# QuDAC_V2.net
KiCad netlist of a schematic drawn in EAGLE
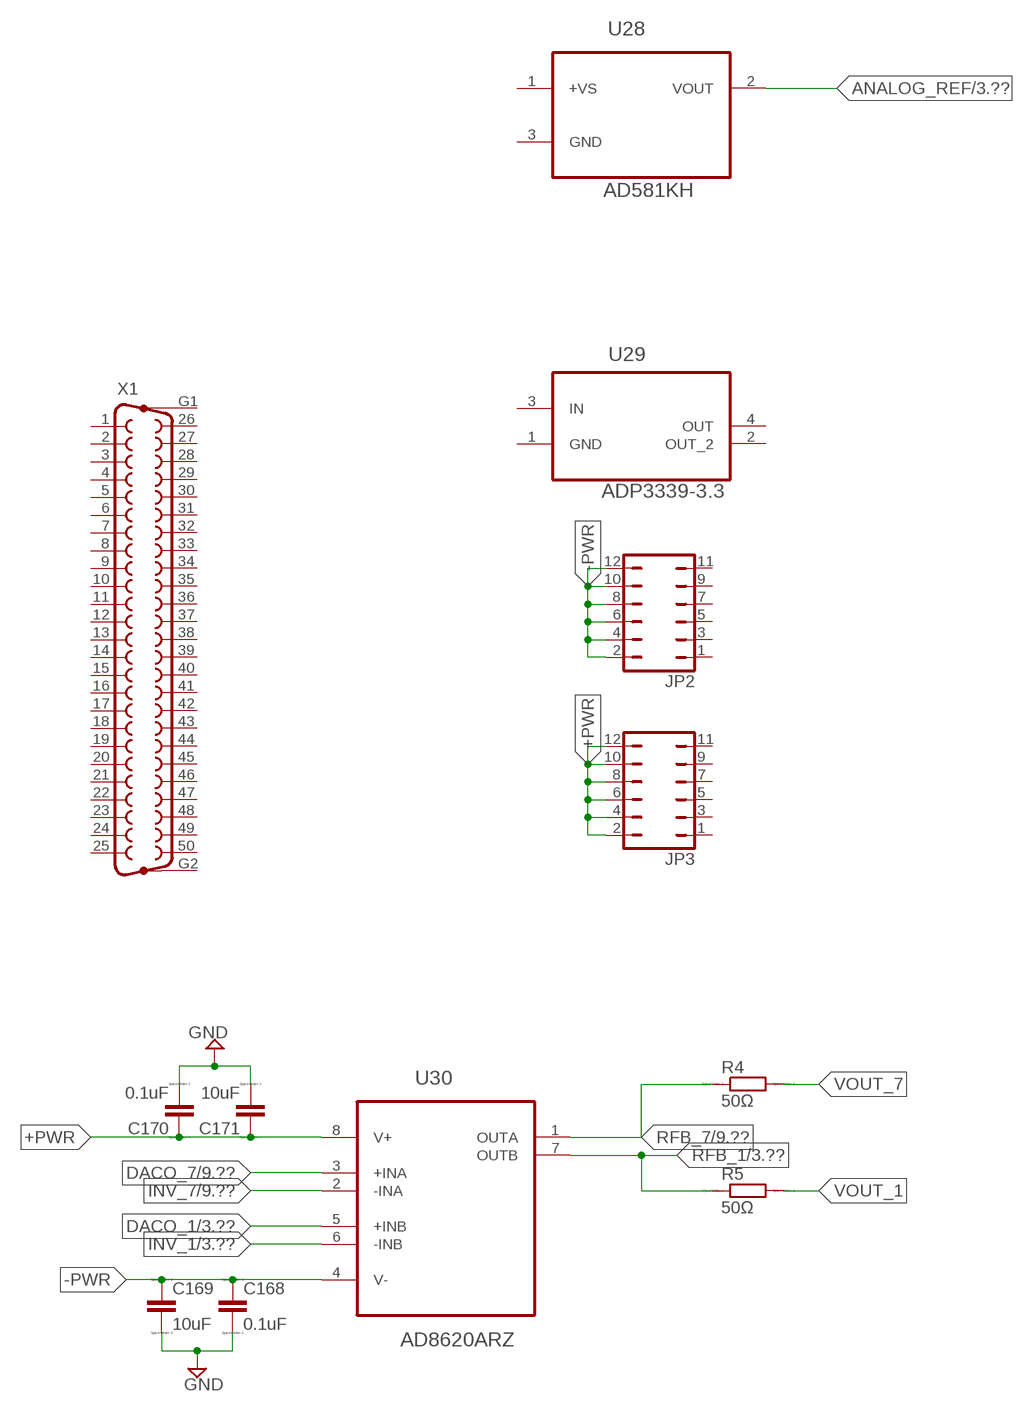
[diagram p0: schematic, sheet 1]
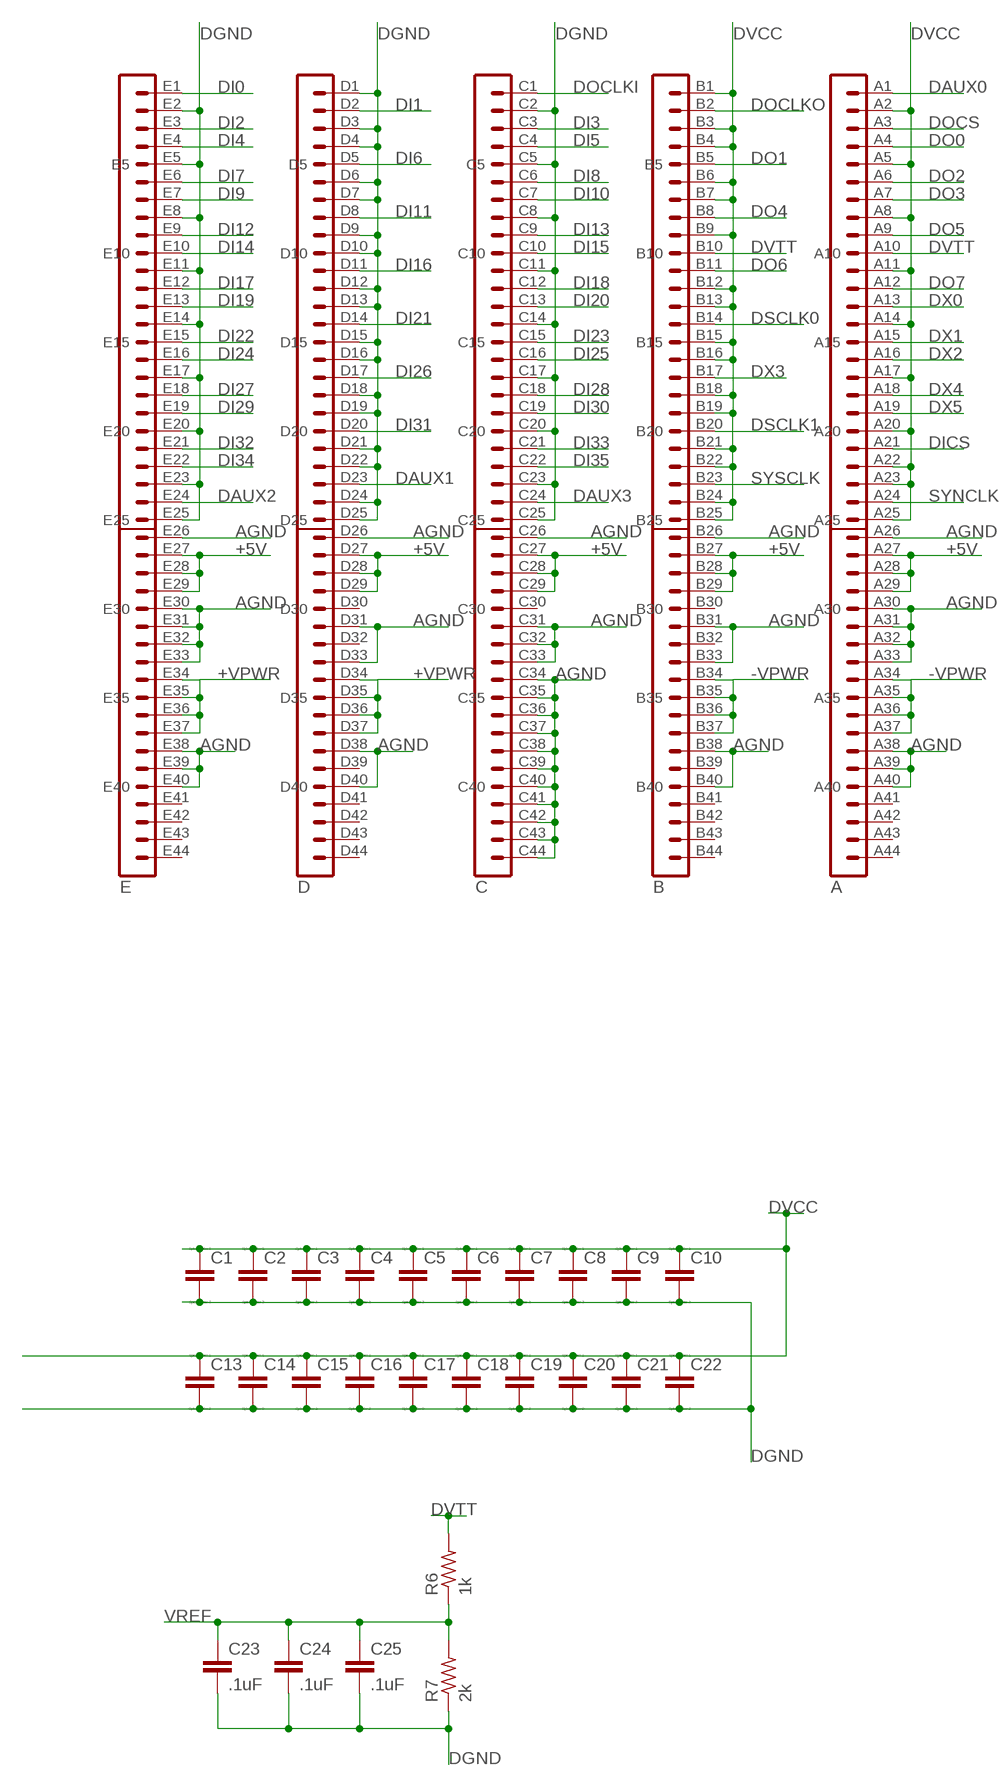
[diagram p1: schematic, sheet 2, part 1 of 2]
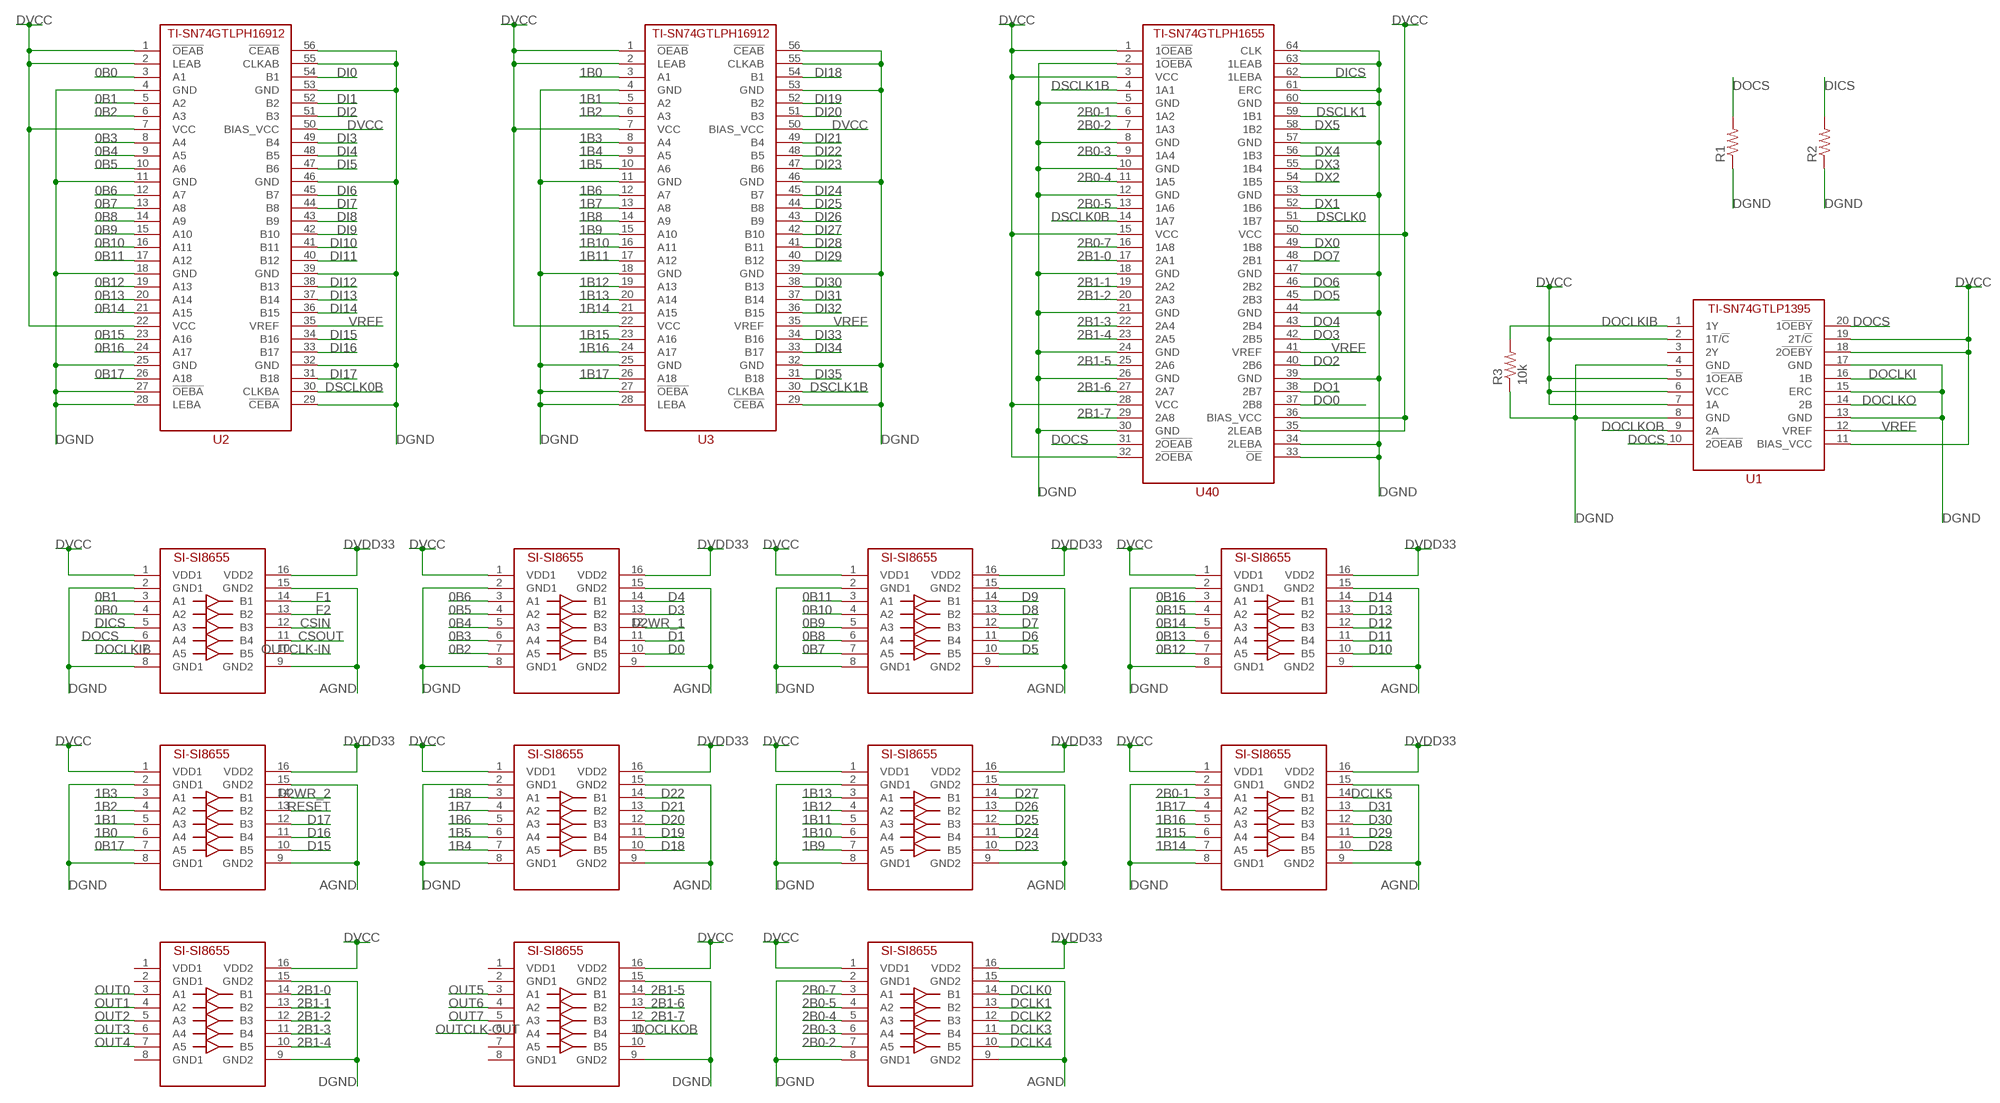
[diagram p2: schematic, sheet 2, part 2 of 2]
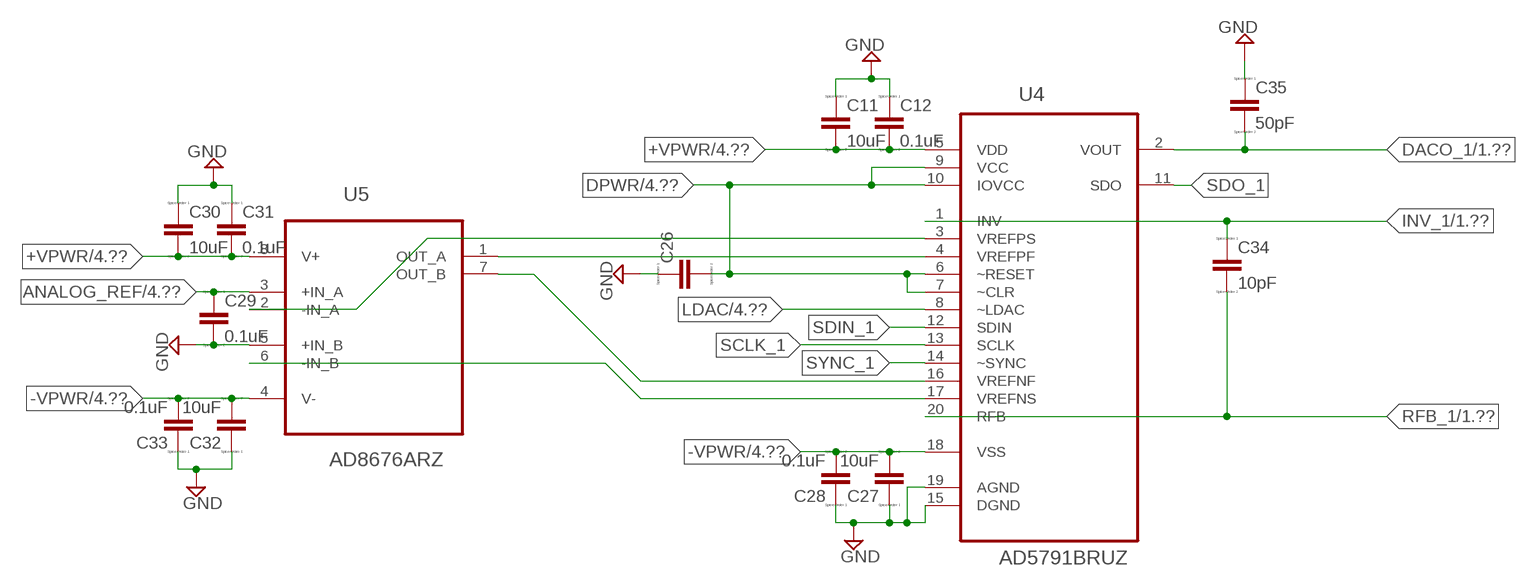
[diagram p3: schematic, sheet 3]
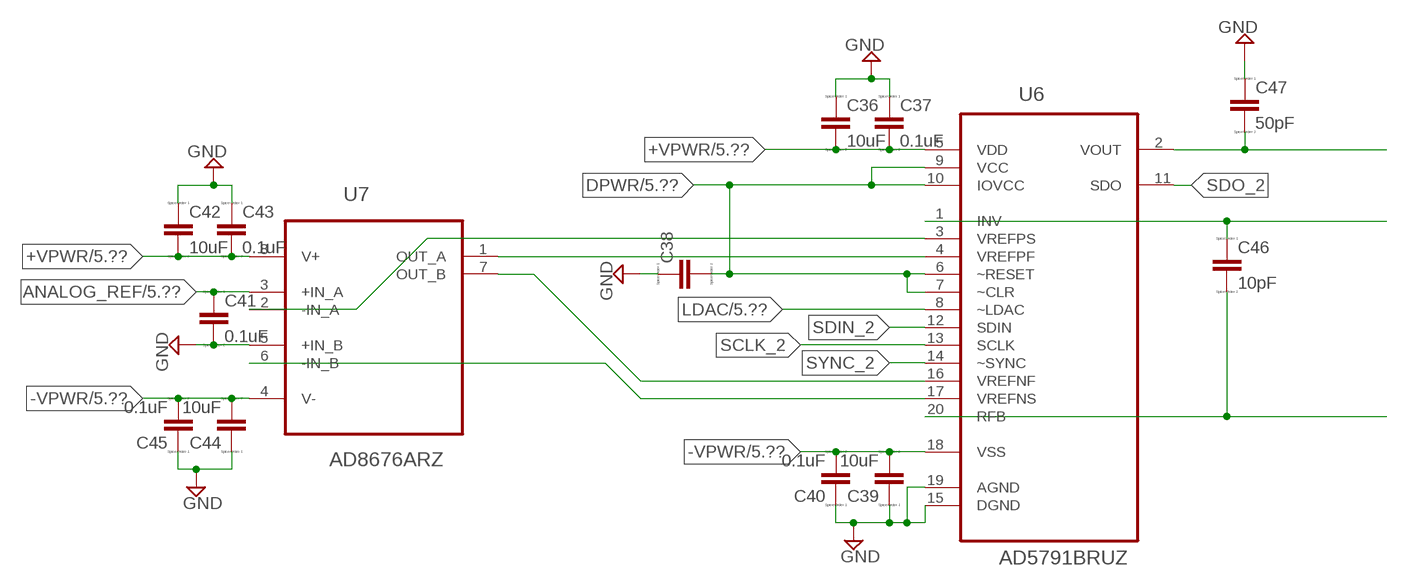
[diagram p4: schematic, sheet 4]
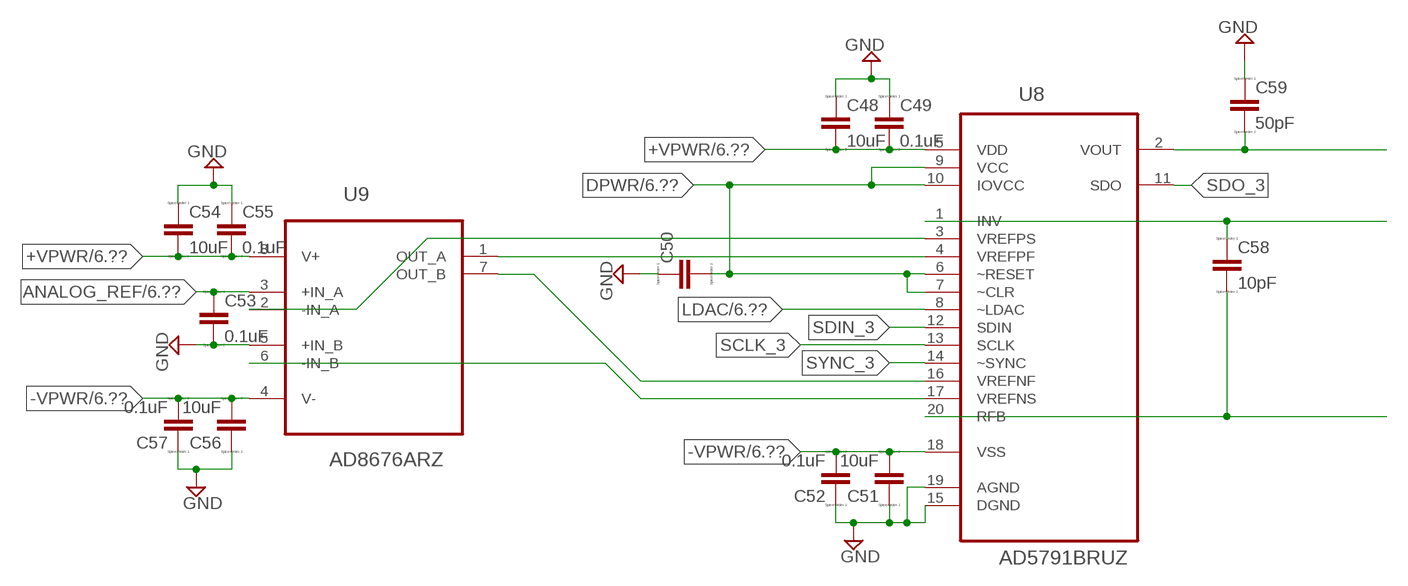
[diagram p5: schematic, sheet 5]
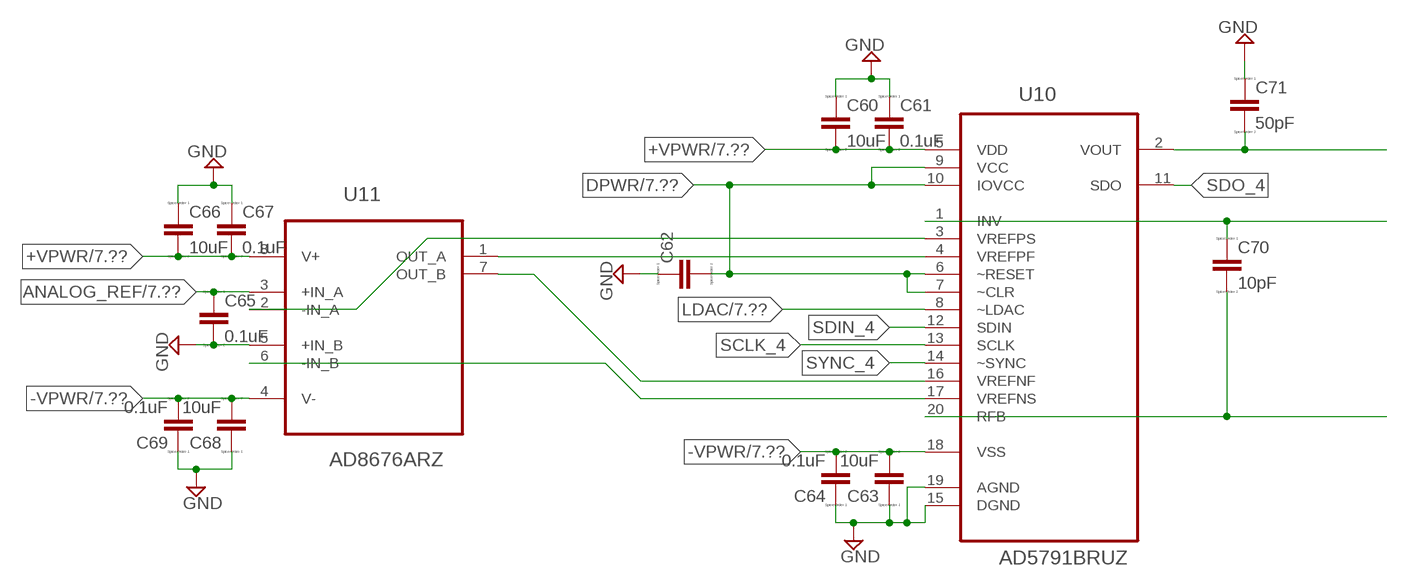
[diagram p6: schematic, sheet 6]
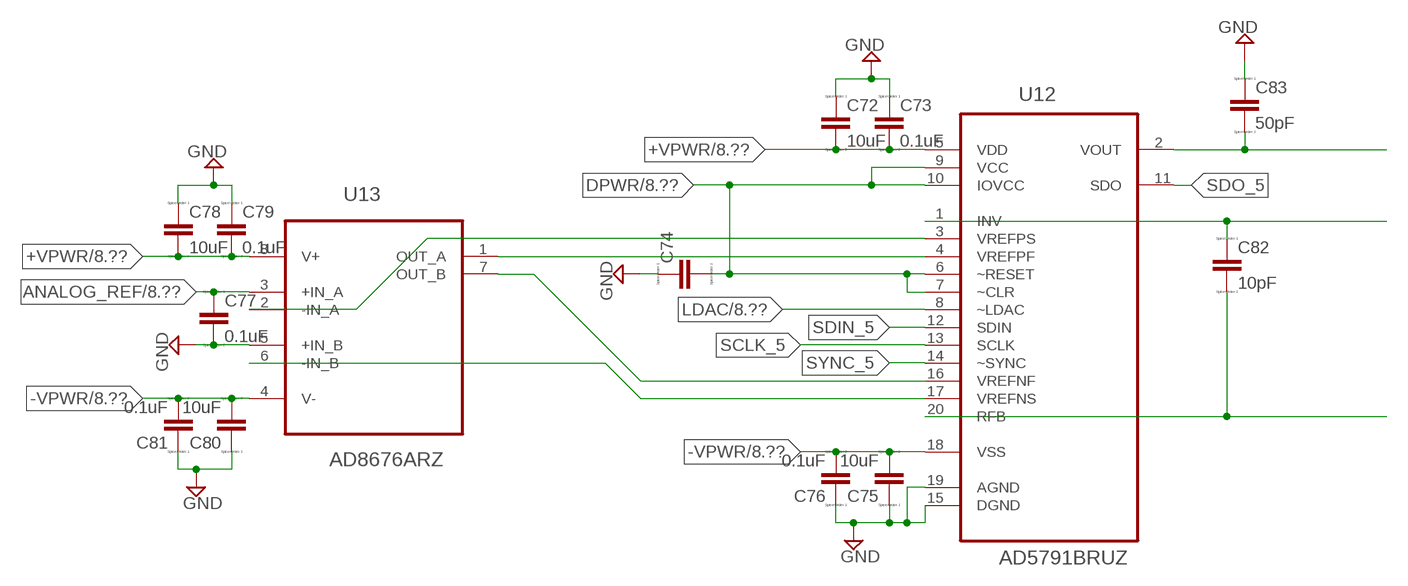
[diagram p7: schematic, sheet 7]
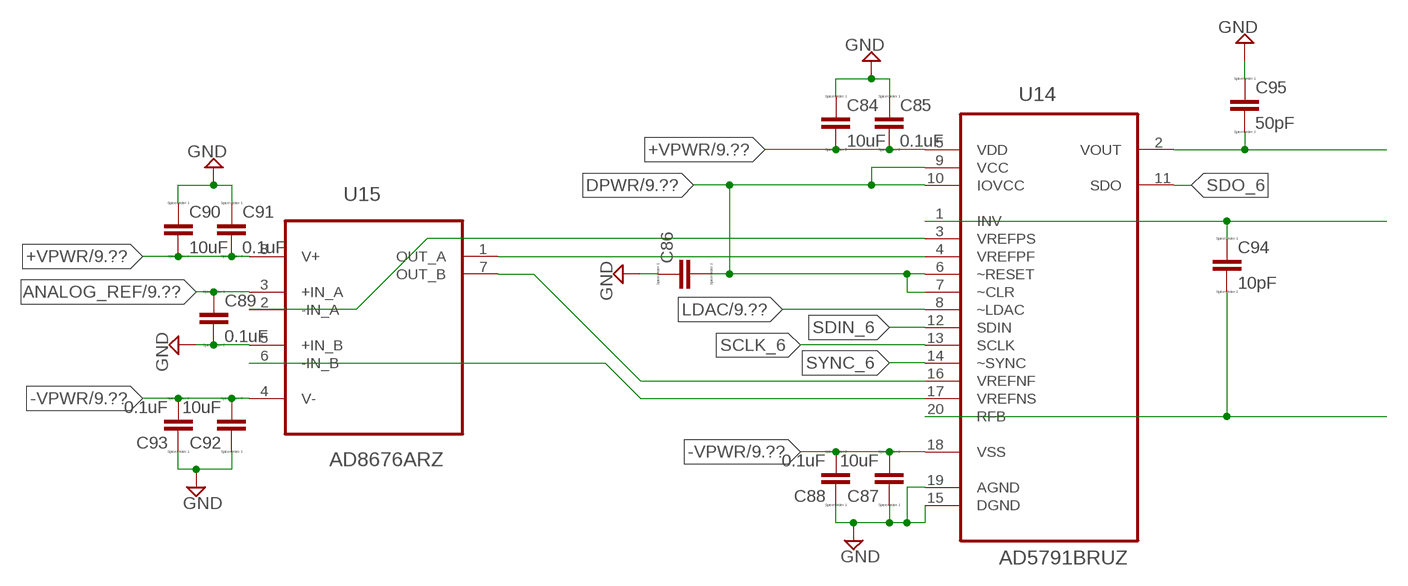
[diagram p8: schematic, sheet 8]
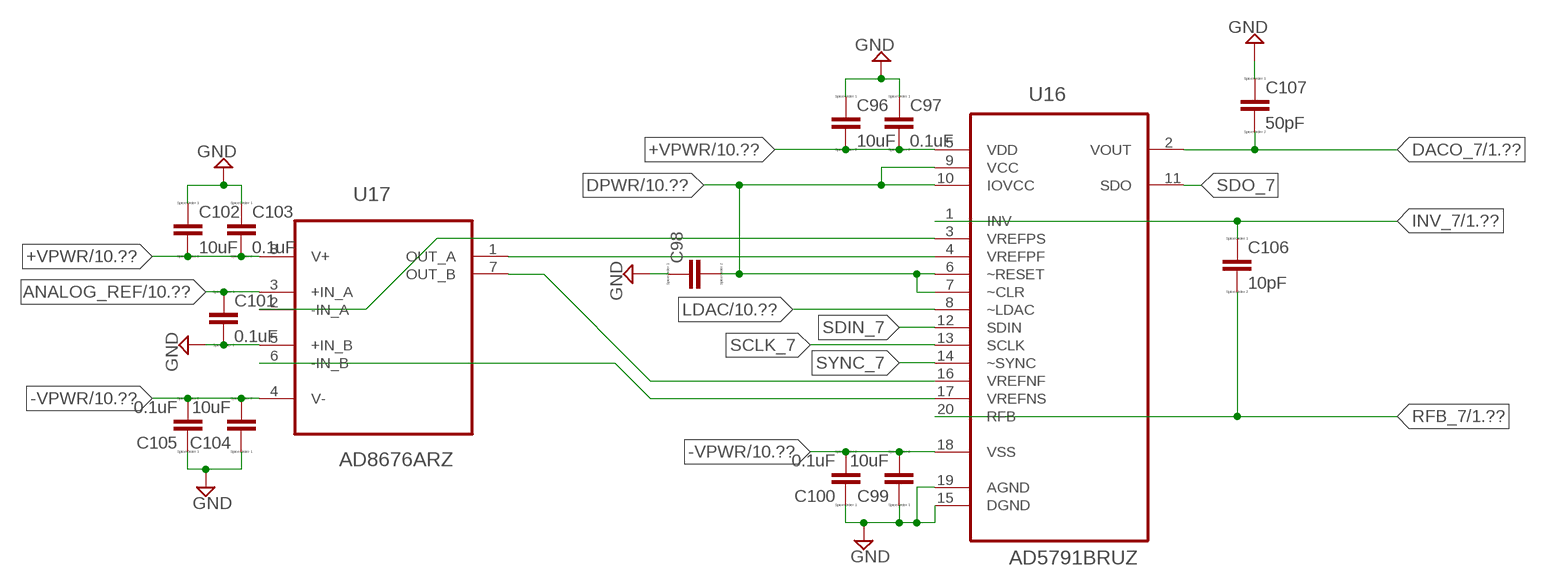
[diagram p9: schematic, sheet 9]
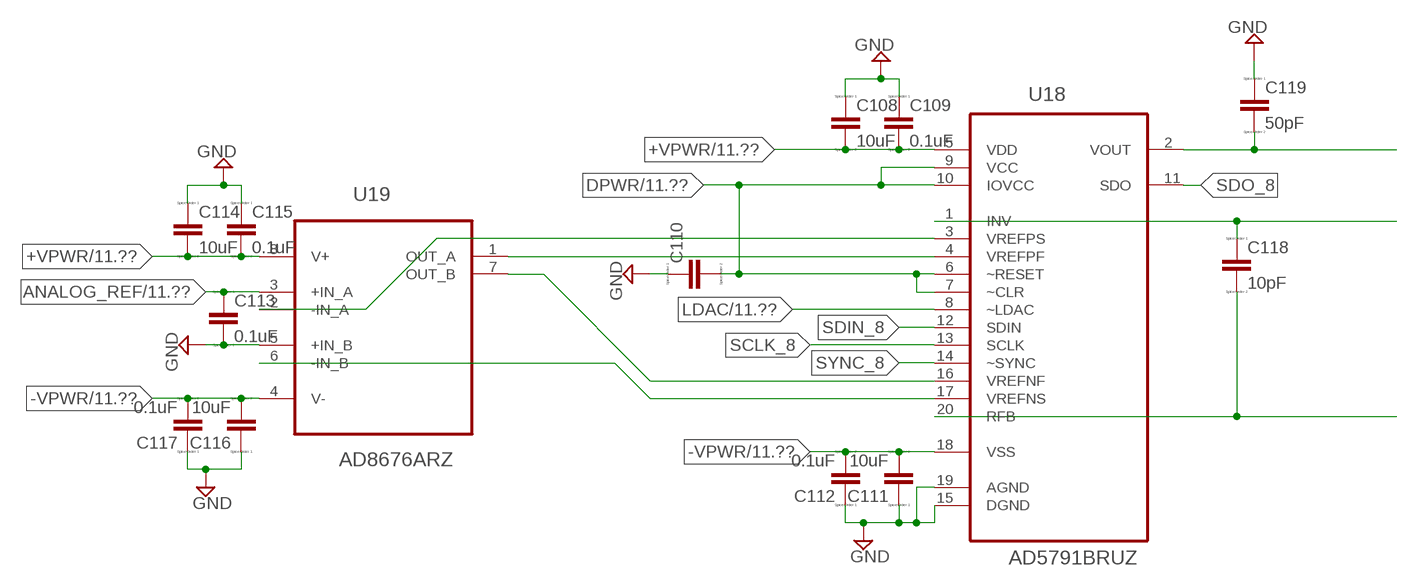
[diagram p10: schematic, sheet 10]
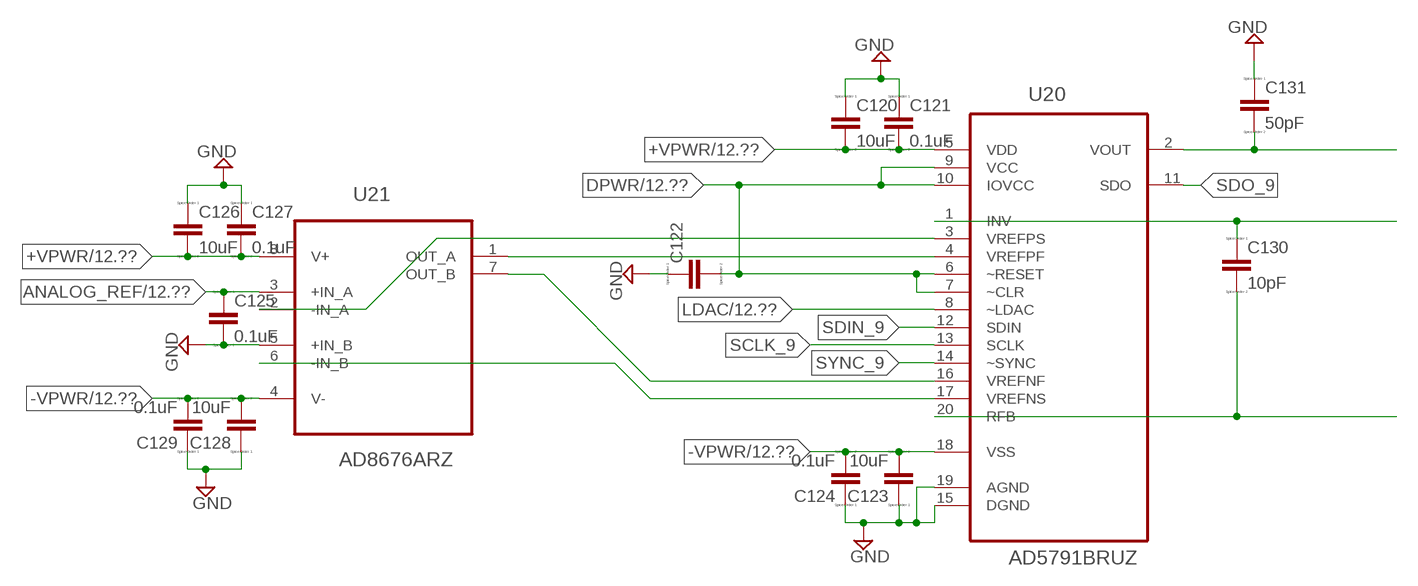
[diagram p11: schematic, sheet 11]
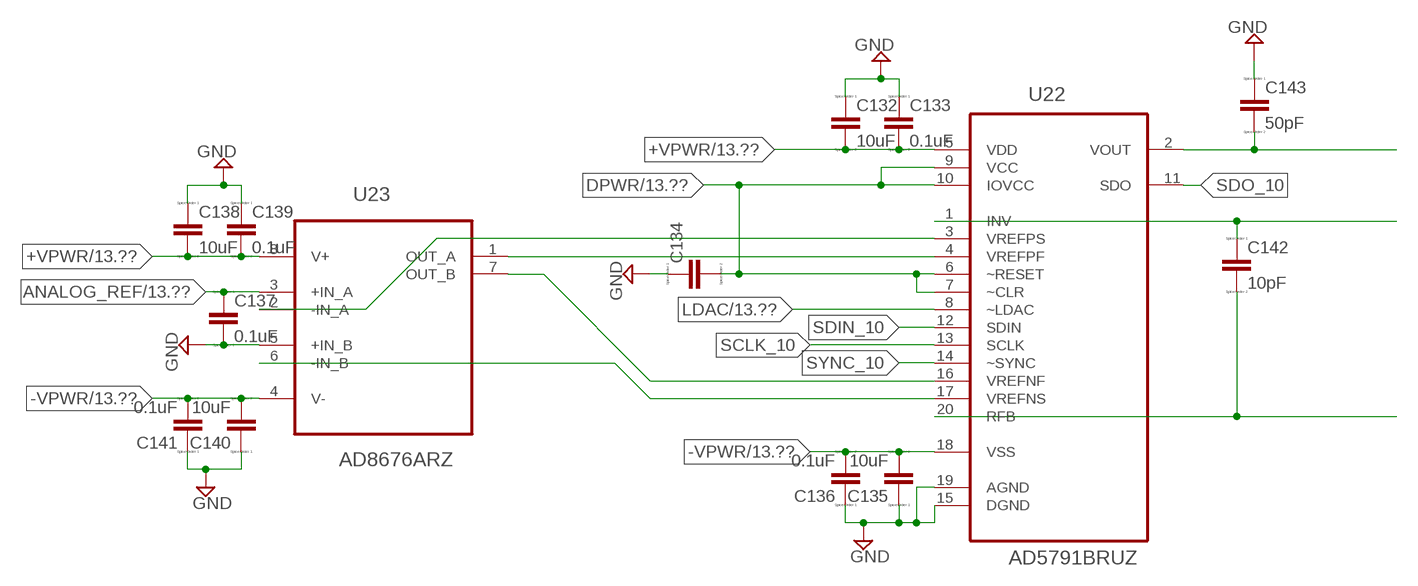
[diagram p12: schematic, sheet 12]
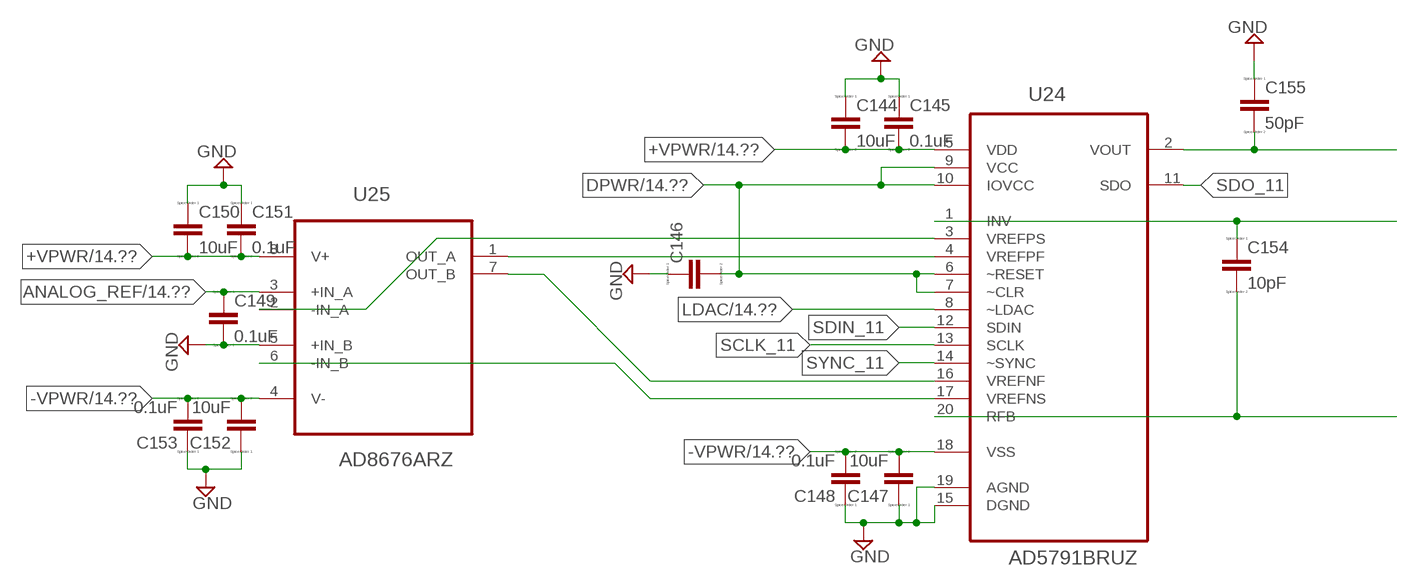
[diagram p13: schematic, sheet 13]
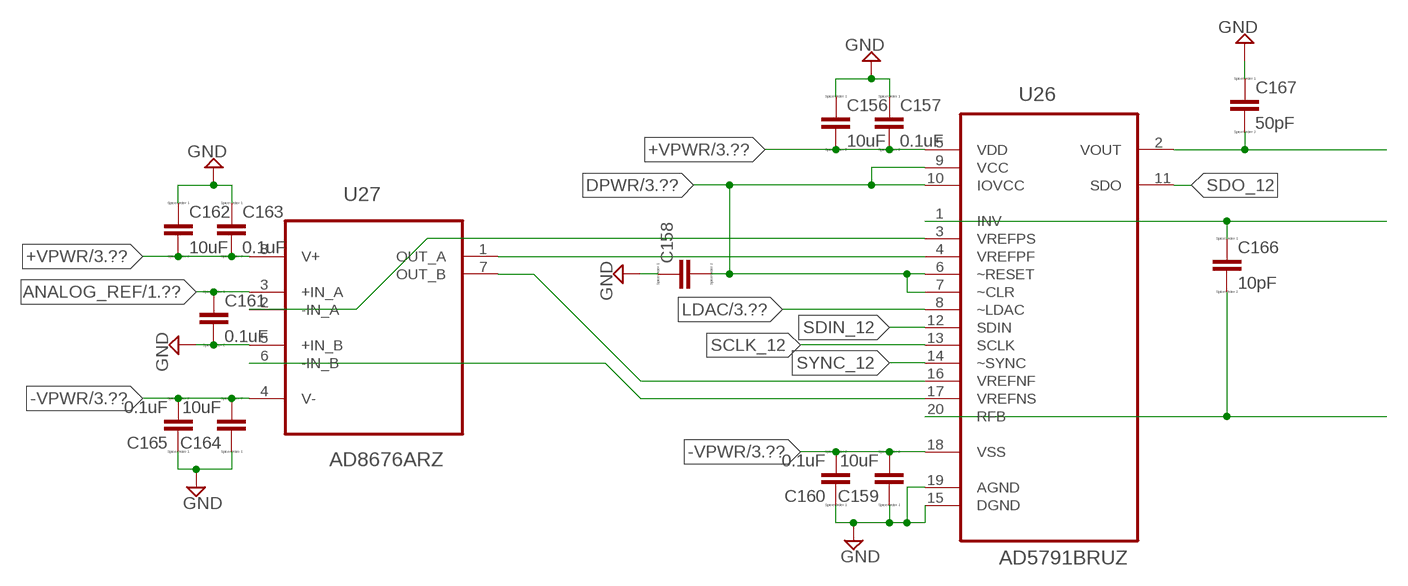
[diagram p14: schematic, sheet 14]

(export (version "E")
  (design (tool "Eeschema 10.0.6"))
  (components
    (comp (ref "C72")
      (value "10uF")
      (footprint "eagle-import:C0805")
      (libsource (lib "eagle-import") (part "C"))
    )
    (comp (ref "C73")
      (value "0.1uF")
      (footprint "eagle-import:C0603")
      (libsource (lib "eagle-import") (part "CC0603"))
    )
    (comp (ref "C74")
      (value "CC0603")
      (footprint "eagle-import:C0603")
      (libsource (lib "eagle-import") (part "CC0603"))
    )
    (comp (ref "C75")
      (value "10uF")
      (footprint "eagle-import:C0805")
      (libsource (lib "eagle-import") (part "C"))
    )
    (comp (ref "C76")
      (value "0.1uF")
      (footprint "eagle-import:C0603")
      (libsource (lib "eagle-import") (part "CC0603"))
    )
    (comp (ref "C77")
      (value "0.1uF")
      (footprint "eagle-import:C0603")
      (libsource (lib "eagle-import") (part "CC0603"))
    )
    (comp (ref "C78")
      (value "10uF")
      (footprint "eagle-import:C0805")
      (libsource (lib "eagle-import") (part "C"))
    )
    (comp (ref "C79")
      (value "0.1uF")
      (footprint "eagle-import:C0603")
      (libsource (lib "eagle-import") (part "CC0603"))
    )
    (comp (ref "C80")
      (value "10uF")
      (footprint "eagle-import:C0805")
      (libsource (lib "eagle-import") (part "C"))
    )
    (comp (ref "C81")
      (value "0.1uF")
      (footprint "eagle-import:C0603")
      (libsource (lib "eagle-import") (part "CC0603"))
    )
    (comp (ref "C82")
      (value "10pF")
      (footprint "eagle-import:C0603")
      (libsource (lib "eagle-import") (part "CC0603"))
    )
    (comp (ref "C83")
      (value "50pF")
      (footprint "eagle-import:C0603")
      (libsource (lib "eagle-import") (part "CC0603"))
    )
    (comp (ref "U12")
      (value "AD5791BRUZ")
      (footprint "eagle-import:SOP65P640X120-20N")
      (libsource (lib "eagle-import") (part "AD5791BRUZ"))
    )
    (comp (ref "U13")
      (value "AD8676ARZ")
      (footprint "eagle-import:SOIC127P600X175-8N")
      (libsource (lib "eagle-import") (part "AD8676ARZ"))
    )
    (comp (ref "C108")
      (value "10uF")
      (footprint "eagle-import:C0805")
      (libsource (lib "eagle-import") (part "C"))
    )
    (comp (ref "C109")
      (value "0.1uF")
      (footprint "eagle-import:C0603")
      (libsource (lib "eagle-import") (part "CC0603"))
    )
    (comp (ref "C110")
      (value "CC0603")
      (footprint "eagle-import:C0603")
      (libsource (lib "eagle-import") (part "CC0603"))
    )
    (comp (ref "C111")
      (value "10uF")
      (footprint "eagle-import:C0805")
      (libsource (lib "eagle-import") (part "C"))
    )
    (comp (ref "C112")
      (value "0.1uF")
      (footprint "eagle-import:C0603")
      (libsource (lib "eagle-import") (part "CC0603"))
    )
    (comp (ref "C113")
      (value "0.1uF")
      (footprint "eagle-import:C0603")
      (libsource (lib "eagle-import") (part "CC0603"))
    )
    (comp (ref "C114")
      (value "10uF")
      (footprint "eagle-import:C0805")
      (libsource (lib "eagle-import") (part "C"))
    )
    (comp (ref "C115")
      (value "0.1uF")
      (footprint "eagle-import:C0603")
      (libsource (lib "eagle-import") (part "CC0603"))
    )
    (comp (ref "C116")
      (value "10uF")
      (footprint "eagle-import:C0805")
      (libsource (lib "eagle-import") (part "C"))
    )
    (comp (ref "C117")
      (value "0.1uF")
      (footprint "eagle-import:C0603")
      (libsource (lib "eagle-import") (part "CC0603"))
    )
    (comp (ref "C118")
      (value "10pF")
      (footprint "eagle-import:C0603")
      (libsource (lib "eagle-import") (part "CC0603"))
    )
    (comp (ref "C119")
      (value "50pF")
      (footprint "eagle-import:C0603")
      (libsource (lib "eagle-import") (part "CC0603"))
    )
    (comp (ref "U18")
      (value "AD5791BRUZ")
      (footprint "eagle-import:SOP65P640X120-20N")
      (libsource (lib "eagle-import") (part "AD5791BRUZ"))
    )
    (comp (ref "U19")
      (value "AD8676ARZ")
      (footprint "eagle-import:SOIC127P600X175-8N")
      (libsource (lib "eagle-import") (part "AD8676ARZ"))
    )
    (comp (ref "C1")
      (value "CC0603")
      (footprint "eagle-import:C0603")
      (libsource (lib "eagle-import") (part "CC0603"))
    )
    (comp (ref "C2")
      (value "CC0603")
      (footprint "eagle-import:C0603")
      (libsource (lib "eagle-import") (part "CC0603"))
    )
    (comp (ref "C3")
      (value "CC0603")
      (footprint "eagle-import:C0603")
      (libsource (lib "eagle-import") (part "CC0603"))
    )
    (comp (ref "C4")
      (value "CC0603")
      (footprint "eagle-import:C0603")
      (libsource (lib "eagle-import") (part "CC0603"))
    )
    (comp (ref "C5")
      (value "CC0603")
      (footprint "eagle-import:C0603")
      (libsource (lib "eagle-import") (part "CC0603"))
    )
    (comp (ref "C6")
      (value "CC0603")
      (footprint "eagle-import:C0603")
      (libsource (lib "eagle-import") (part "CC0603"))
    )
    (comp (ref "C7")
      (value "CC0603")
      (footprint "eagle-import:C0603")
      (libsource (lib "eagle-import") (part "CC0603"))
    )
    (comp (ref "C8")
      (value "CC0603")
      (footprint "eagle-import:C0603")
      (libsource (lib "eagle-import") (part "CC0603"))
    )
    (comp (ref "C9")
      (value "CC0603")
      (footprint "eagle-import:C0603")
      (libsource (lib "eagle-import") (part "CC0603"))
    )
    (comp (ref "C10")
      (value "CC0603")
      (footprint "eagle-import:C0603")
      (libsource (lib "eagle-import") (part "CC0603"))
    )
    (comp (ref "C13")
      (value "CC0603")
      (footprint "eagle-import:C0603")
      (libsource (lib "eagle-import") (part "CC0603"))
    )
    (comp (ref "C14")
      (value "CC0603")
      (footprint "eagle-import:C0603")
      (libsource (lib "eagle-import") (part "CC0603"))
    )
    (comp (ref "C15")
      (value "CC0603")
      (footprint "eagle-import:C0603")
      (libsource (lib "eagle-import") (part "CC0603"))
    )
    (comp (ref "C16")
      (value "CC0603")
      (footprint "eagle-import:C0603")
      (libsource (lib "eagle-import") (part "CC0603"))
    )
    (comp (ref "C17")
      (value "CC0603")
      (footprint "eagle-import:C0603")
      (libsource (lib "eagle-import") (part "CC0603"))
    )
    (comp (ref "C18")
      (value "CC0603")
      (footprint "eagle-import:C0603")
      (libsource (lib "eagle-import") (part "CC0603"))
    )
    (comp (ref "C19")
      (value "CC0603")
      (footprint "eagle-import:C0603")
      (libsource (lib "eagle-import") (part "CC0603"))
    )
    (comp (ref "C20")
      (value "CC0603")
      (footprint "eagle-import:C0603")
      (libsource (lib "eagle-import") (part "CC0603"))
    )
    (comp (ref "C21")
      (value "CC0603")
      (footprint "eagle-import:C0603")
      (libsource (lib "eagle-import") (part "CC0603"))
    )
    (comp (ref "C22")
      (value "CC0603")
      (footprint "eagle-import:C0603")
      (libsource (lib "eagle-import") (part "CC0603"))
    )
    (comp (ref "C23")
      (value ".1uF")
      (footprint "eagle-import:C0603")
      (libsource (lib "eagle-import") (part "C-EUC0603"))
    )
    (comp (ref "C24")
      (value ".1uF")
      (footprint "eagle-import:C0603")
      (libsource (lib "eagle-import") (part "C-EUC0603"))
    )
    (comp (ref "C25")
      (value ".1uF")
      (footprint "eagle-import:C0603")
      (libsource (lib "eagle-import") (part "C-EUC0603"))
    )
    (comp (ref "ISO1")
      (value "SI-SI8655")
      (footprint "eagle-import:QSOP-16")
      (libsource (lib "eagle-import") (part "SI-SI8655"))
    )
    (comp (ref "ISO2")
      (value "SI-SI8655")
      (footprint "eagle-import:QSOP-16")
      (libsource (lib "eagle-import") (part "SI-SI8655"))
    )
    (comp (ref "ISO3")
      (value "SI-SI8655")
      (footprint "eagle-import:QSOP-16")
      (libsource (lib "eagle-import") (part "SI-SI8655"))
    )
    (comp (ref "ISO4")
      (value "SI-SI8655")
      (footprint "eagle-import:QSOP-16")
      (libsource (lib "eagle-import") (part "SI-SI8655"))
    )
    (comp (ref "ISO5")
      (value "SI-SI8655")
      (footprint "eagle-import:QSOP-16")
      (libsource (lib "eagle-import") (part "SI-SI8655"))
    )
    (comp (ref "ISO6")
      (value "SI-SI8655")
      (footprint "eagle-import:QSOP-16")
      (libsource (lib "eagle-import") (part "SI-SI8655"))
    )
    (comp (ref "ISO7")
      (value "SI-SI8655")
      (footprint "eagle-import:QSOP-16")
      (libsource (lib "eagle-import") (part "SI-SI8655"))
    )
    (comp (ref "ISO8")
      (value "SI-SI8655")
      (footprint "eagle-import:QSOP-16")
      (libsource (lib "eagle-import") (part "SI-SI8655"))
    )
    (comp (ref "ISO9")
      (value "SI-SI8655")
      (footprint "eagle-import:QSOP-16")
      (libsource (lib "eagle-import") (part "SI-SI8655"))
    )
    (comp (ref "ISO10")
      (value "SI-SI8655")
      (footprint "eagle-import:QSOP-16")
      (libsource (lib "eagle-import") (part "SI-SI8655"))
    )
    (comp (ref "ISO11")
      (value "SI-SI8655")
      (footprint "eagle-import:QSOP-16")
      (libsource (lib "eagle-import") (part "SI-SI8655"))
    )
    (comp (ref "J1")
      (value "EUROCARD-CPCI-220EUROCARD-B19+AB25-NOFRONTDIM")
      (footprint "eagle-import:EUROCARD-CPCI-B19+1B25-NOFRONTDIM")
      (libsource (lib "eagle-import") (part "EUROCARD-CPCI-220EUROCARD-B19+AB25-NOFRONTDIM"))
    )
    (comp (ref "R1")
      (value "R-US_R0603")
      (footprint "eagle-import:R0603")
      (libsource (lib "eagle-import") (part "R-US_R0603"))
    )
    (comp (ref "R2")
      (value "R-US_R0603")
      (footprint "eagle-import:R0603")
      (libsource (lib "eagle-import") (part "R-US_R0603"))
    )
    (comp (ref "R3")
      (value "10k")
      (footprint "eagle-import:R0603")
      (libsource (lib "eagle-import") (part "R-US_R0603"))
    )
    (comp (ref "R6")
      (value "1k")
      (footprint "eagle-import:R0805")
      (libsource (lib "eagle-import") (part "R-US_R0805"))
    )
    (comp (ref "R7")
      (value "2k")
      (footprint "eagle-import:R0805")
      (libsource (lib "eagle-import") (part "R-US_R0805"))
    )
    (comp (ref "U1")
      (value "TI-SN74GTLP1395")
      (footprint "eagle-import:TSSOP-20")
      (libsource (lib "eagle-import") (part "TI-SN74GTLP1395"))
    )
    (comp (ref "U2")
      (value "TI-SN74GTLPH16912")
      (footprint "eagle-import:TSSOP-56")
      (libsource (lib "eagle-import") (part "TI-SN74GTLPH16912"))
    )
    (comp (ref "U3")
      (value "TI-SN74GTLPH16912")
      (footprint "eagle-import:TSSOP-56")
      (libsource (lib "eagle-import") (part "TI-SN74GTLPH16912"))
    )
    (comp (ref "U40")
      (value "TI-SN74GTLPH1655")
      (footprint "eagle-import:TSSOP-64")
      (libsource (lib "eagle-import") (part "TI-SN74GTLPH1655"))
    )
    (comp (ref "C36")
      (value "10uF")
      (footprint "eagle-import:C0805")
      (libsource (lib "eagle-import") (part "C"))
    )
    (comp (ref "C37")
      (value "0.1uF")
      (footprint "eagle-import:C0603")
      (libsource (lib "eagle-import") (part "CC0603"))
    )
    (comp (ref "C38")
      (value "CC0603")
      (footprint "eagle-import:C0603")
      (libsource (lib "eagle-import") (part "CC0603"))
    )
    (comp (ref "C39")
      (value "10uF")
      (footprint "eagle-import:C0805")
      (libsource (lib "eagle-import") (part "C"))
    )
    (comp (ref "C40")
      (value "0.1uF")
      (footprint "eagle-import:C0603")
      (libsource (lib "eagle-import") (part "CC0603"))
    )
    (comp (ref "C41")
      (value "0.1uF")
      (footprint "eagle-import:C0603")
      (libsource (lib "eagle-import") (part "CC0603"))
    )
    (comp (ref "C42")
      (value "10uF")
      (footprint "eagle-import:C0805")
      (libsource (lib "eagle-import") (part "C"))
    )
    (comp (ref "C43")
      (value "0.1uF")
      (footprint "eagle-import:C0603")
      (libsource (lib "eagle-import") (part "CC0603"))
    )
    (comp (ref "C44")
      (value "10uF")
      (footprint "eagle-import:C0805")
      (libsource (lib "eagle-import") (part "C"))
    )
    (comp (ref "C45")
      (value "0.1uF")
      (footprint "eagle-import:C0603")
      (libsource (lib "eagle-import") (part "CC0603"))
    )
    (comp (ref "C46")
      (value "10pF")
      (footprint "eagle-import:C0603")
      (libsource (lib "eagle-import") (part "CC0603"))
    )
    (comp (ref "C47")
      (value "50pF")
      (footprint "eagle-import:C0603")
      (libsource (lib "eagle-import") (part "CC0603"))
    )
    (comp (ref "U6")
      (value "AD5791BRUZ")
      (footprint "eagle-import:SOP65P640X120-20N")
      (libsource (lib "eagle-import") (part "AD5791BRUZ"))
    )
    (comp (ref "U7")
      (value "AD8676ARZ")
      (footprint "eagle-import:SOIC127P600X175-8N")
      (libsource (lib "eagle-import") (part "AD8676ARZ"))
    )
    (comp (ref "C60")
      (value "10uF")
      (footprint "eagle-import:C0805")
      (libsource (lib "eagle-import") (part "C"))
    )
    (comp (ref "C61")
      (value "0.1uF")
      (footprint "eagle-import:C0603")
      (libsource (lib "eagle-import") (part "CC0603"))
    )
    (comp (ref "C62")
      (value "CC0603")
      (footprint "eagle-import:C0603")
      (libsource (lib "eagle-import") (part "CC0603"))
    )
    (comp (ref "C63")
      (value "10uF")
      (footprint "eagle-import:C0805")
      (libsource (lib "eagle-import") (part "C"))
    )
    (comp (ref "C64")
      (value "0.1uF")
      (footprint "eagle-import:C0603")
      (libsource (lib "eagle-import") (part "CC0603"))
    )
    (comp (ref "C65")
      (value "0.1uF")
      (footprint "eagle-import:C0603")
      (libsource (lib "eagle-import") (part "CC0603"))
    )
    (comp (ref "C66")
      (value "10uF")
      (footprint "eagle-import:C0805")
      (libsource (lib "eagle-import") (part "C"))
    )
    (comp (ref "C67")
      (value "0.1uF")
      (footprint "eagle-import:C0603")
      (libsource (lib "eagle-import") (part "CC0603"))
    )
    (comp (ref "C68")
      (value "10uF")
      (footprint "eagle-import:C0805")
      (libsource (lib "eagle-import") (part "C"))
    )
    (comp (ref "C69")
      (value "0.1uF")
      (footprint "eagle-import:C0603")
      (libsource (lib "eagle-import") (part "CC0603"))
    )
    (comp (ref "C70")
      (value "10pF")
      (footprint "eagle-import:C0603")
      (libsource (lib "eagle-import") (part "CC0603"))
    )
    (comp (ref "C71")
      (value "50pF")
      (footprint "eagle-import:C0603")
      (libsource (lib "eagle-import") (part "CC0603"))
    )
    (comp (ref "U10")
      (value "AD5791BRUZ")
      (footprint "eagle-import:SOP65P640X120-20N")
      (libsource (lib "eagle-import") (part "AD5791BRUZ"))
    )
    (comp (ref "U11")
      (value "AD8676ARZ")
      (footprint "eagle-import:SOIC127P600X175-8N")
      (libsource (lib "eagle-import") (part "AD8676ARZ"))
    )
    (comp (ref "C120")
      (value "10uF")
      (footprint "eagle-import:C0805")
      (libsource (lib "eagle-import") (part "C"))
    )
    (comp (ref "C121")
      (value "0.1uF")
      (footprint "eagle-import:C0603")
      (libsource (lib "eagle-import") (part "CC0603"))
    )
    (comp (ref "C122")
      (value "CC0603")
      (footprint "eagle-import:C0603")
      (libsource (lib "eagle-import") (part "CC0603"))
    )
    (comp (ref "C123")
      (value "10uF")
      (footprint "eagle-import:C0805")
      (libsource (lib "eagle-import") (part "C"))
    )
    (comp (ref "C124")
      (value "0.1uF")
      (footprint "eagle-import:C0603")
      (libsource (lib "eagle-import") (part "CC0603"))
    )
    (comp (ref "C125")
      (value "0.1uF")
      (footprint "eagle-import:C0603")
      (libsource (lib "eagle-import") (part "CC0603"))
    )
    (comp (ref "C126")
      (value "10uF")
      (footprint "eagle-import:C0805")
      (libsource (lib "eagle-import") (part "C"))
    )
    (comp (ref "C127")
      (value "0.1uF")
      (footprint "eagle-import:C0603")
      (libsource (lib "eagle-import") (part "CC0603"))
    )
    (comp (ref "C128")
      (value "10uF")
      (footprint "eagle-import:C0805")
      (libsource (lib "eagle-import") (part "C"))
    )
    (comp (ref "C129")
      (value "0.1uF")
      (footprint "eagle-import:C0603")
      (libsource (lib "eagle-import") (part "CC0603"))
    )
    (comp (ref "C130")
      (value "10pF")
      (footprint "eagle-import:C0603")
      (libsource (lib "eagle-import") (part "CC0603"))
    )
    (comp (ref "C131")
      (value "50pF")
      (footprint "eagle-import:C0603")
      (libsource (lib "eagle-import") (part "CC0603"))
    )
    (comp (ref "U20")
      (value "AD5791BRUZ")
      (footprint "eagle-import:SOP65P640X120-20N")
      (libsource (lib "eagle-import") (part "AD5791BRUZ"))
    )
    (comp (ref "U21")
      (value "AD8676ARZ")
      (footprint "eagle-import:SOIC127P600X175-8N")
      (libsource (lib "eagle-import") (part "AD8676ARZ"))
    )
    (comp (ref "C144")
      (value "10uF")
      (footprint "eagle-import:C0805")
      (libsource (lib "eagle-import") (part "C"))
    )
    (comp (ref "C145")
      (value "0.1uF")
      (footprint "eagle-import:C0603")
      (libsource (lib "eagle-import") (part "CC0603"))
    )
    (comp (ref "C146")
      (value "CC0603")
      (footprint "eagle-import:C0603")
      (libsource (lib "eagle-import") (part "CC0603"))
    )
    (comp (ref "C147")
      (value "10uF")
      (footprint "eagle-import:C0805")
      (libsource (lib "eagle-import") (part "C"))
    )
    (comp (ref "C148")
      (value "0.1uF")
      (footprint "eagle-import:C0603")
      (libsource (lib "eagle-import") (part "CC0603"))
    )
    (comp (ref "C149")
      (value "0.1uF")
      (footprint "eagle-import:C0603")
      (libsource (lib "eagle-import") (part "CC0603"))
    )
    (comp (ref "C150")
      (value "10uF")
      (footprint "eagle-import:C0805")
      (libsource (lib "eagle-import") (part "C"))
    )
    (comp (ref "C151")
      (value "0.1uF")
      (footprint "eagle-import:C0603")
      (libsource (lib "eagle-import") (part "CC0603"))
    )
    (comp (ref "C152")
      (value "10uF")
      (footprint "eagle-import:C0805")
      (libsource (lib "eagle-import") (part "C"))
    )
    (comp (ref "C153")
      (value "0.1uF")
      (footprint "eagle-import:C0603")
      (libsource (lib "eagle-import") (part "CC0603"))
    )
    (comp (ref "C154")
      (value "10pF")
      (footprint "eagle-import:C0603")
      (libsource (lib "eagle-import") (part "CC0603"))
    )
    (comp (ref "C155")
      (value "50pF")
      (footprint "eagle-import:C0603")
      (libsource (lib "eagle-import") (part "CC0603"))
    )
    (comp (ref "U24")
      (value "AD5791BRUZ")
      (footprint "eagle-import:SOP65P640X120-20N")
      (libsource (lib "eagle-import") (part "AD5791BRUZ"))
    )
    (comp (ref "U25")
      (value "AD8676ARZ")
      (footprint "eagle-import:SOIC127P600X175-8N")
      (libsource (lib "eagle-import") (part "AD8676ARZ"))
    )
    (comp (ref "C96")
      (value "10uF")
      (footprint "eagle-import:C0805")
      (libsource (lib "eagle-import") (part "C"))
    )
    (comp (ref "C97")
      (value "0.1uF")
      (footprint "eagle-import:C0603")
      (libsource (lib "eagle-import") (part "CC0603"))
    )
    (comp (ref "C98")
      (value "CC0603")
      (footprint "eagle-import:C0603")
      (libsource (lib "eagle-import") (part "CC0603"))
    )
    (comp (ref "C99")
      (value "10uF")
      (footprint "eagle-import:C0805")
      (libsource (lib "eagle-import") (part "C"))
    )
    (comp (ref "C100")
      (value "0.1uF")
      (footprint "eagle-import:C0603")
      (libsource (lib "eagle-import") (part "CC0603"))
    )
    (comp (ref "C101")
      (value "0.1uF")
      (footprint "eagle-import:C0603")
      (libsource (lib "eagle-import") (part "CC0603"))
    )
    (comp (ref "C102")
      (value "10uF")
      (footprint "eagle-import:C0805")
      (libsource (lib "eagle-import") (part "C"))
    )
    (comp (ref "C103")
      (value "0.1uF")
      (footprint "eagle-import:C0603")
      (libsource (lib "eagle-import") (part "CC0603"))
    )
    (comp (ref "C104")
      (value "10uF")
      (footprint "eagle-import:C0805")
      (libsource (lib "eagle-import") (part "C"))
    )
    (comp (ref "C105")
      (value "0.1uF")
      (footprint "eagle-import:C0603")
      (libsource (lib "eagle-import") (part "CC0603"))
    )
    (comp (ref "C106")
      (value "10pF")
      (footprint "eagle-import:C0603")
      (libsource (lib "eagle-import") (part "CC0603"))
    )
    (comp (ref "C107")
      (value "50pF")
      (footprint "eagle-import:C0603")
      (libsource (lib "eagle-import") (part "CC0603"))
    )
    (comp (ref "U16")
      (value "AD5791BRUZ")
      (footprint "eagle-import:SOP65P640X120-20N")
      (libsource (lib "eagle-import") (part "AD5791BRUZ"))
    )
    (comp (ref "U17")
      (value "AD8676ARZ")
      (footprint "eagle-import:SOIC127P600X175-8N")
      (libsource (lib "eagle-import") (part "AD8676ARZ"))
    )
    (comp (ref "C11")
      (value "10uF")
      (footprint "eagle-import:C0805")
      (libsource (lib "eagle-import") (part "C"))
    )
    (comp (ref "C12")
      (value "0.1uF")
      (footprint "eagle-import:C0603")
      (libsource (lib "eagle-import") (part "CC0603"))
    )
    (comp (ref "C26")
      (value "CC0603")
      (footprint "eagle-import:C0603")
      (libsource (lib "eagle-import") (part "CC0603"))
    )
    (comp (ref "C27")
      (value "10uF")
      (footprint "eagle-import:C0805")
      (libsource (lib "eagle-import") (part "C"))
    )
    (comp (ref "C28")
      (value "0.1uF")
      (footprint "eagle-import:C0603")
      (libsource (lib "eagle-import") (part "CC0603"))
    )
    (comp (ref "C29")
      (value "0.1uF")
      (footprint "eagle-import:C0603")
      (libsource (lib "eagle-import") (part "CC0603"))
    )
    (comp (ref "C30")
      (value "10uF")
      (footprint "eagle-import:C0805")
      (libsource (lib "eagle-import") (part "C"))
    )
    (comp (ref "C31")
      (value "0.1uF")
      (footprint "eagle-import:C0603")
      (libsource (lib "eagle-import") (part "CC0603"))
    )
    (comp (ref "C32")
      (value "10uF")
      (footprint "eagle-import:C0805")
      (libsource (lib "eagle-import") (part "C"))
    )
    (comp (ref "C33")
      (value "0.1uF")
      (footprint "eagle-import:C0603")
      (libsource (lib "eagle-import") (part "CC0603"))
    )
    (comp (ref "C34")
      (value "10pF")
      (footprint "eagle-import:C0603")
      (libsource (lib "eagle-import") (part "CC0603"))
    )
    (comp (ref "C35")
      (value "50pF")
      (footprint "eagle-import:C0603")
      (libsource (lib "eagle-import") (part "CC0603"))
    )
    (comp (ref "U4")
      (value "AD5791BRUZ")
      (footprint "eagle-import:SOP65P640X120-20N")
      (libsource (lib "eagle-import") (part "AD5791BRUZ"))
    )
    (comp (ref "U5")
      (value "AD8676ARZ")
      (footprint "eagle-import:SOIC127P600X175-8N")
      (libsource (lib "eagle-import") (part "AD8676ARZ"))
    )
    (comp (ref "C132")
      (value "10uF")
      (footprint "eagle-import:C0805")
      (libsource (lib "eagle-import") (part "C"))
    )
    (comp (ref "C133")
      (value "0.1uF")
      (footprint "eagle-import:C0603")
      (libsource (lib "eagle-import") (part "CC0603"))
    )
    (comp (ref "C134")
      (value "CC0603")
      (footprint "eagle-import:C0603")
      (libsource (lib "eagle-import") (part "CC0603"))
    )
    (comp (ref "C135")
      (value "10uF")
      (footprint "eagle-import:C0805")
      (libsource (lib "eagle-import") (part "C"))
    )
    (comp (ref "C136")
      (value "0.1uF")
      (footprint "eagle-import:C0603")
      (libsource (lib "eagle-import") (part "CC0603"))
    )
    (comp (ref "C137")
      (value "0.1uF")
      (footprint "eagle-import:C0603")
      (libsource (lib "eagle-import") (part "CC0603"))
    )
    (comp (ref "C138")
      (value "10uF")
      (footprint "eagle-import:C0805")
      (libsource (lib "eagle-import") (part "C"))
    )
    (comp (ref "C139")
      (value "0.1uF")
      (footprint "eagle-import:C0603")
      (libsource (lib "eagle-import") (part "CC0603"))
    )
    (comp (ref "C140")
      (value "10uF")
      (footprint "eagle-import:C0805")
      (libsource (lib "eagle-import") (part "C"))
    )
    (comp (ref "C141")
      (value "0.1uF")
      (footprint "eagle-import:C0603")
      (libsource (lib "eagle-import") (part "CC0603"))
    )
    (comp (ref "C142")
      (value "10pF")
      (footprint "eagle-import:C0603")
      (libsource (lib "eagle-import") (part "CC0603"))
    )
    (comp (ref "C143")
      (value "50pF")
      (footprint "eagle-import:C0603")
      (libsource (lib "eagle-import") (part "CC0603"))
    )
    (comp (ref "U22")
      (value "AD5791BRUZ")
      (footprint "eagle-import:SOP65P640X120-20N")
      (libsource (lib "eagle-import") (part "AD5791BRUZ"))
    )
    (comp (ref "U23")
      (value "AD8676ARZ")
      (footprint "eagle-import:SOIC127P600X175-8N")
      (libsource (lib "eagle-import") (part "AD8676ARZ"))
    )
    (comp (ref "C48")
      (value "10uF")
      (footprint "eagle-import:C0805")
      (libsource (lib "eagle-import") (part "C"))
    )
    (comp (ref "C49")
      (value "0.1uF")
      (footprint "eagle-import:C0603")
      (libsource (lib "eagle-import") (part "CC0603"))
    )
    (comp (ref "C50")
      (value "CC0603")
      (footprint "eagle-import:C0603")
      (libsource (lib "eagle-import") (part "CC0603"))
    )
    (comp (ref "C51")
      (value "10uF")
      (footprint "eagle-import:C0805")
      (libsource (lib "eagle-import") (part "C"))
    )
    (comp (ref "C52")
      (value "0.1uF")
      (footprint "eagle-import:C0603")
      (libsource (lib "eagle-import") (part "CC0603"))
    )
    (comp (ref "C53")
      (value "0.1uF")
      (footprint "eagle-import:C0603")
      (libsource (lib "eagle-import") (part "CC0603"))
    )
    (comp (ref "C54")
      (value "10uF")
      (footprint "eagle-import:C0805")
      (libsource (lib "eagle-import") (part "C"))
    )
    (comp (ref "C55")
      (value "0.1uF")
      (footprint "eagle-import:C0603")
      (libsource (lib "eagle-import") (part "CC0603"))
    )
    (comp (ref "C56")
      (value "10uF")
      (footprint "eagle-import:C0805")
      (libsource (lib "eagle-import") (part "C"))
    )
    (comp (ref "C57")
      (value "0.1uF")
      (footprint "eagle-import:C0603")
      (libsource (lib "eagle-import") (part "CC0603"))
    )
    (comp (ref "C58")
      (value "10pF")
      (footprint "eagle-import:C0603")
      (libsource (lib "eagle-import") (part "CC0603"))
    )
    (comp (ref "C59")
      (value "50pF")
      (footprint "eagle-import:C0603")
      (libsource (lib "eagle-import") (part "CC0603"))
    )
    (comp (ref "U8")
      (value "AD5791BRUZ")
      (footprint "eagle-import:SOP65P640X120-20N")
      (libsource (lib "eagle-import") (part "AD5791BRUZ"))
    )
    (comp (ref "U9")
      (value "AD8676ARZ")
      (footprint "eagle-import:SOIC127P600X175-8N")
      (libsource (lib "eagle-import") (part "AD8676ARZ"))
    )
    (comp (ref "C84")
      (value "10uF")
      (footprint "eagle-import:C0805")
      (libsource (lib "eagle-import") (part "C"))
    )
    (comp (ref "C85")
      (value "0.1uF")
      (footprint "eagle-import:C0603")
      (libsource (lib "eagle-import") (part "CC0603"))
    )
    (comp (ref "C86")
      (value "CC0603")
      (footprint "eagle-import:C0603")
      (libsource (lib "eagle-import") (part "CC0603"))
    )
    (comp (ref "C87")
      (value "10uF")
      (footprint "eagle-import:C0805")
      (libsource (lib "eagle-import") (part "C"))
    )
    (comp (ref "C88")
      (value "0.1uF")
      (footprint "eagle-import:C0603")
      (libsource (lib "eagle-import") (part "CC0603"))
    )
    (comp (ref "C89")
      (value "0.1uF")
      (footprint "eagle-import:C0603")
      (libsource (lib "eagle-import") (part "CC0603"))
    )
    (comp (ref "C90")
      (value "10uF")
      (footprint "eagle-import:C0805")
      (libsource (lib "eagle-import") (part "C"))
    )
    (comp (ref "C91")
      (value "0.1uF")
      (footprint "eagle-import:C0603")
      (libsource (lib "eagle-import") (part "CC0603"))
    )
    (comp (ref "C92")
      (value "10uF")
      (footprint "eagle-import:C0805")
      (libsource (lib "eagle-import") (part "C"))
    )
    (comp (ref "C93")
      (value "0.1uF")
      (footprint "eagle-import:C0603")
      (libsource (lib "eagle-import") (part "CC0603"))
    )
    (comp (ref "C94")
      (value "10pF")
      (footprint "eagle-import:C0603")
      (libsource (lib "eagle-import") (part "CC0603"))
    )
    (comp (ref "C95")
      (value "50pF")
      (footprint "eagle-import:C0603")
      (libsource (lib "eagle-import") (part "CC0603"))
    )
    (comp (ref "U14")
      (value "AD5791BRUZ")
      (footprint "eagle-import:SOP65P640X120-20N")
      (libsource (lib "eagle-import") (part "AD5791BRUZ"))
    )
    (comp (ref "U15")
      (value "AD8676ARZ")
      (footprint "eagle-import:SOIC127P600X175-8N")
      (libsource (lib "eagle-import") (part "AD8676ARZ"))
    )
    (comp (ref "C156")
      (value "10uF")
      (footprint "eagle-import:C0805")
      (libsource (lib "eagle-import") (part "C"))
    )
    (comp (ref "C157")
      (value "0.1uF")
      (footprint "eagle-import:C0603")
      (libsource (lib "eagle-import") (part "CC0603"))
    )
    (comp (ref "C158")
      (value "CC0603")
      (footprint "eagle-import:C0603")
      (libsource (lib "eagle-import") (part "CC0603"))
    )
    (comp (ref "C159")
      (value "10uF")
      (footprint "eagle-import:C0805")
      (libsource (lib "eagle-import") (part "C"))
    )
    (comp (ref "C160")
      (value "0.1uF")
      (footprint "eagle-import:C0603")
      (libsource (lib "eagle-import") (part "CC0603"))
    )
    (comp (ref "C161")
      (value "0.1uF")
      (footprint "eagle-import:C0603")
      (libsource (lib "eagle-import") (part "CC0603"))
    )
    (comp (ref "C162")
      (value "10uF")
      (footprint "eagle-import:C0805")
      (libsource (lib "eagle-import") (part "C"))
    )
    (comp (ref "C163")
      (value "0.1uF")
      (footprint "eagle-import:C0603")
      (libsource (lib "eagle-import") (part "CC0603"))
    )
    (comp (ref "C164")
      (value "10uF")
      (footprint "eagle-import:C0805")
      (libsource (lib "eagle-import") (part "C"))
    )
    (comp (ref "C165")
      (value "0.1uF")
      (footprint "eagle-import:C0603")
      (libsource (lib "eagle-import") (part "CC0603"))
    )
    (comp (ref "C166")
      (value "10pF")
      (footprint "eagle-import:C0603")
      (libsource (lib "eagle-import") (part "CC0603"))
    )
    (comp (ref "C167")
      (value "50pF")
      (footprint "eagle-import:C0603")
      (libsource (lib "eagle-import") (part "CC0603"))
    )
    (comp (ref "U26")
      (value "AD5791BRUZ")
      (footprint "eagle-import:SOP65P640X120-20N")
      (libsource (lib "eagle-import") (part "AD5791BRUZ"))
    )
    (comp (ref "U27")
      (value "AD8676ARZ")
      (footprint "eagle-import:SOIC127P600X175-8N")
      (libsource (lib "eagle-import") (part "AD8676ARZ"))
    )
    (comp (ref "C168")
      (value "0.1uF")
      (footprint "eagle-import:C0603")
      (libsource (lib "eagle-import") (part "CC0603"))
    )
    (comp (ref "C169")
      (value "10uF")
      (footprint "eagle-import:C0805")
      (libsource (lib "eagle-import") (part "C"))
    )
    (comp (ref "C170")
      (value "0.1uF")
      (footprint "eagle-import:C0603")
      (libsource (lib "eagle-import") (part "CC0603"))
    )
    (comp (ref "C171")
      (value "10uF")
      (footprint "eagle-import:C0805")
      (libsource (lib "eagle-import") (part "C"))
    )
    (comp (ref "JP2")
      (value "JP6Q")
      (footprint "eagle-import:JP6Q")
      (libsource (lib "eagle-import") (part "JP6Q"))
    )
    (comp (ref "JP3")
      (value "JP6Q")
      (footprint "eagle-import:JP6Q")
      (libsource (lib "eagle-import") (part "JP6Q"))
    )
    (comp (ref "R4")
      (value "50Ω")
      (footprint "eagle-import:R0603")
      (libsource (lib "eagle-import") (part "RR0603"))
    )
    (comp (ref "R5")
      (value "50Ω")
      (footprint "eagle-import:R0603")
      (libsource (lib "eagle-import") (part "RR0603"))
    )
    (comp (ref "U28")
      (value "AD581KH")
      (footprint "eagle-import:TO254P939X470-3P")
      (libsource (lib "eagle-import") (part "AD581KH"))
    )
    (comp (ref "U29")
      (value "ADP3339-3.3")
      (footprint "eagle-import:SOT230P700X180-4N")
      (fields (field (name "MPN") "ADP3339AKCZ-3.3-R7"))
      (libsource (lib "eagle-import") (part "ADP3339AKCZ-3.3-R7"))
    )
    (comp (ref "U30")
      (value "AD8620ARZ")
      (footprint "eagle-import:SOIC127P600X175-8N")
      (libsource (lib "eagle-import") (part "AD8620ARZ"))
    )
    (comp (ref "X1")
      (value "F50HP")
      (footprint "eagle-import:F50HP")
      (libsource (lib "eagle-import") (part "F50HP"))
    )
  )
  (nets
    (net (code "1") (name "+5V") (class "Default")
      (node (ref "J1") (pin "A27") (pinfunction "A27_A27") (pintype "passive"))
      (node (ref "J1") (pin "A28") (pinfunction "A28_A28") (pintype "passive"))
      (node (ref "J1") (pin "A29") (pinfunction "A29_A29") (pintype "passive"))
      (node (ref "J1") (pin "B27") (pinfunction "B27_B27") (pintype "passive"))
      (node (ref "J1") (pin "B28") (pinfunction "B28_B28") (pintype "passive"))
      (node (ref "J1") (pin "B29") (pinfunction "B29_B29") (pintype "passive"))
      (node (ref "J1") (pin "C27") (pinfunction "C27_C27") (pintype "passive"))
      (node (ref "J1") (pin "C28") (pinfunction "C28_C28") (pintype "passive"))
      (node (ref "J1") (pin "C29") (pinfunction "C29_C29") (pintype "passive"))
      (node (ref "J1") (pin "D27") (pinfunction "D27_D27") (pintype "passive"))
      (node (ref "J1") (pin "D28") (pinfunction "D28_D28") (pintype "passive"))
      (node (ref "J1") (pin "D29") (pinfunction "D29_D29") (pintype "passive"))
      (node (ref "J1") (pin "E27") (pinfunction "E27_E27") (pintype "passive"))
      (node (ref "J1") (pin "E28") (pinfunction "E28_E28") (pintype "passive"))
      (node (ref "J1") (pin "E29") (pinfunction "E29_E29") (pintype "passive"))
    )
    (net (code "2") (name "+PWR") (class "Default")
      (node (ref "C170") (pin "1") (pinfunction "1_1") (pintype "passive"))
      (node (ref "C171") (pin "1") (pinfunction "1_1") (pintype "passive"))
      (node (ref "JP3") (pin "10") (pinfunction "10_10") (pintype "passive"))
      (node (ref "JP3") (pin "12") (pinfunction "12_12") (pintype "passive"))
      (node (ref "JP3") (pin "2") (pinfunction "2_2") (pintype "passive"))
      (node (ref "JP3") (pin "4") (pinfunction "4_4") (pintype "passive"))
      (node (ref "JP3") (pin "6") (pinfunction "6_6") (pintype "passive"))
      (node (ref "JP3") (pin "8") (pinfunction "8_8") (pintype "passive"))
      (node (ref "U30") (pin "8") (pinfunction "V+_8") (pintype "power_in"))
    )
    (net (code "3") (name "+VPWR") (class "Default")
      (node (ref "C102") (pin "2") (pinfunction "2_2") (pintype "passive"))
      (node (ref "C103") (pin "2") (pinfunction "2_2") (pintype "passive"))
      (node (ref "C108") (pin "2") (pinfunction "2_2") (pintype "passive"))
      (node (ref "C109") (pin "2") (pinfunction "2_2") (pintype "passive"))
      (node (ref "C11") (pin "2") (pinfunction "2_2") (pintype "passive"))
      (node (ref "C114") (pin "2") (pinfunction "2_2") (pintype "passive"))
      (node (ref "C115") (pin "2") (pinfunction "2_2") (pintype "passive"))
      (node (ref "C12") (pin "2") (pinfunction "2_2") (pintype "passive"))
      (node (ref "C120") (pin "2") (pinfunction "2_2") (pintype "passive"))
      (node (ref "C121") (pin "2") (pinfunction "2_2") (pintype "passive"))
      (node (ref "C126") (pin "2") (pinfunction "2_2") (pintype "passive"))
      (node (ref "C127") (pin "2") (pinfunction "2_2") (pintype "passive"))
      (node (ref "C132") (pin "2") (pinfunction "2_2") (pintype "passive"))
      (node (ref "C133") (pin "2") (pinfunction "2_2") (pintype "passive"))
      (node (ref "C138") (pin "2") (pinfunction "2_2") (pintype "passive"))
      (node (ref "C139") (pin "2") (pinfunction "2_2") (pintype "passive"))
      (node (ref "C144") (pin "2") (pinfunction "2_2") (pintype "passive"))
      (node (ref "C145") (pin "2") (pinfunction "2_2") (pintype "passive"))
      (node (ref "C150") (pin "2") (pinfunction "2_2") (pintype "passive"))
      (node (ref "C151") (pin "2") (pinfunction "2_2") (pintype "passive"))
      (node (ref "C156") (pin "2") (pinfunction "2_2") (pintype "passive"))
      (node (ref "C157") (pin "2") (pinfunction "2_2") (pintype "passive"))
      (node (ref "C162") (pin "2") (pinfunction "2_2") (pintype "passive"))
      (node (ref "C163") (pin "2") (pinfunction "2_2") (pintype "passive"))
      (node (ref "C30") (pin "2") (pinfunction "2_2") (pintype "passive"))
      (node (ref "C31") (pin "2") (pinfunction "2_2") (pintype "passive"))
      (node (ref "C36") (pin "2") (pinfunction "2_2") (pintype "passive"))
      (node (ref "C37") (pin "2") (pinfunction "2_2") (pintype "passive"))
      (node (ref "C42") (pin "2") (pinfunction "2_2") (pintype "passive"))
      (node (ref "C43") (pin "2") (pinfunction "2_2") (pintype "passive"))
      (node (ref "C48") (pin "2") (pinfunction "2_2") (pintype "passive"))
      (node (ref "C49") (pin "2") (pinfunction "2_2") (pintype "passive"))
      (node (ref "C54") (pin "2") (pinfunction "2_2") (pintype "passive"))
      (node (ref "C55") (pin "2") (pinfunction "2_2") (pintype "passive"))
      (node (ref "C60") (pin "2") (pinfunction "2_2") (pintype "passive"))
      (node (ref "C61") (pin "2") (pinfunction "2_2") (pintype "passive"))
      (node (ref "C66") (pin "2") (pinfunction "2_2") (pintype "passive"))
      (node (ref "C67") (pin "2") (pinfunction "2_2") (pintype "passive"))
      (node (ref "C72") (pin "2") (pinfunction "2_2") (pintype "passive"))
      (node (ref "C73") (pin "2") (pinfunction "2_2") (pintype "passive"))
      (node (ref "C78") (pin "2") (pinfunction "2_2") (pintype "passive"))
      (node (ref "C79") (pin "2") (pinfunction "2_2") (pintype "passive"))
      (node (ref "C84") (pin "2") (pinfunction "2_2") (pintype "passive"))
      (node (ref "C85") (pin "2") (pinfunction "2_2") (pintype "passive"))
      (node (ref "C90") (pin "2") (pinfunction "2_2") (pintype "passive"))
      (node (ref "C91") (pin "2") (pinfunction "2_2") (pintype "passive"))
      (node (ref "C96") (pin "2") (pinfunction "2_2") (pintype "passive"))
      (node (ref "C97") (pin "2") (pinfunction "2_2") (pintype "passive"))
      (node (ref "J1") (pin "D34") (pinfunction "D34_D34") (pintype "passive"))
      (node (ref "J1") (pin "D35") (pinfunction "D35_D35") (pintype "passive"))
      (node (ref "J1") (pin "D36") (pinfunction "D36_D36") (pintype "passive"))
      (node (ref "J1") (pin "D37") (pinfunction "D37_D37") (pintype "passive"))
      (node (ref "J1") (pin "E34") (pinfunction "E34_E34") (pintype "passive"))
      (node (ref "J1") (pin "E35") (pinfunction "E35_E35") (pintype "passive"))
      (node (ref "J1") (pin "E36") (pinfunction "E36_E36") (pintype "passive"))
      (node (ref "J1") (pin "E37") (pinfunction "E37_E37") (pintype "passive"))
      (node (ref "U10") (pin "5") (pinfunction "VDD_5") (pintype "power_in"))
      (node (ref "U11") (pin "8") (pinfunction "V+_8") (pintype "power_in"))
      (node (ref "U12") (pin "5") (pinfunction "VDD_5") (pintype "power_in"))
      (node (ref "U13") (pin "8") (pinfunction "V+_8") (pintype "power_in"))
      (node (ref "U14") (pin "5") (pinfunction "VDD_5") (pintype "power_in"))
      (node (ref "U15") (pin "8") (pinfunction "V+_8") (pintype "power_in"))
      (node (ref "U16") (pin "5") (pinfunction "VDD_5") (pintype "power_in"))
      (node (ref "U17") (pin "8") (pinfunction "V+_8") (pintype "power_in"))
      (node (ref "U18") (pin "5") (pinfunction "VDD_5") (pintype "power_in"))
      (node (ref "U19") (pin "8") (pinfunction "V+_8") (pintype "power_in"))
      (node (ref "U20") (pin "5") (pinfunction "VDD_5") (pintype "power_in"))
      (node (ref "U21") (pin "8") (pinfunction "V+_8") (pintype "power_in"))
      (node (ref "U22") (pin "5") (pinfunction "VDD_5") (pintype "power_in"))
      (node (ref "U23") (pin "8") (pinfunction "V+_8") (pintype "power_in"))
      (node (ref "U24") (pin "5") (pinfunction "VDD_5") (pintype "power_in"))
      (node (ref "U25") (pin "8") (pinfunction "V+_8") (pintype "power_in"))
      (node (ref "U26") (pin "5") (pinfunction "VDD_5") (pintype "power_in"))
      (node (ref "U27") (pin "8") (pinfunction "V+_8") (pintype "power_in"))
      (node (ref "U4") (pin "5") (pinfunction "VDD_5") (pintype "power_in"))
      (node (ref "U5") (pin "8") (pinfunction "V+_8") (pintype "power_in"))
      (node (ref "U6") (pin "5") (pinfunction "VDD_5") (pintype "power_in"))
      (node (ref "U7") (pin "8") (pinfunction "V+_8") (pintype "power_in"))
      (node (ref "U8") (pin "5") (pinfunction "VDD_5") (pintype "power_in"))
      (node (ref "U9") (pin "8") (pinfunction "V+_8") (pintype "power_in"))
    )
    (net (code "4") (name "+VS") (class "Default")
      (node (ref "U28") (pin "1") (pinfunction "+VS_1") (pintype "power_in"))
    )
    (net (code "5") (name "-PWR") (class "Default")
      (node (ref "C168") (pin "1") (pinfunction "1_1") (pintype "passive"))
      (node (ref "C169") (pin "1") (pinfunction "1_1") (pintype "passive"))
      (node (ref "JP2") (pin "10") (pinfunction "10_10") (pintype "passive"))
      (node (ref "JP2") (pin "12") (pinfunction "12_12") (pintype "passive"))
      (node (ref "JP2") (pin "2") (pinfunction "2_2") (pintype "passive"))
      (node (ref "JP2") (pin "4") (pinfunction "4_4") (pintype "passive"))
      (node (ref "JP2") (pin "6") (pinfunction "6_6") (pintype "passive"))
      (node (ref "JP2") (pin "8") (pinfunction "8_8") (pintype "passive"))
      (node (ref "U30") (pin "4") (pinfunction "V-_4") (pintype "power_in"))
    )
    (net (code "6") (name "-VPWR") (class "Default")
      (node (ref "C100") (pin "2") (pinfunction "2_2") (pintype "passive"))
      (node (ref "C104") (pin "2") (pinfunction "2_2") (pintype "passive"))
      (node (ref "C105") (pin "2") (pinfunction "2_2") (pintype "passive"))
      (node (ref "C111") (pin "2") (pinfunction "2_2") (pintype "passive"))
      (node (ref "C112") (pin "2") (pinfunction "2_2") (pintype "passive"))
      (node (ref "C116") (pin "2") (pinfunction "2_2") (pintype "passive"))
      (node (ref "C117") (pin "2") (pinfunction "2_2") (pintype "passive"))
      (node (ref "C123") (pin "2") (pinfunction "2_2") (pintype "passive"))
      (node (ref "C124") (pin "2") (pinfunction "2_2") (pintype "passive"))
      (node (ref "C128") (pin "2") (pinfunction "2_2") (pintype "passive"))
      (node (ref "C129") (pin "2") (pinfunction "2_2") (pintype "passive"))
      (node (ref "C135") (pin "2") (pinfunction "2_2") (pintype "passive"))
      (node (ref "C136") (pin "2") (pinfunction "2_2") (pintype "passive"))
      (node (ref "C140") (pin "2") (pinfunction "2_2") (pintype "passive"))
      (node (ref "C141") (pin "2") (pinfunction "2_2") (pintype "passive"))
      (node (ref "C147") (pin "2") (pinfunction "2_2") (pintype "passive"))
      (node (ref "C148") (pin "2") (pinfunction "2_2") (pintype "passive"))
      (node (ref "C152") (pin "2") (pinfunction "2_2") (pintype "passive"))
      (node (ref "C153") (pin "2") (pinfunction "2_2") (pintype "passive"))
      (node (ref "C159") (pin "2") (pinfunction "2_2") (pintype "passive"))
      (node (ref "C160") (pin "2") (pinfunction "2_2") (pintype "passive"))
      (node (ref "C164") (pin "2") (pinfunction "2_2") (pintype "passive"))
      (node (ref "C165") (pin "2") (pinfunction "2_2") (pintype "passive"))
      (node (ref "C27") (pin "2") (pinfunction "2_2") (pintype "passive"))
      (node (ref "C28") (pin "2") (pinfunction "2_2") (pintype "passive"))
      (node (ref "C32") (pin "2") (pinfunction "2_2") (pintype "passive"))
      (node (ref "C33") (pin "2") (pinfunction "2_2") (pintype "passive"))
      (node (ref "C39") (pin "2") (pinfunction "2_2") (pintype "passive"))
      (node (ref "C40") (pin "2") (pinfunction "2_2") (pintype "passive"))
      (node (ref "C44") (pin "2") (pinfunction "2_2") (pintype "passive"))
      (node (ref "C45") (pin "2") (pinfunction "2_2") (pintype "passive"))
      (node (ref "C51") (pin "2") (pinfunction "2_2") (pintype "passive"))
      (node (ref "C52") (pin "2") (pinfunction "2_2") (pintype "passive"))
      (node (ref "C56") (pin "2") (pinfunction "2_2") (pintype "passive"))
      (node (ref "C57") (pin "2") (pinfunction "2_2") (pintype "passive"))
      (node (ref "C63") (pin "2") (pinfunction "2_2") (pintype "passive"))
      (node (ref "C64") (pin "2") (pinfunction "2_2") (pintype "passive"))
      (node (ref "C68") (pin "2") (pinfunction "2_2") (pintype "passive"))
      (node (ref "C69") (pin "2") (pinfunction "2_2") (pintype "passive"))
      (node (ref "C75") (pin "2") (pinfunction "2_2") (pintype "passive"))
      (node (ref "C76") (pin "2") (pinfunction "2_2") (pintype "passive"))
      (node (ref "C80") (pin "2") (pinfunction "2_2") (pintype "passive"))
      (node (ref "C81") (pin "2") (pinfunction "2_2") (pintype "passive"))
      (node (ref "C87") (pin "2") (pinfunction "2_2") (pintype "passive"))
      (node (ref "C88") (pin "2") (pinfunction "2_2") (pintype "passive"))
      (node (ref "C92") (pin "2") (pinfunction "2_2") (pintype "passive"))
      (node (ref "C93") (pin "2") (pinfunction "2_2") (pintype "passive"))
      (node (ref "C99") (pin "2") (pinfunction "2_2") (pintype "passive"))
      (node (ref "J1") (pin "A34") (pinfunction "A34_A34") (pintype "passive"))
      (node (ref "J1") (pin "A35") (pinfunction "A35_A35") (pintype "passive"))
      (node (ref "J1") (pin "A36") (pinfunction "A36_A36") (pintype "passive"))
      (node (ref "J1") (pin "A37") (pinfunction "A37_A37") (pintype "passive"))
      (node (ref "J1") (pin "B34") (pinfunction "B34_B34") (pintype "passive"))
      (node (ref "J1") (pin "B35") (pinfunction "B35_B35") (pintype "passive"))
      (node (ref "J1") (pin "B36") (pinfunction "B36_B36") (pintype "passive"))
      (node (ref "J1") (pin "B37") (pinfunction "B37_B37") (pintype "passive"))
      (node (ref "U10") (pin "18") (pinfunction "VSS_18") (pintype "power_in"))
      (node (ref "U11") (pin "4") (pinfunction "V-_4") (pintype "power_in"))
      (node (ref "U12") (pin "18") (pinfunction "VSS_18") (pintype "power_in"))
      (node (ref "U13") (pin "4") (pinfunction "V-_4") (pintype "power_in"))
      (node (ref "U14") (pin "18") (pinfunction "VSS_18") (pintype "power_in"))
      (node (ref "U15") (pin "4") (pinfunction "V-_4") (pintype "power_in"))
      (node (ref "U16") (pin "18") (pinfunction "VSS_18") (pintype "power_in"))
      (node (ref "U17") (pin "4") (pinfunction "V-_4") (pintype "power_in"))
      (node (ref "U18") (pin "18") (pinfunction "VSS_18") (pintype "power_in"))
      (node (ref "U19") (pin "4") (pinfunction "V-_4") (pintype "power_in"))
      (node (ref "U20") (pin "18") (pinfunction "VSS_18") (pintype "power_in"))
      (node (ref "U21") (pin "4") (pinfunction "V-_4") (pintype "power_in"))
      (node (ref "U22") (pin "18") (pinfunction "VSS_18") (pintype "power_in"))
      (node (ref "U23") (pin "4") (pinfunction "V-_4") (pintype "power_in"))
      (node (ref "U24") (pin "18") (pinfunction "VSS_18") (pintype "power_in"))
      (node (ref "U25") (pin "4") (pinfunction "V-_4") (pintype "power_in"))
      (node (ref "U26") (pin "18") (pinfunction "VSS_18") (pintype "power_in"))
      (node (ref "U27") (pin "4") (pinfunction "V-_4") (pintype "power_in"))
      (node (ref "U4") (pin "18") (pinfunction "VSS_18") (pintype "power_in"))
      (node (ref "U5") (pin "4") (pinfunction "V-_4") (pintype "power_in"))
      (node (ref "U6") (pin "18") (pinfunction "VSS_18") (pintype "power_in"))
      (node (ref "U7") (pin "4") (pinfunction "V-_4") (pintype "power_in"))
      (node (ref "U8") (pin "18") (pinfunction "VSS_18") (pintype "power_in"))
      (node (ref "U9") (pin "4") (pinfunction "V-_4") (pintype "power_in"))
    )
    (net (code "7") (name "0B0") (class "Default")
      (node (ref "ISO1") (pin "4") (pinfunction "A2_4") (pintype "bidirectional"))
      (node (ref "U2") (pin "3") (pinfunction "A1_3") (pintype "bidirectional"))
    )
    (net (code "8") (name "0B1") (class "Default")
      (node (ref "ISO1") (pin "3") (pinfunction "A1_3") (pintype "bidirectional"))
      (node (ref "U2") (pin "5") (pinfunction "A2_5") (pintype "bidirectional"))
    )
    (net (code "9") (name "0B2") (class "Default")
      (node (ref "ISO2") (pin "7") (pinfunction "A5_7") (pintype "bidirectional"))
      (node (ref "U2") (pin "6") (pinfunction "A3_6") (pintype "bidirectional"))
    )
    (net (code "10") (name "0B3") (class "Default")
      (node (ref "ISO2") (pin "6") (pinfunction "A4_6") (pintype "bidirectional"))
      (node (ref "U2") (pin "8") (pinfunction "A4_8") (pintype "bidirectional"))
    )
    (net (code "11") (name "0B4") (class "Default")
      (node (ref "ISO2") (pin "5") (pinfunction "A3_5") (pintype "bidirectional"))
      (node (ref "U2") (pin "9") (pinfunction "A5_9") (pintype "bidirectional"))
    )
    (net (code "12") (name "0B5") (class "Default")
      (node (ref "ISO2") (pin "4") (pinfunction "A2_4") (pintype "bidirectional"))
      (node (ref "U2") (pin "10") (pinfunction "A6_10") (pintype "bidirectional"))
    )
    (net (code "13") (name "0B6") (class "Default")
      (node (ref "ISO2") (pin "3") (pinfunction "A1_3") (pintype "bidirectional"))
      (node (ref "U2") (pin "12") (pinfunction "A7_12") (pintype "bidirectional"))
    )
    (net (code "14") (name "0B7") (class "Default")
      (node (ref "ISO3") (pin "7") (pinfunction "A5_7") (pintype "bidirectional"))
      (node (ref "U2") (pin "13") (pinfunction "A8_13") (pintype "bidirectional"))
    )
    (net (code "15") (name "0B8") (class "Default")
      (node (ref "ISO3") (pin "6") (pinfunction "A4_6") (pintype "bidirectional"))
      (node (ref "U2") (pin "14") (pinfunction "A9_14") (pintype "bidirectional"))
    )
    (net (code "16") (name "0B9") (class "Default")
      (node (ref "ISO3") (pin "5") (pinfunction "A3_5") (pintype "bidirectional"))
      (node (ref "U2") (pin "15") (pinfunction "A10_15") (pintype "bidirectional"))
    )
    (net (code "17") (name "0B10") (class "Default")
      (node (ref "ISO3") (pin "4") (pinfunction "A2_4") (pintype "bidirectional"))
      (node (ref "U2") (pin "16") (pinfunction "A11_16") (pintype "bidirectional"))
    )
    (net (code "18") (name "0B11") (class "Default")
      (node (ref "ISO3") (pin "3") (pinfunction "A1_3") (pintype "bidirectional"))
      (node (ref "U2") (pin "17") (pinfunction "A12_17") (pintype "bidirectional"))
    )
    (net (code "19") (name "0B12") (class "Default")
      (node (ref "ISO4") (pin "7") (pinfunction "A5_7") (pintype "bidirectional"))
      (node (ref "U2") (pin "19") (pinfunction "A13_19") (pintype "bidirectional"))
    )
    (net (code "20") (name "0B13") (class "Default")
      (node (ref "ISO4") (pin "6") (pinfunction "A4_6") (pintype "bidirectional"))
      (node (ref "U2") (pin "20") (pinfunction "A14_20") (pintype "bidirectional"))
    )
    (net (code "21") (name "0B14") (class "Default")
      (node (ref "ISO4") (pin "5") (pinfunction "A3_5") (pintype "bidirectional"))
      (node (ref "U2") (pin "21") (pinfunction "A15_21") (pintype "bidirectional"))
    )
    (net (code "22") (name "0B15") (class "Default")
      (node (ref "ISO4") (pin "4") (pinfunction "A2_4") (pintype "bidirectional"))
      (node (ref "U2") (pin "23") (pinfunction "A16_23") (pintype "bidirectional"))
    )
    (net (code "23") (name "0B16") (class "Default")
      (node (ref "ISO4") (pin "3") (pinfunction "A1_3") (pintype "bidirectional"))
      (node (ref "U2") (pin "24") (pinfunction "A17_24") (pintype "bidirectional"))
    )
    (net (code "24") (name "0B17") (class "Default")
      (node (ref "ISO5") (pin "7") (pinfunction "A5_7") (pintype "bidirectional"))
      (node (ref "U2") (pin "26") (pinfunction "A18_26") (pintype "bidirectional"))
    )
    (net (code "25") (name "1B0") (class "Default")
      (node (ref "ISO5") (pin "6") (pinfunction "A4_6") (pintype "bidirectional"))
      (node (ref "U3") (pin "3") (pinfunction "A1_3") (pintype "bidirectional"))
    )
    (net (code "26") (name "1B1") (class "Default")
      (node (ref "ISO5") (pin "5") (pinfunction "A3_5") (pintype "bidirectional"))
      (node (ref "U3") (pin "5") (pinfunction "A2_5") (pintype "bidirectional"))
    )
    (net (code "27") (name "1B2") (class "Default")
      (node (ref "ISO5") (pin "4") (pinfunction "A2_4") (pintype "bidirectional"))
      (node (ref "U3") (pin "6") (pinfunction "A3_6") (pintype "bidirectional"))
    )
    (net (code "28") (name "1B3") (class "Default")
      (node (ref "ISO5") (pin "3") (pinfunction "A1_3") (pintype "bidirectional"))
      (node (ref "U3") (pin "8") (pinfunction "A4_8") (pintype "bidirectional"))
    )
    (net (code "29") (name "1B4") (class "Default")
      (node (ref "ISO6") (pin "7") (pinfunction "A5_7") (pintype "bidirectional"))
      (node (ref "U3") (pin "9") (pinfunction "A5_9") (pintype "bidirectional"))
    )
    (net (code "30") (name "1B5") (class "Default")
      (node (ref "ISO6") (pin "6") (pinfunction "A4_6") (pintype "bidirectional"))
      (node (ref "U3") (pin "10") (pinfunction "A6_10") (pintype "bidirectional"))
    )
    (net (code "31") (name "1B6") (class "Default")
      (node (ref "ISO6") (pin "5") (pinfunction "A3_5") (pintype "bidirectional"))
      (node (ref "U3") (pin "12") (pinfunction "A7_12") (pintype "bidirectional"))
    )
    (net (code "32") (name "1B7") (class "Default")
      (node (ref "ISO6") (pin "4") (pinfunction "A2_4") (pintype "bidirectional"))
      (node (ref "U3") (pin "13") (pinfunction "A8_13") (pintype "bidirectional"))
    )
    (net (code "33") (name "1B8") (class "Default")
      (node (ref "ISO6") (pin "3") (pinfunction "A1_3") (pintype "bidirectional"))
      (node (ref "U3") (pin "14") (pinfunction "A9_14") (pintype "bidirectional"))
    )
    (net (code "34") (name "1B9") (class "Default")
      (node (ref "ISO7") (pin "7") (pinfunction "A5_7") (pintype "bidirectional"))
      (node (ref "U3") (pin "15") (pinfunction "A10_15") (pintype "bidirectional"))
    )
    (net (code "35") (name "1B10") (class "Default")
      (node (ref "ISO7") (pin "6") (pinfunction "A4_6") (pintype "bidirectional"))
      (node (ref "U3") (pin "16") (pinfunction "A11_16") (pintype "bidirectional"))
    )
    (net (code "36") (name "1B11") (class "Default")
      (node (ref "ISO7") (pin "5") (pinfunction "A3_5") (pintype "bidirectional"))
      (node (ref "U3") (pin "17") (pinfunction "A12_17") (pintype "bidirectional"))
    )
    (net (code "37") (name "1B12") (class "Default")
      (node (ref "ISO7") (pin "4") (pinfunction "A2_4") (pintype "bidirectional"))
      (node (ref "U3") (pin "19") (pinfunction "A13_19") (pintype "bidirectional"))
    )
    (net (code "38") (name "1B13") (class "Default")
      (node (ref "ISO7") (pin "3") (pinfunction "A1_3") (pintype "bidirectional"))
      (node (ref "U3") (pin "20") (pinfunction "A14_20") (pintype "bidirectional"))
    )
    (net (code "39") (name "1B14") (class "Default")
      (node (ref "ISO8") (pin "7") (pinfunction "A5_7") (pintype "bidirectional"))
      (node (ref "U3") (pin "21") (pinfunction "A15_21") (pintype "bidirectional"))
    )
    (net (code "40") (name "1B15") (class "Default")
      (node (ref "ISO8") (pin "6") (pinfunction "A4_6") (pintype "bidirectional"))
      (node (ref "U3") (pin "23") (pinfunction "A16_23") (pintype "bidirectional"))
    )
    (net (code "41") (name "1B16") (class "Default")
      (node (ref "ISO8") (pin "5") (pinfunction "A3_5") (pintype "bidirectional"))
      (node (ref "U3") (pin "24") (pinfunction "A17_24") (pintype "bidirectional"))
    )
    (net (code "42") (name "1B17") (class "Default")
      (node (ref "ISO8") (pin "4") (pinfunction "A2_4") (pintype "bidirectional"))
      (node (ref "U3") (pin "26") (pinfunction "A18_26") (pintype "bidirectional"))
    )
    (net (code "43") (name "2B0-1") (class "Default")
      (node (ref "ISO8") (pin "3") (pinfunction "A1_3") (pintype "bidirectional"))
      (node (ref "U40") (pin "6") (pinfunction "1A2_6") (pintype "bidirectional"))
    )
    (net (code "44") (name "2B0-2") (class "Default")
      (node (ref "ISO11") (pin "7") (pinfunction "A5_7") (pintype "bidirectional"))
      (node (ref "U40") (pin "7") (pinfunction "1A3_7") (pintype "bidirectional"))
    )
    (net (code "45") (name "2B0-3") (class "Default")
      (node (ref "ISO11") (pin "6") (pinfunction "A4_6") (pintype "bidirectional"))
      (node (ref "U40") (pin "9") (pinfunction "1A4_9") (pintype "bidirectional"))
    )
    (net (code "46") (name "2B0-4") (class "Default")
      (node (ref "ISO11") (pin "5") (pinfunction "A3_5") (pintype "bidirectional"))
      (node (ref "U40") (pin "11") (pinfunction "1A5_11") (pintype "bidirectional"))
    )
    (net (code "47") (name "2B0-5") (class "Default")
      (node (ref "ISO11") (pin "4") (pinfunction "A2_4") (pintype "bidirectional"))
      (node (ref "U40") (pin "13") (pinfunction "1A6_13") (pintype "bidirectional"))
    )
    (net (code "48") (name "2B0-7") (class "Default")
      (node (ref "ISO11") (pin "3") (pinfunction "A1_3") (pintype "bidirectional"))
      (node (ref "U40") (pin "16") (pinfunction "1A8_16") (pintype "bidirectional"))
    )
    (net (code "49") (name "2B1-0") (class "Default")
      (node (ref "ISO9") (pin "14") (pinfunction "B1_14") (pintype "bidirectional"))
      (node (ref "U40") (pin "17") (pinfunction "2A1_17") (pintype "bidirectional"))
    )
    (net (code "50") (name "2B1-1") (class "Default")
      (node (ref "ISO9") (pin "13") (pinfunction "B2_13") (pintype "bidirectional"))
      (node (ref "U40") (pin "19") (pinfunction "2A2_19") (pintype "bidirectional"))
    )
    (net (code "51") (name "2B1-2") (class "Default")
      (node (ref "ISO9") (pin "12") (pinfunction "B3_12") (pintype "bidirectional"))
      (node (ref "U40") (pin "20") (pinfunction "2A3_20") (pintype "bidirectional"))
    )
    (net (code "52") (name "2B1-3") (class "Default")
      (node (ref "ISO9") (pin "11") (pinfunction "B4_11") (pintype "bidirectional"))
      (node (ref "U40") (pin "22") (pinfunction "2A4_22") (pintype "bidirectional"))
    )
    (net (code "53") (name "2B1-4") (class "Default")
      (node (ref "ISO9") (pin "10") (pinfunction "B5_10") (pintype "bidirectional"))
      (node (ref "U40") (pin "23") (pinfunction "2A5_23") (pintype "bidirectional"))
    )
    (net (code "54") (name "2B1-5") (class "Default")
      (node (ref "ISO10") (pin "14") (pinfunction "B1_14") (pintype "bidirectional"))
      (node (ref "U40") (pin "25") (pinfunction "2A6_25") (pintype "bidirectional"))
    )
    (net (code "55") (name "2B1-6") (class "Default")
      (node (ref "ISO10") (pin "13") (pinfunction "B2_13") (pintype "bidirectional"))
      (node (ref "U40") (pin "27") (pinfunction "2A7_27") (pintype "bidirectional"))
    )
    (net (code "56") (name "2B1-7") (class "Default")
      (node (ref "ISO10") (pin "12") (pinfunction "B3_12") (pintype "bidirectional"))
      (node (ref "U40") (pin "29") (pinfunction "2A8_29") (pintype "bidirectional"))
    )
    (net (code "57") (name "AGND") (class "Default")
      (node (ref "ISO1") (pin "15") (pinfunction "GND2_15") (pintype "bidirectional"))
      (node (ref "ISO1") (pin "9") (pinfunction "GND2_9") (pintype "bidirectional"))
      (node (ref "ISO11") (pin "15") (pinfunction "GND2_15") (pintype "bidirectional"))
      (node (ref "ISO11") (pin "9") (pinfunction "GND2_9") (pintype "bidirectional"))
      (node (ref "ISO2") (pin "15") (pinfunction "GND2_15") (pintype "bidirectional"))
      (node (ref "ISO2") (pin "9") (pinfunction "GND2_9") (pintype "bidirectional"))
      (node (ref "ISO3") (pin "15") (pinfunction "GND2_15") (pintype "bidirectional"))
      (node (ref "ISO3") (pin "9") (pinfunction "GND2_9") (pintype "bidirectional"))
      (node (ref "ISO4") (pin "15") (pinfunction "GND2_15") (pintype "bidirectional"))
      (node (ref "ISO4") (pin "9") (pinfunction "GND2_9") (pintype "bidirectional"))
      (node (ref "ISO5") (pin "15") (pinfunction "GND2_15") (pintype "bidirectional"))
      (node (ref "ISO5") (pin "9") (pinfunction "GND2_9") (pintype "bidirectional"))
      (node (ref "ISO6") (pin "15") (pinfunction "GND2_15") (pintype "bidirectional"))
      (node (ref "ISO6") (pin "9") (pinfunction "GND2_9") (pintype "bidirectional"))
      (node (ref "ISO7") (pin "15") (pinfunction "GND2_15") (pintype "bidirectional"))
      (node (ref "ISO7") (pin "9") (pinfunction "GND2_9") (pintype "bidirectional"))
      (node (ref "ISO8") (pin "15") (pinfunction "GND2_15") (pintype "bidirectional"))
      (node (ref "ISO8") (pin "9") (pinfunction "GND2_9") (pintype "bidirectional"))
      (node (ref "J1") (pin "A26") (pinfunction "A26_A26") (pintype "passive"))
      (node (ref "J1") (pin "A30") (pinfunction "A30_A30") (pintype "passive"))
      (node (ref "J1") (pin "A31") (pinfunction "A31_A31") (pintype "passive"))
      (node (ref "J1") (pin "A32") (pinfunction "A32_A32") (pintype "passive"))
      (node (ref "J1") (pin "A33") (pinfunction "A33_A33") (pintype "passive"))
      (node (ref "J1") (pin "A38") (pinfunction "A38_A38") (pintype "passive"))
      (node (ref "J1") (pin "A39") (pinfunction "A39_A39") (pintype "passive"))
      (node (ref "J1") (pin "A40") (pinfunction "A40_A40") (pintype "passive"))
      (node (ref "J1") (pin "B26") (pinfunction "B26_B26") (pintype "passive"))
      (node (ref "J1") (pin "B31") (pinfunction "B31_B31") (pintype "passive"))
      (node (ref "J1") (pin "B33") (pinfunction "B33_B33") (pintype "passive"))
      (node (ref "J1") (pin "B38") (pinfunction "B38_B38") (pintype "passive"))
      (node (ref "J1") (pin "B40") (pinfunction "B40_B40") (pintype "passive"))
      (node (ref "J1") (pin "C26") (pinfunction "C26_C26") (pintype "passive"))
      (node (ref "J1") (pin "C31") (pinfunction "C31_C31") (pintype "passive"))
      (node (ref "J1") (pin "C32") (pinfunction "C32_C32") (pintype "passive"))
      (node (ref "J1") (pin "C33") (pinfunction "C33_C33") (pintype "passive"))
      (node (ref "J1") (pin "C34") (pinfunction "C34_C34") (pintype "passive"))
      (node (ref "J1") (pin "C35") (pinfunction "C35_C35") (pintype "passive"))
      (node (ref "J1") (pin "C36") (pinfunction "C36_C36") (pintype "passive"))
      (node (ref "J1") (pin "C37") (pinfunction "C37_C37") (pintype "passive"))
      (node (ref "J1") (pin "C38") (pinfunction "C38_C38") (pintype "passive"))
      (node (ref "J1") (pin "C39") (pinfunction "C39_C39") (pintype "passive"))
      (node (ref "J1") (pin "C40") (pinfunction "C40_C40") (pintype "passive"))
      (node (ref "J1") (pin "C41") (pinfunction "C41_C41") (pintype "passive"))
      (node (ref "J1") (pin "C42") (pinfunction "C42_C42") (pintype "passive"))
      (node (ref "J1") (pin "C43") (pinfunction "C43_C43") (pintype "passive"))
      (node (ref "J1") (pin "C44") (pinfunction "C44_C44") (pintype "passive"))
      (node (ref "J1") (pin "D26") (pinfunction "D26_D26") (pintype "passive"))
      (node (ref "J1") (pin "D31") (pinfunction "D31_D31") (pintype "passive"))
      (node (ref "J1") (pin "D33") (pinfunction "D33_D33") (pintype "passive"))
      (node (ref "J1") (pin "D38") (pinfunction "D38_D38") (pintype "passive"))
      (node (ref "J1") (pin "D40") (pinfunction "D40_D40") (pintype "passive"))
      (node (ref "J1") (pin "E26") (pinfunction "E26_E26") (pintype "passive"))
      (node (ref "J1") (pin "E30") (pinfunction "E30_E30") (pintype "passive"))
      (node (ref "J1") (pin "E31") (pinfunction "E31_E31") (pintype "passive"))
      (node (ref "J1") (pin "E32") (pinfunction "E32_E32") (pintype "passive"))
      (node (ref "J1") (pin "E33") (pinfunction "E33_E33") (pintype "passive"))
      (node (ref "J1") (pin "E38") (pinfunction "E38_E38") (pintype "passive"))
      (node (ref "J1") (pin "E39") (pinfunction "E39_E39") (pintype "passive"))
      (node (ref "J1") (pin "E40") (pinfunction "E40_E40") (pintype "passive"))
    )
    (net (code "58") (name "ANALOG_REF") (class "Default")
      (node (ref "C101") (pin "1") (pinfunction "1_1") (pintype "passive"))
      (node (ref "C113") (pin "1") (pinfunction "1_1") (pintype "passive"))
      (node (ref "C125") (pin "1") (pinfunction "1_1") (pintype "passive"))
      (node (ref "C137") (pin "1") (pinfunction "1_1") (pintype "passive"))
      (node (ref "C149") (pin "1") (pinfunction "1_1") (pintype "passive"))
      (node (ref "C161") (pin "1") (pinfunction "1_1") (pintype "passive"))
      (node (ref "C29") (pin "1") (pinfunction "1_1") (pintype "passive"))
      (node (ref "C41") (pin "1") (pinfunction "1_1") (pintype "passive"))
      (node (ref "C53") (pin "1") (pinfunction "1_1") (pintype "passive"))
      (node (ref "C65") (pin "1") (pinfunction "1_1") (pintype "passive"))
      (node (ref "C77") (pin "1") (pinfunction "1_1") (pintype "passive"))
      (node (ref "C89") (pin "1") (pinfunction "1_1") (pintype "passive"))
      (node (ref "U11") (pin "3") (pinfunction "+IN_A_3") (pintype "input"))
      (node (ref "U13") (pin "3") (pinfunction "+IN_A_3") (pintype "input"))
      (node (ref "U15") (pin "3") (pinfunction "+IN_A_3") (pintype "input"))
      (node (ref "U17") (pin "3") (pinfunction "+IN_A_3") (pintype "input"))
      (node (ref "U19") (pin "3") (pinfunction "+IN_A_3") (pintype "input"))
      (node (ref "U21") (pin "3") (pinfunction "+IN_A_3") (pintype "input"))
      (node (ref "U23") (pin "3") (pinfunction "+IN_A_3") (pintype "input"))
      (node (ref "U25") (pin "3") (pinfunction "+IN_A_3") (pintype "input"))
      (node (ref "U27") (pin "3") (pinfunction "+IN_A_3") (pintype "input"))
      (node (ref "U28") (pin "2") (pinfunction "VOUT_2") (pintype "output"))
      (node (ref "U5") (pin "3") (pinfunction "+IN_A_3") (pintype "input"))
      (node (ref "U7") (pin "3") (pinfunction "+IN_A_3") (pintype "input"))
      (node (ref "U9") (pin "3") (pinfunction "+IN_A_3") (pintype "input"))
    )
    (net (code "59") (name "CSIN") (class "Default")
      (node (ref "ISO1") (pin "12") (pinfunction "B3_12") (pintype "bidirectional"))
    )
    (net (code "60") (name "CSOUT") (class "Default")
      (node (ref "ISO1") (pin "11") (pinfunction "B4_11") (pintype "bidirectional"))
    )
    (net (code "61") (name "D0") (class "Default")
      (node (ref "ISO2") (pin "10") (pinfunction "B5_10") (pintype "bidirectional"))
    )
    (net (code "62") (name "D1") (class "Default")
      (node (ref "ISO2") (pin "11") (pinfunction "B4_11") (pintype "bidirectional"))
    )
    (net (code "63") (name "D2WR_1") (class "Default")
      (node (ref "ISO2") (pin "12") (pinfunction "B3_12") (pintype "bidirectional"))
    )
    (net (code "64") (name "D2WR_2") (class "Default")
      (node (ref "ISO5") (pin "14") (pinfunction "B1_14") (pintype "bidirectional"))
    )
    (net (code "65") (name "D3") (class "Default")
      (node (ref "ISO2") (pin "13") (pinfunction "B2_13") (pintype "bidirectional"))
    )
    (net (code "66") (name "D4") (class "Default")
      (node (ref "ISO2") (pin "14") (pinfunction "B1_14") (pintype "bidirectional"))
    )
    (net (code "67") (name "D5") (class "Default")
      (node (ref "ISO3") (pin "10") (pinfunction "B5_10") (pintype "bidirectional"))
    )
    (net (code "68") (name "D6") (class "Default")
      (node (ref "ISO3") (pin "11") (pinfunction "B4_11") (pintype "bidirectional"))
    )
    (net (code "69") (name "D7") (class "Default")
      (node (ref "ISO3") (pin "12") (pinfunction "B3_12") (pintype "bidirectional"))
    )
    (net (code "70") (name "D8") (class "Default")
      (node (ref "ISO3") (pin "13") (pinfunction "B2_13") (pintype "bidirectional"))
    )
    (net (code "71") (name "D9") (class "Default")
      (node (ref "ISO3") (pin "14") (pinfunction "B1_14") (pintype "bidirectional"))
    )
    (net (code "72") (name "D10") (class "Default")
      (node (ref "ISO4") (pin "10") (pinfunction "B5_10") (pintype "bidirectional"))
    )
    (net (code "73") (name "D11") (class "Default")
      (node (ref "ISO4") (pin "11") (pinfunction "B4_11") (pintype "bidirectional"))
    )
    (net (code "74") (name "D12") (class "Default")
      (node (ref "ISO4") (pin "12") (pinfunction "B3_12") (pintype "bidirectional"))
    )
    (net (code "75") (name "D13") (class "Default")
      (node (ref "ISO4") (pin "13") (pinfunction "B2_13") (pintype "bidirectional"))
    )
    (net (code "76") (name "D14") (class "Default")
      (node (ref "ISO4") (pin "14") (pinfunction "B1_14") (pintype "bidirectional"))
    )
    (net (code "77") (name "D15") (class "Default")
      (node (ref "ISO5") (pin "10") (pinfunction "B5_10") (pintype "bidirectional"))
    )
    (net (code "78") (name "D16") (class "Default")
      (node (ref "ISO5") (pin "11") (pinfunction "B4_11") (pintype "bidirectional"))
    )
    (net (code "79") (name "D17") (class "Default")
      (node (ref "ISO5") (pin "12") (pinfunction "B3_12") (pintype "bidirectional"))
    )
    (net (code "80") (name "D18") (class "Default")
      (node (ref "ISO6") (pin "10") (pinfunction "B5_10") (pintype "bidirectional"))
    )
    (net (code "81") (name "D19") (class "Default")
      (node (ref "ISO6") (pin "11") (pinfunction "B4_11") (pintype "bidirectional"))
    )
    (net (code "82") (name "D20") (class "Default")
      (node (ref "ISO6") (pin "12") (pinfunction "B3_12") (pintype "bidirectional"))
    )
    (net (code "83") (name "D21") (class "Default")
      (node (ref "ISO6") (pin "13") (pinfunction "B2_13") (pintype "bidirectional"))
    )
    (net (code "84") (name "D22") (class "Default")
      (node (ref "ISO6") (pin "14") (pinfunction "B1_14") (pintype "bidirectional"))
    )
    (net (code "85") (name "D23") (class "Default")
      (node (ref "ISO7") (pin "10") (pinfunction "B5_10") (pintype "bidirectional"))
    )
    (net (code "86") (name "D24") (class "Default")
      (node (ref "ISO7") (pin "11") (pinfunction "B4_11") (pintype "bidirectional"))
    )
    (net (code "87") (name "D25") (class "Default")
      (node (ref "ISO7") (pin "12") (pinfunction "B3_12") (pintype "bidirectional"))
    )
    (net (code "88") (name "D26") (class "Default")
      (node (ref "ISO7") (pin "13") (pinfunction "B2_13") (pintype "bidirectional"))
    )
    (net (code "89") (name "D27") (class "Default")
      (node (ref "ISO7") (pin "14") (pinfunction "B1_14") (pintype "bidirectional"))
    )
    (net (code "90") (name "D28") (class "Default")
      (node (ref "ISO8") (pin "10") (pinfunction "B5_10") (pintype "bidirectional"))
    )
    (net (code "91") (name "D29") (class "Default")
      (node (ref "ISO8") (pin "11") (pinfunction "B4_11") (pintype "bidirectional"))
    )
    (net (code "92") (name "D30") (class "Default")
      (node (ref "ISO8") (pin "12") (pinfunction "B3_12") (pintype "bidirectional"))
    )
    (net (code "93") (name "D31") (class "Default")
      (node (ref "ISO8") (pin "13") (pinfunction "B2_13") (pintype "bidirectional"))
    )
    (net (code "94") (name "DACO_1") (class "Default")
      (node (ref "C35") (pin "2") (pinfunction "2_2") (pintype "passive"))
      (node (ref "U30") (pin "5") (pinfunction "+INB_5") (pintype "input"))
      (node (ref "U4") (pin "2") (pinfunction "VOUT_2") (pintype "output"))
    )
    (net (code "95") (name "DACO_7") (class "Default")
      (node (ref "C107") (pin "2") (pinfunction "2_2") (pintype "passive"))
      (node (ref "U16") (pin "2") (pinfunction "VOUT_2") (pintype "output"))
      (node (ref "U30") (pin "3") (pinfunction "+INA_3") (pintype "input"))
    )
    (net (code "96") (name "DAUX0") (class "Default")
      (node (ref "J1") (pin "A1") (pinfunction "A1_A1") (pintype "passive"))
    )
    (net (code "97") (name "DAUX1") (class "Default")
      (node (ref "J1") (pin "D23") (pinfunction "D23_D23") (pintype "passive"))
    )
    (net (code "98") (name "DAUX2") (class "Default")
      (node (ref "J1") (pin "E24") (pinfunction "E24_E24") (pintype "passive"))
    )
    (net (code "99") (name "DAUX3") (class "Default")
      (node (ref "J1") (pin "C24") (pinfunction "C24_C24") (pintype "passive"))
    )
    (net (code "100") (name "DCLK0") (class "Default")
      (node (ref "ISO11") (pin "14") (pinfunction "B1_14") (pintype "bidirectional"))
    )
    (net (code "101") (name "DCLK1") (class "Default")
      (node (ref "ISO11") (pin "13") (pinfunction "B2_13") (pintype "bidirectional"))
    )
    (net (code "102") (name "DCLK2") (class "Default")
      (node (ref "ISO11") (pin "12") (pinfunction "B3_12") (pintype "bidirectional"))
    )
    (net (code "103") (name "DCLK3") (class "Default")
      (node (ref "ISO11") (pin "11") (pinfunction "B4_11") (pintype "bidirectional"))
    )
    (net (code "104") (name "DCLK4") (class "Default")
      (node (ref "ISO11") (pin "10") (pinfunction "B5_10") (pintype "bidirectional"))
    )
    (net (code "105") (name "DCLK5") (class "Default")
      (node (ref "ISO8") (pin "14") (pinfunction "B1_14") (pintype "bidirectional"))
    )
    (net (code "106") (name "DGND") (class "Default")
      (node (ref "C1") (pin "2") (pinfunction "2_2") (pintype "passive"))
      (node (ref "C10") (pin "2") (pinfunction "2_2") (pintype "passive"))
      (node (ref "C13") (pin "2") (pinfunction "2_2") (pintype "passive"))
      (node (ref "C14") (pin "2") (pinfunction "2_2") (pintype "passive"))
      (node (ref "C15") (pin "2") (pinfunction "2_2") (pintype "passive"))
      (node (ref "C16") (pin "2") (pinfunction "2_2") (pintype "passive"))
      (node (ref "C17") (pin "2") (pinfunction "2_2") (pintype "passive"))
      (node (ref "C18") (pin "2") (pinfunction "2_2") (pintype "passive"))
      (node (ref "C19") (pin "2") (pinfunction "2_2") (pintype "passive"))
      (node (ref "C2") (pin "2") (pinfunction "2_2") (pintype "passive"))
      (node (ref "C20") (pin "2") (pinfunction "2_2") (pintype "passive"))
      (node (ref "C21") (pin "2") (pinfunction "2_2") (pintype "passive"))
      (node (ref "C22") (pin "2") (pinfunction "2_2") (pintype "passive"))
      (node (ref "C23") (pin "2") (pinfunction "2_2") (pintype "passive"))
      (node (ref "C24") (pin "2") (pinfunction "2_2") (pintype "passive"))
      (node (ref "C25") (pin "2") (pinfunction "2_2") (pintype "passive"))
      (node (ref "C3") (pin "2") (pinfunction "2_2") (pintype "passive"))
      (node (ref "C4") (pin "2") (pinfunction "2_2") (pintype "passive"))
      (node (ref "C5") (pin "2") (pinfunction "2_2") (pintype "passive"))
      (node (ref "C6") (pin "2") (pinfunction "2_2") (pintype "passive"))
      (node (ref "C7") (pin "2") (pinfunction "2_2") (pintype "passive"))
      (node (ref "C8") (pin "2") (pinfunction "2_2") (pintype "passive"))
      (node (ref "C9") (pin "2") (pinfunction "2_2") (pintype "passive"))
      (node (ref "ISO1") (pin "2") (pinfunction "GND1_2") (pintype "bidirectional"))
      (node (ref "ISO1") (pin "8") (pinfunction "GND1_8") (pintype "bidirectional"))
      (node (ref "ISO10") (pin "15") (pinfunction "GND2_15") (pintype "bidirectional"))
      (node (ref "ISO10") (pin "9") (pinfunction "GND2_9") (pintype "bidirectional"))
      (node (ref "ISO11") (pin "2") (pinfunction "GND1_2") (pintype "bidirectional"))
      (node (ref "ISO11") (pin "8") (pinfunction "GND1_8") (pintype "bidirectional"))
      (node (ref "ISO2") (pin "2") (pinfunction "GND1_2") (pintype "bidirectional"))
      (node (ref "ISO2") (pin "8") (pinfunction "GND1_8") (pintype "bidirectional"))
      (node (ref "ISO3") (pin "2") (pinfunction "GND1_2") (pintype "bidirectional"))
      (node (ref "ISO3") (pin "8") (pinfunction "GND1_8") (pintype "bidirectional"))
      (node (ref "ISO4") (pin "2") (pinfunction "GND1_2") (pintype "bidirectional"))
      (node (ref "ISO4") (pin "8") (pinfunction "GND1_8") (pintype "bidirectional"))
      (node (ref "ISO5") (pin "2") (pinfunction "GND1_2") (pintype "bidirectional"))
      (node (ref "ISO5") (pin "8") (pinfunction "GND1_8") (pintype "bidirectional"))
      (node (ref "ISO6") (pin "2") (pinfunction "GND1_2") (pintype "bidirectional"))
      (node (ref "ISO6") (pin "8") (pinfunction "GND1_8") (pintype "bidirectional"))
      (node (ref "ISO7") (pin "2") (pinfunction "GND1_2") (pintype "bidirectional"))
      (node (ref "ISO7") (pin "8") (pinfunction "GND1_8") (pintype "bidirectional"))
      (node (ref "ISO8") (pin "2") (pinfunction "GND1_2") (pintype "bidirectional"))
      (node (ref "ISO8") (pin "8") (pinfunction "GND1_8") (pintype "bidirectional"))
      (node (ref "ISO9") (pin "15") (pinfunction "GND2_15") (pintype "bidirectional"))
      (node (ref "ISO9") (pin "9") (pinfunction "GND2_9") (pintype "bidirectional"))
      (node (ref "J1") (pin "C11") (pinfunction "C11_C11") (pintype "passive"))
      (node (ref "J1") (pin "C14") (pinfunction "C14_C14") (pintype "passive"))
      (node (ref "J1") (pin "C17") (pinfunction "C17_C17") (pintype "passive"))
      (node (ref "J1") (pin "C2") (pinfunction "C2_C2") (pintype "passive"))
      (node (ref "J1") (pin "C20") (pinfunction "C20_C20") (pintype "passive"))
      (node (ref "J1") (pin "C23") (pinfunction "C23_C23") (pintype "passive"))
      (node (ref "J1") (pin "C25") (pinfunction "C25_C25") (pintype "passive"))
      (node (ref "J1") (pin "C5") (pinfunction "C5_C5") (pintype "passive"))
      (node (ref "J1") (pin "C8") (pinfunction "C8_C8") (pintype "passive"))
      (node (ref "J1") (pin "D1") (pinfunction "D1_D1") (pintype "passive"))
      (node (ref "J1") (pin "D10") (pinfunction "D10_D10") (pintype "passive"))
      (node (ref "J1") (pin "D12") (pinfunction "D12_D12") (pintype "passive"))
      (node (ref "J1") (pin "D13") (pinfunction "D13_D13") (pintype "passive"))
      (node (ref "J1") (pin "D15") (pinfunction "D15_D15") (pintype "passive"))
      (node (ref "J1") (pin "D16") (pinfunction "D16_D16") (pintype "passive"))
      (node (ref "J1") (pin "D18") (pinfunction "D18_D18") (pintype "passive"))
      (node (ref "J1") (pin "D19") (pinfunction "D19_D19") (pintype "passive"))
      (node (ref "J1") (pin "D21") (pinfunction "D21_D21") (pintype "passive"))
      (node (ref "J1") (pin "D22") (pinfunction "D22_D22") (pintype "passive"))
      (node (ref "J1") (pin "D24") (pinfunction "D24_D24") (pintype "passive"))
      (node (ref "J1") (pin "D25") (pinfunction "D25_D25") (pintype "passive"))
      (node (ref "J1") (pin "D3") (pinfunction "D3_D3") (pintype "passive"))
      (node (ref "J1") (pin "D4") (pinfunction "D4_D4") (pintype "passive"))
      (node (ref "J1") (pin "D6") (pinfunction "D6_D6") (pintype "passive"))
      (node (ref "J1") (pin "D7") (pinfunction "D7_D7") (pintype "passive"))
      (node (ref "J1") (pin "D9") (pinfunction "D9_D9") (pintype "passive"))
      (node (ref "J1") (pin "E11") (pinfunction "E11_E11") (pintype "passive"))
      (node (ref "J1") (pin "E14") (pinfunction "E14_E14") (pintype "passive"))
      (node (ref "J1") (pin "E17") (pinfunction "E17_E17") (pintype "passive"))
      (node (ref "J1") (pin "E2") (pinfunction "E2_E2") (pintype "passive"))
      (node (ref "J1") (pin "E20") (pinfunction "E20_E20") (pintype "passive"))
      (node (ref "J1") (pin "E23") (pinfunction "E23_E23") (pintype "passive"))
      (node (ref "J1") (pin "E25") (pinfunction "E25_E25") (pintype "passive"))
      (node (ref "J1") (pin "E5") (pinfunction "E5_E5") (pintype "passive"))
      (node (ref "J1") (pin "E8") (pinfunction "E8_E8") (pintype "passive"))
      (node (ref "R1") (pin "1") (pinfunction "1_1") (pintype "passive"))
      (node (ref "R2") (pin "1") (pinfunction "1_1") (pintype "passive"))
      (node (ref "R3") (pin "1") (pinfunction "1_1") (pintype "passive"))
      (node (ref "R7") (pin "1") (pinfunction "1_1") (pintype "passive"))
      (node (ref "U1") (pin "13") (pinfunction "GND_13") (pintype "bidirectional"))
      (node (ref "U1") (pin "15") (pinfunction "ERC_15") (pintype "bidirectional"))
      (node (ref "U1") (pin "17") (pinfunction "GND_17") (pintype "bidirectional"))
      (node (ref "U1") (pin "4") (pinfunction "GND_4") (pintype "bidirectional"))
      (node (ref "U1") (pin "8") (pinfunction "GND_8") (pintype "bidirectional"))
      (node (ref "U2") (pin "11") (pinfunction "GND_11") (pintype "bidirectional"))
      (node (ref "U2") (pin "18") (pinfunction "GND_18") (pintype "bidirectional"))
      (node (ref "U2") (pin "25") (pinfunction "GND_25") (pintype "bidirectional"))
      (node (ref "U2") (pin "27") (pinfunction "~{OEBA}_27") (pintype "bidirectional"))
      (node (ref "U2") (pin "28") (pinfunction "LEBA_28") (pintype "bidirectional"))
      (node (ref "U2") (pin "29") (pinfunction "~{CEBA}_29") (pintype "bidirectional"))
      (node (ref "U2") (pin "32") (pinfunction "GND_32") (pintype "bidirectional"))
      (node (ref "U2") (pin "39") (pinfunction "GND_39") (pintype "bidirectional"))
      (node (ref "U2") (pin "4") (pinfunction "GND_4") (pintype "bidirectional"))
      (node (ref "U2") (pin "46") (pinfunction "GND_46") (pintype "bidirectional"))
      (node (ref "U2") (pin "53") (pinfunction "GND_53") (pintype "bidirectional"))
      (node (ref "U2") (pin "55") (pinfunction "CLKAB_55") (pintype "bidirectional"))
      (node (ref "U2") (pin "56") (pinfunction "~{CEAB}_56") (pintype "bidirectional"))
      (node (ref "U3") (pin "11") (pinfunction "GND_11") (pintype "bidirectional"))
      (node (ref "U3") (pin "18") (pinfunction "GND_18") (pintype "bidirectional"))
      (node (ref "U3") (pin "25") (pinfunction "GND_25") (pintype "bidirectional"))
      (node (ref "U3") (pin "27") (pinfunction "~{OEBA}_27") (pintype "bidirectional"))
      (node (ref "U3") (pin "28") (pinfunction "LEBA_28") (pintype "bidirectional"))
      (node (ref "U3") (pin "29") (pinfunction "~{CEBA}_29") (pintype "bidirectional"))
      (node (ref "U3") (pin "32") (pinfunction "GND_32") (pintype "bidirectional"))
      (node (ref "U3") (pin "39") (pinfunction "GND_39") (pintype "bidirectional"))
      (node (ref "U3") (pin "4") (pinfunction "GND_4") (pintype "bidirectional"))
      (node (ref "U3") (pin "46") (pinfunction "GND_46") (pintype "bidirectional"))
      (node (ref "U3") (pin "53") (pinfunction "GND_53") (pintype "bidirectional"))
      (node (ref "U3") (pin "55") (pinfunction "CLKAB_55") (pintype "bidirectional"))
      (node (ref "U3") (pin "56") (pinfunction "~{CEAB}_56") (pintype "bidirectional"))
      (node (ref "U40") (pin "10") (pinfunction "GND_10") (pintype "bidirectional"))
      (node (ref "U40") (pin "12") (pinfunction "GND_12") (pintype "bidirectional"))
      (node (ref "U40") (pin "18") (pinfunction "GND_18") (pintype "bidirectional"))
      (node (ref "U40") (pin "2") (pinfunction "1~{OEBA}_2") (pintype "bidirectional"))
      (node (ref "U40") (pin "21") (pinfunction "GND_21") (pintype "bidirectional"))
      (node (ref "U40") (pin "24") (pinfunction "GND_24") (pintype "bidirectional"))
      (node (ref "U40") (pin "26") (pinfunction "GND_26") (pintype "bidirectional"))
      (node (ref "U40") (pin "30") (pinfunction "GND_30") (pintype "bidirectional"))
      (node (ref "U40") (pin "33") (pinfunction "~{OE}_33") (pintype "bidirectional"))
      (node (ref "U40") (pin "34") (pinfunction "2LEBA_34") (pintype "bidirectional"))
      (node (ref "U40") (pin "39") (pinfunction "GND_39") (pintype "bidirectional"))
      (node (ref "U40") (pin "44") (pinfunction "GND_44") (pintype "bidirectional"))
      (node (ref "U40") (pin "47") (pinfunction "GND_47") (pintype "bidirectional"))
      (node (ref "U40") (pin "5") (pinfunction "GND_5") (pintype "bidirectional"))
      (node (ref "U40") (pin "53") (pinfunction "GND_53") (pintype "bidirectional"))
      (node (ref "U40") (pin "57") (pinfunction "GND_57") (pintype "bidirectional"))
      (node (ref "U40") (pin "60") (pinfunction "GND_60") (pintype "bidirectional"))
      (node (ref "U40") (pin "61") (pinfunction "ERC_61") (pintype "bidirectional"))
      (node (ref "U40") (pin "63") (pinfunction "1LEAB_63") (pintype "bidirectional"))
      (node (ref "U40") (pin "64") (pinfunction "CLK_64") (pintype "bidirectional"))
      (node (ref "U40") (pin "8") (pinfunction "GND_8") (pintype "bidirectional"))
    )
    (net (code "107") (name "DI0") (class "Default")
      (node (ref "J1") (pin "E1") (pinfunction "E1_E1") (pintype "passive"))
      (node (ref "U2") (pin "54") (pinfunction "B1_54") (pintype "bidirectional"))
    )
    (net (code "108") (name "DI1") (class "Default")
      (node (ref "J1") (pin "D2") (pinfunction "D2_D2") (pintype "passive"))
      (node (ref "U2") (pin "52") (pinfunction "B2_52") (pintype "bidirectional"))
    )
    (net (code "109") (name "DI2") (class "Default")
      (node (ref "J1") (pin "E3") (pinfunction "E3_E3") (pintype "passive"))
      (node (ref "U2") (pin "51") (pinfunction "B3_51") (pintype "bidirectional"))
    )
    (net (code "110") (name "DI3") (class "Default")
      (node (ref "J1") (pin "C3") (pinfunction "C3_C3") (pintype "passive"))
      (node (ref "U2") (pin "49") (pinfunction "B4_49") (pintype "bidirectional"))
    )
    (net (code "111") (name "DI4") (class "Default")
      (node (ref "J1") (pin "E4") (pinfunction "E4_E4") (pintype "passive"))
      (node (ref "U2") (pin "48") (pinfunction "B5_48") (pintype "bidirectional"))
    )
    (net (code "112") (name "DI5") (class "Default")
      (node (ref "J1") (pin "C4") (pinfunction "C4_C4") (pintype "passive"))
      (node (ref "U2") (pin "47") (pinfunction "B6_47") (pintype "bidirectional"))
    )
    (net (code "113") (name "DI6") (class "Default")
      (node (ref "J1") (pin "D5") (pinfunction "D5_D5") (pintype "passive"))
      (node (ref "U2") (pin "45") (pinfunction "B7_45") (pintype "bidirectional"))
    )
    (net (code "114") (name "DI7") (class "Default")
      (node (ref "J1") (pin "E6") (pinfunction "E6_E6") (pintype "passive"))
      (node (ref "U2") (pin "44") (pinfunction "B8_44") (pintype "bidirectional"))
    )
    (net (code "115") (name "DI8") (class "Default")
      (node (ref "J1") (pin "C6") (pinfunction "C6_C6") (pintype "passive"))
      (node (ref "U2") (pin "43") (pinfunction "B9_43") (pintype "bidirectional"))
    )
    (net (code "116") (name "DI9") (class "Default")
      (node (ref "J1") (pin "E7") (pinfunction "E7_E7") (pintype "passive"))
      (node (ref "U2") (pin "42") (pinfunction "B10_42") (pintype "bidirectional"))
    )
    (net (code "117") (name "DI10") (class "Default")
      (node (ref "J1") (pin "C7") (pinfunction "C7_C7") (pintype "passive"))
      (node (ref "U2") (pin "41") (pinfunction "B11_41") (pintype "bidirectional"))
    )
    (net (code "118") (name "DI11") (class "Default")
      (node (ref "J1") (pin "D8") (pinfunction "D8_D8") (pintype "passive"))
      (node (ref "U2") (pin "40") (pinfunction "B12_40") (pintype "bidirectional"))
    )
    (net (code "119") (name "DI12") (class "Default")
      (node (ref "J1") (pin "E9") (pinfunction "E9_E9") (pintype "passive"))
      (node (ref "U2") (pin "38") (pinfunction "B13_38") (pintype "bidirectional"))
    )
    (net (code "120") (name "DI13") (class "Default")
      (node (ref "J1") (pin "C9") (pinfunction "C9_C9") (pintype "passive"))
      (node (ref "U2") (pin "37") (pinfunction "B14_37") (pintype "bidirectional"))
    )
    (net (code "121") (name "DI14") (class "Default")
      (node (ref "J1") (pin "E10") (pinfunction "E10_E10") (pintype "passive"))
      (node (ref "U2") (pin "36") (pinfunction "B15_36") (pintype "bidirectional"))
    )
    (net (code "122") (name "DI15") (class "Default")
      (node (ref "J1") (pin "C10") (pinfunction "C10_C10") (pintype "passive"))
      (node (ref "U2") (pin "34") (pinfunction "B16_34") (pintype "bidirectional"))
    )
    (net (code "123") (name "DI16") (class "Default")
      (node (ref "J1") (pin "D11") (pinfunction "D11_D11") (pintype "passive"))
      (node (ref "U2") (pin "33") (pinfunction "B17_33") (pintype "bidirectional"))
    )
    (net (code "124") (name "DI17") (class "Default")
      (node (ref "J1") (pin "E12") (pinfunction "E12_E12") (pintype "passive"))
      (node (ref "U2") (pin "31") (pinfunction "B18_31") (pintype "bidirectional"))
    )
    (net (code "125") (name "DI18") (class "Default")
      (node (ref "J1") (pin "C12") (pinfunction "C12_C12") (pintype "passive"))
      (node (ref "U3") (pin "54") (pinfunction "B1_54") (pintype "bidirectional"))
    )
    (net (code "126") (name "DI19") (class "Default")
      (node (ref "J1") (pin "E13") (pinfunction "E13_E13") (pintype "passive"))
      (node (ref "U3") (pin "52") (pinfunction "B2_52") (pintype "bidirectional"))
    )
    (net (code "127") (name "DI20") (class "Default")
      (node (ref "J1") (pin "C13") (pinfunction "C13_C13") (pintype "passive"))
      (node (ref "U3") (pin "51") (pinfunction "B3_51") (pintype "bidirectional"))
    )
    (net (code "128") (name "DI21") (class "Default")
      (node (ref "J1") (pin "D14") (pinfunction "D14_D14") (pintype "passive"))
      (node (ref "U3") (pin "49") (pinfunction "B4_49") (pintype "bidirectional"))
    )
    (net (code "129") (name "DI22") (class "Default")
      (node (ref "J1") (pin "E15") (pinfunction "E15_E15") (pintype "passive"))
      (node (ref "U3") (pin "48") (pinfunction "B5_48") (pintype "bidirectional"))
    )
    (net (code "130") (name "DI23") (class "Default")
      (node (ref "J1") (pin "C15") (pinfunction "C15_C15") (pintype "passive"))
      (node (ref "U3") (pin "47") (pinfunction "B6_47") (pintype "bidirectional"))
    )
    (net (code "131") (name "DI24") (class "Default")
      (node (ref "J1") (pin "E16") (pinfunction "E16_E16") (pintype "passive"))
      (node (ref "U3") (pin "45") (pinfunction "B7_45") (pintype "bidirectional"))
    )
    (net (code "132") (name "DI25") (class "Default")
      (node (ref "J1") (pin "C16") (pinfunction "C16_C16") (pintype "passive"))
      (node (ref "U3") (pin "44") (pinfunction "B8_44") (pintype "bidirectional"))
    )
    (net (code "133") (name "DI26") (class "Default")
      (node (ref "J1") (pin "D17") (pinfunction "D17_D17") (pintype "passive"))
      (node (ref "U3") (pin "43") (pinfunction "B9_43") (pintype "bidirectional"))
    )
    (net (code "134") (name "DI27") (class "Default")
      (node (ref "J1") (pin "E18") (pinfunction "E18_E18") (pintype "passive"))
      (node (ref "U3") (pin "42") (pinfunction "B10_42") (pintype "bidirectional"))
    )
    (net (code "135") (name "DI28") (class "Default")
      (node (ref "J1") (pin "C18") (pinfunction "C18_C18") (pintype "passive"))
      (node (ref "U3") (pin "41") (pinfunction "B11_41") (pintype "bidirectional"))
    )
    (net (code "136") (name "DI29") (class "Default")
      (node (ref "J1") (pin "E19") (pinfunction "E19_E19") (pintype "passive"))
      (node (ref "U3") (pin "40") (pinfunction "B12_40") (pintype "bidirectional"))
    )
    (net (code "137") (name "DI30") (class "Default")
      (node (ref "J1") (pin "C19") (pinfunction "C19_C19") (pintype "passive"))
      (node (ref "U3") (pin "38") (pinfunction "B13_38") (pintype "bidirectional"))
    )
    (net (code "138") (name "DI31") (class "Default")
      (node (ref "J1") (pin "D20") (pinfunction "D20_D20") (pintype "passive"))
      (node (ref "U3") (pin "37") (pinfunction "B14_37") (pintype "bidirectional"))
    )
    (net (code "139") (name "DI32") (class "Default")
      (node (ref "J1") (pin "E21") (pinfunction "E21_E21") (pintype "passive"))
      (node (ref "U3") (pin "36") (pinfunction "B15_36") (pintype "bidirectional"))
    )
    (net (code "140") (name "DI33") (class "Default")
      (node (ref "J1") (pin "C21") (pinfunction "C21_C21") (pintype "passive"))
      (node (ref "U3") (pin "34") (pinfunction "B16_34") (pintype "bidirectional"))
    )
    (net (code "141") (name "DI34") (class "Default")
      (node (ref "J1") (pin "E22") (pinfunction "E22_E22") (pintype "passive"))
      (node (ref "U3") (pin "33") (pinfunction "B17_33") (pintype "bidirectional"))
    )
    (net (code "142") (name "DI35") (class "Default")
      (node (ref "J1") (pin "C22") (pinfunction "C22_C22") (pintype "passive"))
      (node (ref "U3") (pin "31") (pinfunction "B18_31") (pintype "bidirectional"))
    )
    (net (code "143") (name "DICS") (class "Default")
      (node (ref "ISO1") (pin "5") (pinfunction "A3_5") (pintype "bidirectional"))
      (node (ref "J1") (pin "A21") (pinfunction "A21_A21") (pintype "passive"))
      (node (ref "R2") (pin "2") (pinfunction "2_2") (pintype "passive"))
      (node (ref "U40") (pin "62") (pinfunction "1LEBA_62") (pintype "bidirectional"))
    )
    (net (code "144") (name "DO0") (class "Default")
      (node (ref "J1") (pin "A4") (pinfunction "A4_A4") (pintype "passive"))
      (node (ref "U40") (pin "37") (pinfunction "2B8_37") (pintype "bidirectional"))
    )
    (net (code "145") (name "DO1") (class "Default")
      (node (ref "J1") (pin "B5") (pinfunction "B5_B5") (pintype "passive"))
      (node (ref "U40") (pin "38") (pinfunction "2B7_38") (pintype "bidirectional"))
    )
    (net (code "146") (name "DO2") (class "Default")
      (node (ref "J1") (pin "A6") (pinfunction "A6_A6") (pintype "passive"))
      (node (ref "U40") (pin "40") (pinfunction "2B6_40") (pintype "bidirectional"))
    )
    (net (code "147") (name "DO3") (class "Default")
      (node (ref "J1") (pin "A7") (pinfunction "A7_A7") (pintype "passive"))
      (node (ref "U40") (pin "42") (pinfunction "2B5_42") (pintype "bidirectional"))
    )
    (net (code "148") (name "DO4") (class "Default")
      (node (ref "J1") (pin "B8") (pinfunction "B8_B8") (pintype "passive"))
      (node (ref "U40") (pin "43") (pinfunction "2B4_43") (pintype "bidirectional"))
    )
    (net (code "149") (name "DO5") (class "Default")
      (node (ref "J1") (pin "A9") (pinfunction "A9_A9") (pintype "passive"))
      (node (ref "U40") (pin "45") (pinfunction "2B3_45") (pintype "bidirectional"))
    )
    (net (code "150") (name "DO6") (class "Default")
      (node (ref "J1") (pin "B11") (pinfunction "B11_B11") (pintype "passive"))
      (node (ref "U40") (pin "46") (pinfunction "2B2_46") (pintype "bidirectional"))
    )
    (net (code "151") (name "DO7") (class "Default")
      (node (ref "J1") (pin "A12") (pinfunction "A12_A12") (pintype "passive"))
      (node (ref "U40") (pin "48") (pinfunction "2B1_48") (pintype "bidirectional"))
    )
    (net (code "152") (name "DOCLKI") (class "Default")
      (node (ref "J1") (pin "C1") (pinfunction "C1_C1") (pintype "passive"))
      (node (ref "U1") (pin "16") (pinfunction "1B_16") (pintype "bidirectional"))
    )
    (net (code "153") (name "DOCLKIB") (class "Default")
      (node (ref "ISO1") (pin "7") (pinfunction "A5_7") (pintype "bidirectional"))
      (node (ref "R3") (pin "2") (pinfunction "2_2") (pintype "passive"))
      (node (ref "U1") (pin "1") (pinfunction "1Y_1") (pintype "bidirectional"))
    )
    (net (code "154") (name "DOCLKO") (class "Default")
      (node (ref "J1") (pin "B2") (pinfunction "B2_B2") (pintype "passive"))
      (node (ref "U1") (pin "14") (pinfunction "2B_14") (pintype "bidirectional"))
    )
    (net (code "155") (name "DOCLKOB") (class "Default")
      (node (ref "ISO10") (pin "11") (pinfunction "B4_11") (pintype "bidirectional"))
      (node (ref "U1") (pin "9") (pinfunction "2A_9") (pintype "bidirectional"))
    )
    (net (code "156") (name "DOCS") (class "Default")
      (node (ref "ISO1") (pin "6") (pinfunction "A4_6") (pintype "bidirectional"))
      (node (ref "J1") (pin "A3") (pinfunction "A3_A3") (pintype "passive"))
      (node (ref "R1") (pin "2") (pinfunction "2_2") (pintype "passive"))
      (node (ref "U1") (pin "10") (pinfunction "2~{OEAB}_10") (pintype "bidirectional"))
      (node (ref "U1") (pin "20") (pinfunction "1~{OEBY}_20") (pintype "bidirectional"))
      (node (ref "U40") (pin "31") (pinfunction "2~{OEAB}_31") (pintype "bidirectional"))
    )
    (net (code "157") (name "DPWR") (class "Default")
      (node (ref "C110") (pin "2") (pinfunction "2_2") (pintype "passive"))
      (node (ref "C122") (pin "2") (pinfunction "2_2") (pintype "passive"))
      (node (ref "C134") (pin "2") (pinfunction "2_2") (pintype "passive"))
      (node (ref "C146") (pin "2") (pinfunction "2_2") (pintype "passive"))
      (node (ref "C158") (pin "2") (pinfunction "2_2") (pintype "passive"))
      (node (ref "C26") (pin "2") (pinfunction "2_2") (pintype "passive"))
      (node (ref "C38") (pin "2") (pinfunction "2_2") (pintype "passive"))
      (node (ref "C50") (pin "2") (pinfunction "2_2") (pintype "passive"))
      (node (ref "C62") (pin "2") (pinfunction "2_2") (pintype "passive"))
      (node (ref "C74") (pin "2") (pinfunction "2_2") (pintype "passive"))
      (node (ref "C86") (pin "2") (pinfunction "2_2") (pintype "passive"))
      (node (ref "C98") (pin "2") (pinfunction "2_2") (pintype "passive"))
      (node (ref "U10") (pin "10") (pinfunction "IOVCC_10") (pintype "power_in"))
      (node (ref "U10") (pin "6") (pinfunction "~{RESET}_6") (pintype "input"))
      (node (ref "U10") (pin "7") (pinfunction "~{CLR}_7") (pintype "input"))
      (node (ref "U10") (pin "9") (pinfunction "VCC_9") (pintype "power_in"))
      (node (ref "U12") (pin "10") (pinfunction "IOVCC_10") (pintype "power_in"))
      (node (ref "U12") (pin "6") (pinfunction "~{RESET}_6") (pintype "input"))
      (node (ref "U12") (pin "7") (pinfunction "~{CLR}_7") (pintype "input"))
      (node (ref "U12") (pin "9") (pinfunction "VCC_9") (pintype "power_in"))
      (node (ref "U14") (pin "10") (pinfunction "IOVCC_10") (pintype "power_in"))
      (node (ref "U14") (pin "6") (pinfunction "~{RESET}_6") (pintype "input"))
      (node (ref "U14") (pin "7") (pinfunction "~{CLR}_7") (pintype "input"))
      (node (ref "U14") (pin "9") (pinfunction "VCC_9") (pintype "power_in"))
      (node (ref "U16") (pin "10") (pinfunction "IOVCC_10") (pintype "power_in"))
      (node (ref "U16") (pin "6") (pinfunction "~{RESET}_6") (pintype "input"))
      (node (ref "U16") (pin "7") (pinfunction "~{CLR}_7") (pintype "input"))
      (node (ref "U16") (pin "9") (pinfunction "VCC_9") (pintype "power_in"))
      (node (ref "U18") (pin "10") (pinfunction "IOVCC_10") (pintype "power_in"))
      (node (ref "U18") (pin "6") (pinfunction "~{RESET}_6") (pintype "input"))
      (node (ref "U18") (pin "7") (pinfunction "~{CLR}_7") (pintype "input"))
      (node (ref "U18") (pin "9") (pinfunction "VCC_9") (pintype "power_in"))
      (node (ref "U20") (pin "10") (pinfunction "IOVCC_10") (pintype "power_in"))
      (node (ref "U20") (pin "6") (pinfunction "~{RESET}_6") (pintype "input"))
      (node (ref "U20") (pin "7") (pinfunction "~{CLR}_7") (pintype "input"))
      (node (ref "U20") (pin "9") (pinfunction "VCC_9") (pintype "power_in"))
      (node (ref "U22") (pin "10") (pinfunction "IOVCC_10") (pintype "power_in"))
      (node (ref "U22") (pin "6") (pinfunction "~{RESET}_6") (pintype "input"))
      (node (ref "U22") (pin "7") (pinfunction "~{CLR}_7") (pintype "input"))
      (node (ref "U22") (pin "9") (pinfunction "VCC_9") (pintype "power_in"))
      (node (ref "U24") (pin "10") (pinfunction "IOVCC_10") (pintype "power_in"))
      (node (ref "U24") (pin "6") (pinfunction "~{RESET}_6") (pintype "input"))
      (node (ref "U24") (pin "7") (pinfunction "~{CLR}_7") (pintype "input"))
      (node (ref "U24") (pin "9") (pinfunction "VCC_9") (pintype "power_in"))
      (node (ref "U26") (pin "10") (pinfunction "IOVCC_10") (pintype "power_in"))
      (node (ref "U26") (pin "6") (pinfunction "~{RESET}_6") (pintype "input"))
      (node (ref "U26") (pin "7") (pinfunction "~{CLR}_7") (pintype "input"))
      (node (ref "U26") (pin "9") (pinfunction "VCC_9") (pintype "power_in"))
      (node (ref "U4") (pin "10") (pinfunction "IOVCC_10") (pintype "power_in"))
      (node (ref "U4") (pin "6") (pinfunction "~{RESET}_6") (pintype "input"))
      (node (ref "U4") (pin "7") (pinfunction "~{CLR}_7") (pintype "input"))
      (node (ref "U4") (pin "9") (pinfunction "VCC_9") (pintype "power_in"))
      (node (ref "U6") (pin "10") (pinfunction "IOVCC_10") (pintype "power_in"))
      (node (ref "U6") (pin "6") (pinfunction "~{RESET}_6") (pintype "input"))
      (node (ref "U6") (pin "7") (pinfunction "~{CLR}_7") (pintype "input"))
      (node (ref "U6") (pin "9") (pinfunction "VCC_9") (pintype "power_in"))
      (node (ref "U8") (pin "10") (pinfunction "IOVCC_10") (pintype "power_in"))
      (node (ref "U8") (pin "6") (pinfunction "~{RESET}_6") (pintype "input"))
      (node (ref "U8") (pin "7") (pinfunction "~{CLR}_7") (pintype "input"))
      (node (ref "U8") (pin "9") (pinfunction "VCC_9") (pintype "power_in"))
    )
    (net (code "158") (name "DSCLK0") (class "Default")
      (node (ref "J1") (pin "B14") (pinfunction "B14_B14") (pintype "passive"))
      (node (ref "U40") (pin "51") (pinfunction "1B7_51") (pintype "bidirectional"))
    )
    (net (code "159") (name "DSCLK0B") (class "Default")
      (node (ref "U2") (pin "30") (pinfunction "CLKBA_30") (pintype "bidirectional"))
      (node (ref "U40") (pin "14") (pinfunction "1A7_14") (pintype "bidirectional"))
    )
    (net (code "160") (name "DSCLK1") (class "Default")
      (node (ref "J1") (pin "B20") (pinfunction "B20_B20") (pintype "passive"))
      (node (ref "U40") (pin "59") (pinfunction "1B1_59") (pintype "bidirectional"))
    )
    (net (code "161") (name "DSCLK1B") (class "Default")
      (node (ref "U3") (pin "30") (pinfunction "CLKBA_30") (pintype "bidirectional"))
      (node (ref "U40") (pin "4") (pinfunction "1A1_4") (pintype "bidirectional"))
    )
    (net (code "162") (name "DVCC") (class "Default")
      (node (ref "C1") (pin "1") (pinfunction "1_1") (pintype "passive"))
      (node (ref "C10") (pin "1") (pinfunction "1_1") (pintype "passive"))
      (node (ref "C13") (pin "1") (pinfunction "1_1") (pintype "passive"))
      (node (ref "C14") (pin "1") (pinfunction "1_1") (pintype "passive"))
      (node (ref "C15") (pin "1") (pinfunction "1_1") (pintype "passive"))
      (node (ref "C16") (pin "1") (pinfunction "1_1") (pintype "passive"))
      (node (ref "C17") (pin "1") (pinfunction "1_1") (pintype "passive"))
      (node (ref "C18") (pin "1") (pinfunction "1_1") (pintype "passive"))
      (node (ref "C19") (pin "1") (pinfunction "1_1") (pintype "passive"))
      (node (ref "C2") (pin "1") (pinfunction "1_1") (pintype "passive"))
      (node (ref "C20") (pin "1") (pinfunction "1_1") (pintype "passive"))
      (node (ref "C21") (pin "1") (pinfunction "1_1") (pintype "passive"))
      (node (ref "C22") (pin "1") (pinfunction "1_1") (pintype "passive"))
      (node (ref "C3") (pin "1") (pinfunction "1_1") (pintype "passive"))
      (node (ref "C4") (pin "1") (pinfunction "1_1") (pintype "passive"))
      (node (ref "C5") (pin "1") (pinfunction "1_1") (pintype "passive"))
      (node (ref "C6") (pin "1") (pinfunction "1_1") (pintype "passive"))
      (node (ref "C7") (pin "1") (pinfunction "1_1") (pintype "passive"))
      (node (ref "C8") (pin "1") (pinfunction "1_1") (pintype "passive"))
      (node (ref "C9") (pin "1") (pinfunction "1_1") (pintype "passive"))
      (node (ref "ISO1") (pin "1") (pinfunction "VDD1_1") (pintype "bidirectional"))
      (node (ref "ISO10") (pin "16") (pinfunction "VDD2_16") (pintype "bidirectional"))
      (node (ref "ISO11") (pin "1") (pinfunction "VDD1_1") (pintype "bidirectional"))
      (node (ref "ISO2") (pin "1") (pinfunction "VDD1_1") (pintype "bidirectional"))
      (node (ref "ISO3") (pin "1") (pinfunction "VDD1_1") (pintype "bidirectional"))
      (node (ref "ISO4") (pin "1") (pinfunction "VDD1_1") (pintype "bidirectional"))
      (node (ref "ISO5") (pin "1") (pinfunction "VDD1_1") (pintype "bidirectional"))
      (node (ref "ISO6") (pin "1") (pinfunction "VDD1_1") (pintype "bidirectional"))
      (node (ref "ISO7") (pin "1") (pinfunction "VDD1_1") (pintype "bidirectional"))
      (node (ref "ISO8") (pin "1") (pinfunction "VDD1_1") (pintype "bidirectional"))
      (node (ref "ISO9") (pin "16") (pinfunction "VDD2_16") (pintype "bidirectional"))
      (node (ref "J1") (pin "A11") (pinfunction "A11_A11") (pintype "passive"))
      (node (ref "J1") (pin "A14") (pinfunction "A14_A14") (pintype "passive"))
      (node (ref "J1") (pin "A17") (pinfunction "A17_A17") (pintype "passive"))
      (node (ref "J1") (pin "A2") (pinfunction "A2_A2") (pintype "passive"))
      (node (ref "J1") (pin "A20") (pinfunction "A20_A20") (pintype "passive"))
      (node (ref "J1") (pin "A22") (pinfunction "A22_A22") (pintype "passive"))
      (node (ref "J1") (pin "A23") (pinfunction "A23_A23") (pintype "passive"))
      (node (ref "J1") (pin "A25") (pinfunction "A25_A25") (pintype "passive"))
      (node (ref "J1") (pin "A5") (pinfunction "A5_A5") (pintype "passive"))
      (node (ref "J1") (pin "A8") (pinfunction "A8_A8") (pintype "passive"))
      (node (ref "J1") (pin "B1") (pinfunction "B1_B1") (pintype "passive"))
      (node (ref "J1") (pin "B12") (pinfunction "B12_B12") (pintype "passive"))
      (node (ref "J1") (pin "B13") (pinfunction "B13_B13") (pintype "passive"))
      (node (ref "J1") (pin "B15") (pinfunction "B15_B15") (pintype "passive"))
      (node (ref "J1") (pin "B16") (pinfunction "B16_B16") (pintype "passive"))
      (node (ref "J1") (pin "B18") (pinfunction "B18_B18") (pintype "passive"))
      (node (ref "J1") (pin "B19") (pinfunction "B19_B19") (pintype "passive"))
      (node (ref "J1") (pin "B21") (pinfunction "B21_B21") (pintype "passive"))
      (node (ref "J1") (pin "B22") (pinfunction "B22_B22") (pintype "passive"))
      (node (ref "J1") (pin "B24") (pinfunction "B24_B24") (pintype "passive"))
      (node (ref "J1") (pin "B25") (pinfunction "B25_B25") (pintype "passive"))
      (node (ref "J1") (pin "B3") (pinfunction "B3_B3") (pintype "passive"))
      (node (ref "J1") (pin "B4") (pinfunction "B4_B4") (pintype "passive"))
      (node (ref "J1") (pin "B6") (pinfunction "B6_B6") (pintype "passive"))
      (node (ref "J1") (pin "B7") (pinfunction "B7_B7") (pintype "passive"))
      (node (ref "J1") (pin "B9") (pinfunction "B9_B9") (pintype "passive"))
      (node (ref "U1") (pin "11") (pinfunction "BIAS_VCC_11") (pintype "bidirectional"))
      (node (ref "U1") (pin "18") (pinfunction "2~{OEBY}_18") (pintype "bidirectional"))
      (node (ref "U1") (pin "19") (pinfunction "2T/~{C}_19") (pintype "bidirectional"))
      (node (ref "U1") (pin "2") (pinfunction "1T/~{C}_2") (pintype "bidirectional"))
      (node (ref "U1") (pin "5") (pinfunction "1~{OEAB}_5") (pintype "bidirectional"))
      (node (ref "U1") (pin "6") (pinfunction "VCC_6") (pintype "bidirectional"))
      (node (ref "U1") (pin "7") (pinfunction "1A_7") (pintype "bidirectional"))
      (node (ref "U2") (pin "1") (pinfunction "~{OEAB}_1") (pintype "bidirectional"))
      (node (ref "U2") (pin "2") (pinfunction "LEAB_2") (pintype "bidirectional"))
      (node (ref "U2") (pin "22") (pinfunction "VCC_22") (pintype "bidirectional"))
      (node (ref "U2") (pin "50") (pinfunction "BIAS_VCC_50") (pintype "bidirectional"))
      (node (ref "U2") (pin "7") (pinfunction "VCC_7") (pintype "bidirectional"))
      (node (ref "U3") (pin "1") (pinfunction "~{OEAB}_1") (pintype "bidirectional"))
      (node (ref "U3") (pin "2") (pinfunction "LEAB_2") (pintype "bidirectional"))
      (node (ref "U3") (pin "22") (pinfunction "VCC_22") (pintype "bidirectional"))
      (node (ref "U3") (pin "50") (pinfunction "BIAS_VCC_50") (pintype "bidirectional"))
      (node (ref "U3") (pin "7") (pinfunction "VCC_7") (pintype "bidirectional"))
      (node (ref "U40") (pin "1") (pinfunction "1~{OEAB}_1") (pintype "bidirectional"))
      (node (ref "U40") (pin "15") (pinfunction "VCC_15") (pintype "bidirectional"))
      (node (ref "U40") (pin "28") (pinfunction "VCC_28") (pintype "bidirectional"))
      (node (ref "U40") (pin "3") (pinfunction "VCC_3") (pintype "bidirectional"))
      (node (ref "U40") (pin "32") (pinfunction "2~{OEBA}_32") (pintype "bidirectional"))
      (node (ref "U40") (pin "35") (pinfunction "2LEAB_35") (pintype "bidirectional"))
      (node (ref "U40") (pin "36") (pinfunction "BIAS_VCC_36") (pintype "bidirectional"))
      (node (ref "U40") (pin "50") (pinfunction "VCC_50") (pintype "bidirectional"))
    )
    (net (code "163") (name "DVDD33") (class "Default")
      (node (ref "ISO1") (pin "16") (pinfunction "VDD2_16") (pintype "bidirectional"))
      (node (ref "ISO11") (pin "16") (pinfunction "VDD2_16") (pintype "bidirectional"))
      (node (ref "ISO2") (pin "16") (pinfunction "VDD2_16") (pintype "bidirectional"))
      (node (ref "ISO3") (pin "16") (pinfunction "VDD2_16") (pintype "bidirectional"))
      (node (ref "ISO4") (pin "16") (pinfunction "VDD2_16") (pintype "bidirectional"))
      (node (ref "ISO5") (pin "16") (pinfunction "VDD2_16") (pintype "bidirectional"))
      (node (ref "ISO6") (pin "16") (pinfunction "VDD2_16") (pintype "bidirectional"))
      (node (ref "ISO7") (pin "16") (pinfunction "VDD2_16") (pintype "bidirectional"))
      (node (ref "ISO8") (pin "16") (pinfunction "VDD2_16") (pintype "bidirectional"))
    )
    (net (code "164") (name "DVTT") (class "Default")
      (node (ref "J1") (pin "A10") (pinfunction "A10_A10") (pintype "passive"))
      (node (ref "J1") (pin "B10") (pinfunction "B10_B10") (pintype "passive"))
      (node (ref "R6") (pin "2") (pinfunction "2_2") (pintype "passive"))
    )
    (net (code "165") (name "DX0") (class "Default")
      (node (ref "J1") (pin "A13") (pinfunction "A13_A13") (pintype "passive"))
      (node (ref "U40") (pin "49") (pinfunction "1B8_49") (pintype "bidirectional"))
    )
    (net (code "166") (name "DX1") (class "Default")
      (node (ref "J1") (pin "A15") (pinfunction "A15_A15") (pintype "passive"))
      (node (ref "U40") (pin "52") (pinfunction "1B6_52") (pintype "bidirectional"))
    )
    (net (code "167") (name "DX2") (class "Default")
      (node (ref "J1") (pin "A16") (pinfunction "A16_A16") (pintype "passive"))
      (node (ref "U40") (pin "54") (pinfunction "1B5_54") (pintype "bidirectional"))
    )
    (net (code "168") (name "DX3") (class "Default")
      (node (ref "J1") (pin "B17") (pinfunction "B17_B17") (pintype "passive"))
      (node (ref "U40") (pin "55") (pinfunction "1B4_55") (pintype "bidirectional"))
    )
    (net (code "169") (name "DX4") (class "Default")
      (node (ref "J1") (pin "A18") (pinfunction "A18_A18") (pintype "passive"))
      (node (ref "U40") (pin "56") (pinfunction "1B3_56") (pintype "bidirectional"))
    )
    (net (code "170") (name "DX5") (class "Default")
      (node (ref "J1") (pin "A19") (pinfunction "A19_A19") (pintype "passive"))
      (node (ref "U40") (pin "58") (pinfunction "1B2_58") (pintype "bidirectional"))
    )
    (net (code "171") (name "F1") (class "Default")
      (node (ref "ISO1") (pin "14") (pinfunction "B1_14") (pintype "bidirectional"))
    )
    (net (code "172") (name "F2") (class "Default")
      (node (ref "ISO1") (pin "13") (pinfunction "B2_13") (pintype "bidirectional"))
    )
    (net (code "173") (name "GND") (class "Default")
      (node (ref "C100") (pin "1") (pinfunction "1_1") (pintype "passive"))
      (node (ref "C101") (pin "2") (pinfunction "2_2") (pintype "passive"))
      (node (ref "C102") (pin "1") (pinfunction "1_1") (pintype "passive"))
      (node (ref "C103") (pin "1") (pinfunction "1_1") (pintype "passive"))
      (node (ref "C104") (pin "1") (pinfunction "1_1") (pintype "passive"))
      (node (ref "C105") (pin "1") (pinfunction "1_1") (pintype "passive"))
      (node (ref "C107") (pin "1") (pinfunction "1_1") (pintype "passive"))
      (node (ref "C108") (pin "1") (pinfunction "1_1") (pintype "passive"))
      (node (ref "C109") (pin "1") (pinfunction "1_1") (pintype "passive"))
      (node (ref "C11") (pin "1") (pinfunction "1_1") (pintype "passive"))
      (node (ref "C110") (pin "1") (pinfunction "1_1") (pintype "passive"))
      (node (ref "C111") (pin "1") (pinfunction "1_1") (pintype "passive"))
      (node (ref "C112") (pin "1") (pinfunction "1_1") (pintype "passive"))
      (node (ref "C113") (pin "2") (pinfunction "2_2") (pintype "passive"))
      (node (ref "C114") (pin "1") (pinfunction "1_1") (pintype "passive"))
      (node (ref "C115") (pin "1") (pinfunction "1_1") (pintype "passive"))
      (node (ref "C116") (pin "1") (pinfunction "1_1") (pintype "passive"))
      (node (ref "C117") (pin "1") (pinfunction "1_1") (pintype "passive"))
      (node (ref "C119") (pin "1") (pinfunction "1_1") (pintype "passive"))
      (node (ref "C12") (pin "1") (pinfunction "1_1") (pintype "passive"))
      (node (ref "C120") (pin "1") (pinfunction "1_1") (pintype "passive"))
      (node (ref "C121") (pin "1") (pinfunction "1_1") (pintype "passive"))
      (node (ref "C122") (pin "1") (pinfunction "1_1") (pintype "passive"))
      (node (ref "C123") (pin "1") (pinfunction "1_1") (pintype "passive"))
      (node (ref "C124") (pin "1") (pinfunction "1_1") (pintype "passive"))
      (node (ref "C125") (pin "2") (pinfunction "2_2") (pintype "passive"))
      (node (ref "C126") (pin "1") (pinfunction "1_1") (pintype "passive"))
      (node (ref "C127") (pin "1") (pinfunction "1_1") (pintype "passive"))
      (node (ref "C128") (pin "1") (pinfunction "1_1") (pintype "passive"))
      (node (ref "C129") (pin "1") (pinfunction "1_1") (pintype "passive"))
      (node (ref "C131") (pin "1") (pinfunction "1_1") (pintype "passive"))
      (node (ref "C132") (pin "1") (pinfunction "1_1") (pintype "passive"))
      (node (ref "C133") (pin "1") (pinfunction "1_1") (pintype "passive"))
      (node (ref "C134") (pin "1") (pinfunction "1_1") (pintype "passive"))
      (node (ref "C135") (pin "1") (pinfunction "1_1") (pintype "passive"))
      (node (ref "C136") (pin "1") (pinfunction "1_1") (pintype "passive"))
      (node (ref "C137") (pin "2") (pinfunction "2_2") (pintype "passive"))
      (node (ref "C138") (pin "1") (pinfunction "1_1") (pintype "passive"))
      (node (ref "C139") (pin "1") (pinfunction "1_1") (pintype "passive"))
      (node (ref "C140") (pin "1") (pinfunction "1_1") (pintype "passive"))
      (node (ref "C141") (pin "1") (pinfunction "1_1") (pintype "passive"))
      (node (ref "C143") (pin "1") (pinfunction "1_1") (pintype "passive"))
      (node (ref "C144") (pin "1") (pinfunction "1_1") (pintype "passive"))
      (node (ref "C145") (pin "1") (pinfunction "1_1") (pintype "passive"))
      (node (ref "C146") (pin "1") (pinfunction "1_1") (pintype "passive"))
      (node (ref "C147") (pin "1") (pinfunction "1_1") (pintype "passive"))
      (node (ref "C148") (pin "1") (pinfunction "1_1") (pintype "passive"))
      (node (ref "C149") (pin "2") (pinfunction "2_2") (pintype "passive"))
      (node (ref "C150") (pin "1") (pinfunction "1_1") (pintype "passive"))
      (node (ref "C151") (pin "1") (pinfunction "1_1") (pintype "passive"))
      (node (ref "C152") (pin "1") (pinfunction "1_1") (pintype "passive"))
      (node (ref "C153") (pin "1") (pinfunction "1_1") (pintype "passive"))
      (node (ref "C155") (pin "1") (pinfunction "1_1") (pintype "passive"))
      (node (ref "C156") (pin "1") (pinfunction "1_1") (pintype "passive"))
      (node (ref "C157") (pin "1") (pinfunction "1_1") (pintype "passive"))
      (node (ref "C158") (pin "1") (pinfunction "1_1") (pintype "passive"))
      (node (ref "C159") (pin "1") (pinfunction "1_1") (pintype "passive"))
      (node (ref "C160") (pin "1") (pinfunction "1_1") (pintype "passive"))
      (node (ref "C161") (pin "2") (pinfunction "2_2") (pintype "passive"))
      (node (ref "C162") (pin "1") (pinfunction "1_1") (pintype "passive"))
      (node (ref "C163") (pin "1") (pinfunction "1_1") (pintype "passive"))
      (node (ref "C164") (pin "1") (pinfunction "1_1") (pintype "passive"))
      (node (ref "C165") (pin "1") (pinfunction "1_1") (pintype "passive"))
      (node (ref "C167") (pin "1") (pinfunction "1_1") (pintype "passive"))
      (node (ref "C168") (pin "2") (pinfunction "2_2") (pintype "passive"))
      (node (ref "C169") (pin "2") (pinfunction "2_2") (pintype "passive"))
      (node (ref "C170") (pin "2") (pinfunction "2_2") (pintype "passive"))
      (node (ref "C171") (pin "2") (pinfunction "2_2") (pintype "passive"))
      (node (ref "C26") (pin "1") (pinfunction "1_1") (pintype "passive"))
      (node (ref "C27") (pin "1") (pinfunction "1_1") (pintype "passive"))
      (node (ref "C28") (pin "1") (pinfunction "1_1") (pintype "passive"))
      (node (ref "C29") (pin "2") (pinfunction "2_2") (pintype "passive"))
      (node (ref "C30") (pin "1") (pinfunction "1_1") (pintype "passive"))
      (node (ref "C31") (pin "1") (pinfunction "1_1") (pintype "passive"))
      (node (ref "C32") (pin "1") (pinfunction "1_1") (pintype "passive"))
      (node (ref "C33") (pin "1") (pinfunction "1_1") (pintype "passive"))
      (node (ref "C35") (pin "1") (pinfunction "1_1") (pintype "passive"))
      (node (ref "C36") (pin "1") (pinfunction "1_1") (pintype "passive"))
      (node (ref "C37") (pin "1") (pinfunction "1_1") (pintype "passive"))
      (node (ref "C38") (pin "1") (pinfunction "1_1") (pintype "passive"))
      (node (ref "C39") (pin "1") (pinfunction "1_1") (pintype "passive"))
      (node (ref "C40") (pin "1") (pinfunction "1_1") (pintype "passive"))
      (node (ref "C41") (pin "2") (pinfunction "2_2") (pintype "passive"))
      (node (ref "C42") (pin "1") (pinfunction "1_1") (pintype "passive"))
      (node (ref "C43") (pin "1") (pinfunction "1_1") (pintype "passive"))
      (node (ref "C44") (pin "1") (pinfunction "1_1") (pintype "passive"))
      (node (ref "C45") (pin "1") (pinfunction "1_1") (pintype "passive"))
      (node (ref "C47") (pin "1") (pinfunction "1_1") (pintype "passive"))
      (node (ref "C48") (pin "1") (pinfunction "1_1") (pintype "passive"))
      (node (ref "C49") (pin "1") (pinfunction "1_1") (pintype "passive"))
      (node (ref "C50") (pin "1") (pinfunction "1_1") (pintype "passive"))
      (node (ref "C51") (pin "1") (pinfunction "1_1") (pintype "passive"))
      (node (ref "C52") (pin "1") (pinfunction "1_1") (pintype "passive"))
      (node (ref "C53") (pin "2") (pinfunction "2_2") (pintype "passive"))
      (node (ref "C54") (pin "1") (pinfunction "1_1") (pintype "passive"))
      (node (ref "C55") (pin "1") (pinfunction "1_1") (pintype "passive"))
      (node (ref "C56") (pin "1") (pinfunction "1_1") (pintype "passive"))
      (node (ref "C57") (pin "1") (pinfunction "1_1") (pintype "passive"))
      (node (ref "C59") (pin "1") (pinfunction "1_1") (pintype "passive"))
      (node (ref "C60") (pin "1") (pinfunction "1_1") (pintype "passive"))
      (node (ref "C61") (pin "1") (pinfunction "1_1") (pintype "passive"))
      (node (ref "C62") (pin "1") (pinfunction "1_1") (pintype "passive"))
      (node (ref "C63") (pin "1") (pinfunction "1_1") (pintype "passive"))
      (node (ref "C64") (pin "1") (pinfunction "1_1") (pintype "passive"))
      (node (ref "C65") (pin "2") (pinfunction "2_2") (pintype "passive"))
      (node (ref "C66") (pin "1") (pinfunction "1_1") (pintype "passive"))
      (node (ref "C67") (pin "1") (pinfunction "1_1") (pintype "passive"))
      (node (ref "C68") (pin "1") (pinfunction "1_1") (pintype "passive"))
      (node (ref "C69") (pin "1") (pinfunction "1_1") (pintype "passive"))
      (node (ref "C71") (pin "1") (pinfunction "1_1") (pintype "passive"))
      (node (ref "C72") (pin "1") (pinfunction "1_1") (pintype "passive"))
      (node (ref "C73") (pin "1") (pinfunction "1_1") (pintype "passive"))
      (node (ref "C74") (pin "1") (pinfunction "1_1") (pintype "passive"))
      (node (ref "C75") (pin "1") (pinfunction "1_1") (pintype "passive"))
      (node (ref "C76") (pin "1") (pinfunction "1_1") (pintype "passive"))
      (node (ref "C77") (pin "2") (pinfunction "2_2") (pintype "passive"))
      (node (ref "C78") (pin "1") (pinfunction "1_1") (pintype "passive"))
      (node (ref "C79") (pin "1") (pinfunction "1_1") (pintype "passive"))
      (node (ref "C80") (pin "1") (pinfunction "1_1") (pintype "passive"))
      (node (ref "C81") (pin "1") (pinfunction "1_1") (pintype "passive"))
      (node (ref "C83") (pin "1") (pinfunction "1_1") (pintype "passive"))
      (node (ref "C84") (pin "1") (pinfunction "1_1") (pintype "passive"))
      (node (ref "C85") (pin "1") (pinfunction "1_1") (pintype "passive"))
      (node (ref "C86") (pin "1") (pinfunction "1_1") (pintype "passive"))
      (node (ref "C87") (pin "1") (pinfunction "1_1") (pintype "passive"))
      (node (ref "C88") (pin "1") (pinfunction "1_1") (pintype "passive"))
      (node (ref "C89") (pin "2") (pinfunction "2_2") (pintype "passive"))
      (node (ref "C90") (pin "1") (pinfunction "1_1") (pintype "passive"))
      (node (ref "C91") (pin "1") (pinfunction "1_1") (pintype "passive"))
      (node (ref "C92") (pin "1") (pinfunction "1_1") (pintype "passive"))
      (node (ref "C93") (pin "1") (pinfunction "1_1") (pintype "passive"))
      (node (ref "C95") (pin "1") (pinfunction "1_1") (pintype "passive"))
      (node (ref "C96") (pin "1") (pinfunction "1_1") (pintype "passive"))
      (node (ref "C97") (pin "1") (pinfunction "1_1") (pintype "passive"))
      (node (ref "C98") (pin "1") (pinfunction "1_1") (pintype "passive"))
      (node (ref "C99") (pin "1") (pinfunction "1_1") (pintype "passive"))
      (node (ref "U10") (pin "15") (pinfunction "DGND_15") (pintype "passive"))
      (node (ref "U10") (pin "19") (pinfunction "AGND_19") (pintype "passive"))
      (node (ref "U11") (pin "5") (pinfunction "+IN_B_5") (pintype "input"))
      (node (ref "U12") (pin "15") (pinfunction "DGND_15") (pintype "passive"))
      (node (ref "U12") (pin "19") (pinfunction "AGND_19") (pintype "passive"))
      (node (ref "U13") (pin "5") (pinfunction "+IN_B_5") (pintype "input"))
      (node (ref "U14") (pin "15") (pinfunction "DGND_15") (pintype "passive"))
      (node (ref "U14") (pin "19") (pinfunction "AGND_19") (pintype "passive"))
      (node (ref "U15") (pin "5") (pinfunction "+IN_B_5") (pintype "input"))
      (node (ref "U16") (pin "15") (pinfunction "DGND_15") (pintype "passive"))
      (node (ref "U16") (pin "19") (pinfunction "AGND_19") (pintype "passive"))
      (node (ref "U17") (pin "5") (pinfunction "+IN_B_5") (pintype "input"))
      (node (ref "U18") (pin "15") (pinfunction "DGND_15") (pintype "passive"))
      (node (ref "U18") (pin "19") (pinfunction "AGND_19") (pintype "passive"))
      (node (ref "U19") (pin "5") (pinfunction "+IN_B_5") (pintype "input"))
      (node (ref "U20") (pin "15") (pinfunction "DGND_15") (pintype "passive"))
      (node (ref "U20") (pin "19") (pinfunction "AGND_19") (pintype "passive"))
      (node (ref "U21") (pin "5") (pinfunction "+IN_B_5") (pintype "input"))
      (node (ref "U22") (pin "15") (pinfunction "DGND_15") (pintype "passive"))
      (node (ref "U22") (pin "19") (pinfunction "AGND_19") (pintype "passive"))
      (node (ref "U23") (pin "5") (pinfunction "+IN_B_5") (pintype "input"))
      (node (ref "U24") (pin "15") (pinfunction "DGND_15") (pintype "passive"))
      (node (ref "U24") (pin "19") (pinfunction "AGND_19") (pintype "passive"))
      (node (ref "U25") (pin "5") (pinfunction "+IN_B_5") (pintype "input"))
      (node (ref "U26") (pin "15") (pinfunction "DGND_15") (pintype "passive"))
      (node (ref "U26") (pin "19") (pinfunction "AGND_19") (pintype "passive"))
      (node (ref "U27") (pin "5") (pinfunction "+IN_B_5") (pintype "input"))
      (node (ref "U4") (pin "15") (pinfunction "DGND_15") (pintype "passive"))
      (node (ref "U4") (pin "19") (pinfunction "AGND_19") (pintype "passive"))
      (node (ref "U5") (pin "5") (pinfunction "+IN_B_5") (pintype "input"))
      (node (ref "U6") (pin "15") (pinfunction "DGND_15") (pintype "passive"))
      (node (ref "U6") (pin "19") (pinfunction "AGND_19") (pintype "passive"))
      (node (ref "U7") (pin "5") (pinfunction "+IN_B_5") (pintype "input"))
      (node (ref "U8") (pin "15") (pinfunction "DGND_15") (pintype "passive"))
      (node (ref "U8") (pin "19") (pinfunction "AGND_19") (pintype "passive"))
      (node (ref "U9") (pin "5") (pinfunction "+IN_B_5") (pintype "input"))
    )
    (net (code "174") (name "INV_1") (class "Default")
      (node (ref "C34") (pin "1") (pinfunction "1_1") (pintype "passive"))
      (node (ref "U30") (pin "6") (pinfunction "-INB_6") (pintype "input"))
      (node (ref "U4") (pin "1") (pinfunction "INV_1") (pintype "input"))
    )
    (net (code "175") (name "INV_7") (class "Default")
      (node (ref "C106") (pin "1") (pinfunction "1_1") (pintype "passive"))
      (node (ref "U16") (pin "1") (pinfunction "INV_1") (pintype "input"))
      (node (ref "U30") (pin "2") (pinfunction "-INA_2") (pintype "input"))
    )
    (net (code "176") (name "LDAC") (class "Default")
      (node (ref "U10") (pin "8") (pinfunction "~{LDAC}_8") (pintype "input"))
      (node (ref "U12") (pin "8") (pinfunction "~{LDAC}_8") (pintype "input"))
      (node (ref "U14") (pin "8") (pinfunction "~{LDAC}_8") (pintype "input"))
      (node (ref "U16") (pin "8") (pinfunction "~{LDAC}_8") (pintype "input"))
      (node (ref "U18") (pin "8") (pinfunction "~{LDAC}_8") (pintype "input"))
      (node (ref "U20") (pin "8") (pinfunction "~{LDAC}_8") (pintype "input"))
      (node (ref "U22") (pin "8") (pinfunction "~{LDAC}_8") (pintype "input"))
      (node (ref "U24") (pin "8") (pinfunction "~{LDAC}_8") (pintype "input"))
      (node (ref "U26") (pin "8") (pinfunction "~{LDAC}_8") (pintype "input"))
      (node (ref "U4") (pin "8") (pinfunction "~{LDAC}_8") (pintype "input"))
      (node (ref "U6") (pin "8") (pinfunction "~{LDAC}_8") (pintype "input"))
      (node (ref "U8") (pin "8") (pinfunction "~{LDAC}_8") (pintype "input"))
    )
    (net (code "177") (name "Net-(U4-VREFNF)") (class "Default")
      (node (ref "U4") (pin "16") (pinfunction "VREFNF_16") (pintype "input"))
      (node (ref "U5") (pin "7") (pinfunction "OUT_B_7") (pintype "output"))
    )
    (net (code "178") (name "Net-(U4-VREFNS)") (class "Default")
      (node (ref "U4") (pin "17") (pinfunction "VREFNS_17") (pintype "input"))
      (node (ref "U5") (pin "6") (pinfunction "-IN_B_6") (pintype "input"))
    )
    (net (code "179") (name "Net-(U4-VREFPF)") (class "Default")
      (node (ref "U4") (pin "4") (pinfunction "VREFPF_4") (pintype "input"))
      (node (ref "U5") (pin "1") (pinfunction "OUT_A_1") (pintype "output"))
    )
    (net (code "180") (name "Net-(U4-VREFPS)") (class "Default")
      (node (ref "U4") (pin "3") (pinfunction "VREFPS_3") (pintype "input"))
      (node (ref "U5") (pin "2") (pinfunction "-IN_A_2") (pintype "input"))
    )
    (net (code "181") (name "Net-(U6-INV)") (class "Default")
      (node (ref "C46") (pin "1") (pinfunction "1_1") (pintype "passive"))
      (node (ref "U6") (pin "1") (pinfunction "INV_1") (pintype "input"))
    )
    (net (code "182") (name "Net-(U6-RFB)") (class "Default")
      (node (ref "C46") (pin "2") (pinfunction "2_2") (pintype "passive"))
      (node (ref "U6") (pin "20") (pinfunction "RFB_20") (pintype "input"))
    )
    (net (code "183") (name "Net-(U6-VOUT)") (class "Default")
      (node (ref "C47") (pin "2") (pinfunction "2_2") (pintype "passive"))
      (node (ref "U6") (pin "2") (pinfunction "VOUT_2") (pintype "output"))
    )
    (net (code "184") (name "Net-(U6-VREFNF)") (class "Default")
      (node (ref "U6") (pin "16") (pinfunction "VREFNF_16") (pintype "input"))
      (node (ref "U7") (pin "7") (pinfunction "OUT_B_7") (pintype "output"))
    )
    (net (code "185") (name "Net-(U6-VREFNS)") (class "Default")
      (node (ref "U6") (pin "17") (pinfunction "VREFNS_17") (pintype "input"))
      (node (ref "U7") (pin "6") (pinfunction "-IN_B_6") (pintype "input"))
    )
    (net (code "186") (name "Net-(U6-VREFPF)") (class "Default")
      (node (ref "U6") (pin "4") (pinfunction "VREFPF_4") (pintype "input"))
      (node (ref "U7") (pin "1") (pinfunction "OUT_A_1") (pintype "output"))
    )
    (net (code "187") (name "Net-(U6-VREFPS)") (class "Default")
      (node (ref "U6") (pin "3") (pinfunction "VREFPS_3") (pintype "input"))
      (node (ref "U7") (pin "2") (pinfunction "-IN_A_2") (pintype "input"))
    )
    (net (code "188") (name "Net-(U8-INV)") (class "Default")
      (node (ref "C58") (pin "1") (pinfunction "1_1") (pintype "passive"))
      (node (ref "U8") (pin "1") (pinfunction "INV_1") (pintype "input"))
    )
    (net (code "189") (name "Net-(U8-RFB)") (class "Default")
      (node (ref "C58") (pin "2") (pinfunction "2_2") (pintype "passive"))
      (node (ref "U8") (pin "20") (pinfunction "RFB_20") (pintype "input"))
    )
    (net (code "190") (name "Net-(U8-VOUT)") (class "Default")
      (node (ref "C59") (pin "2") (pinfunction "2_2") (pintype "passive"))
      (node (ref "U8") (pin "2") (pinfunction "VOUT_2") (pintype "output"))
    )
    (net (code "191") (name "Net-(U8-VREFNF)") (class "Default")
      (node (ref "U8") (pin "16") (pinfunction "VREFNF_16") (pintype "input"))
      (node (ref "U9") (pin "7") (pinfunction "OUT_B_7") (pintype "output"))
    )
    (net (code "192") (name "Net-(U8-VREFNS)") (class "Default")
      (node (ref "U8") (pin "17") (pinfunction "VREFNS_17") (pintype "input"))
      (node (ref "U9") (pin "6") (pinfunction "-IN_B_6") (pintype "input"))
    )
    (net (code "193") (name "Net-(U8-VREFPF)") (class "Default")
      (node (ref "U8") (pin "4") (pinfunction "VREFPF_4") (pintype "input"))
      (node (ref "U9") (pin "1") (pinfunction "OUT_A_1") (pintype "output"))
    )
    (net (code "194") (name "Net-(U8-VREFPS)") (class "Default")
      (node (ref "U8") (pin "3") (pinfunction "VREFPS_3") (pintype "input"))
      (node (ref "U9") (pin "2") (pinfunction "-IN_A_2") (pintype "input"))
    )
    (net (code "195") (name "Net-(U10-INV)") (class "Default")
      (node (ref "C70") (pin "1") (pinfunction "1_1") (pintype "passive"))
      (node (ref "U10") (pin "1") (pinfunction "INV_1") (pintype "input"))
    )
    (net (code "196") (name "Net-(U10-RFB)") (class "Default")
      (node (ref "C70") (pin "2") (pinfunction "2_2") (pintype "passive"))
      (node (ref "U10") (pin "20") (pinfunction "RFB_20") (pintype "input"))
    )
    (net (code "197") (name "Net-(U10-VOUT)") (class "Default")
      (node (ref "C71") (pin "2") (pinfunction "2_2") (pintype "passive"))
      (node (ref "U10") (pin "2") (pinfunction "VOUT_2") (pintype "output"))
    )
    (net (code "198") (name "Net-(U10-VREFNF)") (class "Default")
      (node (ref "U10") (pin "16") (pinfunction "VREFNF_16") (pintype "input"))
      (node (ref "U11") (pin "7") (pinfunction "OUT_B_7") (pintype "output"))
    )
    (net (code "199") (name "Net-(U10-VREFNS)") (class "Default")
      (node (ref "U10") (pin "17") (pinfunction "VREFNS_17") (pintype "input"))
      (node (ref "U11") (pin "6") (pinfunction "-IN_B_6") (pintype "input"))
    )
    (net (code "200") (name "Net-(U10-VREFPF)") (class "Default")
      (node (ref "U10") (pin "4") (pinfunction "VREFPF_4") (pintype "input"))
      (node (ref "U11") (pin "1") (pinfunction "OUT_A_1") (pintype "output"))
    )
    (net (code "201") (name "Net-(U10-VREFPS)") (class "Default")
      (node (ref "U10") (pin "3") (pinfunction "VREFPS_3") (pintype "input"))
      (node (ref "U11") (pin "2") (pinfunction "-IN_A_2") (pintype "input"))
    )
    (net (code "202") (name "Net-(U12-INV)") (class "Default")
      (node (ref "C82") (pin "1") (pinfunction "1_1") (pintype "passive"))
      (node (ref "U12") (pin "1") (pinfunction "INV_1") (pintype "input"))
    )
    (net (code "203") (name "Net-(U12-RFB)") (class "Default")
      (node (ref "C82") (pin "2") (pinfunction "2_2") (pintype "passive"))
      (node (ref "U12") (pin "20") (pinfunction "RFB_20") (pintype "input"))
    )
    (net (code "204") (name "Net-(U12-VOUT)") (class "Default")
      (node (ref "C83") (pin "2") (pinfunction "2_2") (pintype "passive"))
      (node (ref "U12") (pin "2") (pinfunction "VOUT_2") (pintype "output"))
    )
    (net (code "205") (name "Net-(U12-VREFNF)") (class "Default")
      (node (ref "U12") (pin "16") (pinfunction "VREFNF_16") (pintype "input"))
      (node (ref "U13") (pin "7") (pinfunction "OUT_B_7") (pintype "output"))
    )
    (net (code "206") (name "Net-(U12-VREFNS)") (class "Default")
      (node (ref "U12") (pin "17") (pinfunction "VREFNS_17") (pintype "input"))
      (node (ref "U13") (pin "6") (pinfunction "-IN_B_6") (pintype "input"))
    )
    (net (code "207") (name "Net-(U12-VREFPF)") (class "Default")
      (node (ref "U12") (pin "4") (pinfunction "VREFPF_4") (pintype "input"))
      (node (ref "U13") (pin "1") (pinfunction "OUT_A_1") (pintype "output"))
    )
    (net (code "208") (name "Net-(U12-VREFPS)") (class "Default")
      (node (ref "U12") (pin "3") (pinfunction "VREFPS_3") (pintype "input"))
      (node (ref "U13") (pin "2") (pinfunction "-IN_A_2") (pintype "input"))
    )
    (net (code "209") (name "Net-(U14-INV)") (class "Default")
      (node (ref "C94") (pin "1") (pinfunction "1_1") (pintype "passive"))
      (node (ref "U14") (pin "1") (pinfunction "INV_1") (pintype "input"))
    )
    (net (code "210") (name "Net-(U14-RFB)") (class "Default")
      (node (ref "C94") (pin "2") (pinfunction "2_2") (pintype "passive"))
      (node (ref "U14") (pin "20") (pinfunction "RFB_20") (pintype "input"))
    )
    (net (code "211") (name "Net-(U14-VOUT)") (class "Default")
      (node (ref "C95") (pin "2") (pinfunction "2_2") (pintype "passive"))
      (node (ref "U14") (pin "2") (pinfunction "VOUT_2") (pintype "output"))
    )
    (net (code "212") (name "Net-(U14-VREFNF)") (class "Default")
      (node (ref "U14") (pin "16") (pinfunction "VREFNF_16") (pintype "input"))
      (node (ref "U15") (pin "7") (pinfunction "OUT_B_7") (pintype "output"))
    )
    (net (code "213") (name "Net-(U14-VREFNS)") (class "Default")
      (node (ref "U14") (pin "17") (pinfunction "VREFNS_17") (pintype "input"))
      (node (ref "U15") (pin "6") (pinfunction "-IN_B_6") (pintype "input"))
    )
    (net (code "214") (name "Net-(U14-VREFPF)") (class "Default")
      (node (ref "U14") (pin "4") (pinfunction "VREFPF_4") (pintype "input"))
      (node (ref "U15") (pin "1") (pinfunction "OUT_A_1") (pintype "output"))
    )
    (net (code "215") (name "Net-(U14-VREFPS)") (class "Default")
      (node (ref "U14") (pin "3") (pinfunction "VREFPS_3") (pintype "input"))
      (node (ref "U15") (pin "2") (pinfunction "-IN_A_2") (pintype "input"))
    )
    (net (code "216") (name "Net-(U16-VREFNF)") (class "Default")
      (node (ref "U16") (pin "16") (pinfunction "VREFNF_16") (pintype "input"))
      (node (ref "U17") (pin "7") (pinfunction "OUT_B_7") (pintype "output"))
    )
    (net (code "217") (name "Net-(U16-VREFNS)") (class "Default")
      (node (ref "U16") (pin "17") (pinfunction "VREFNS_17") (pintype "input"))
      (node (ref "U17") (pin "6") (pinfunction "-IN_B_6") (pintype "input"))
    )
    (net (code "218") (name "Net-(U16-VREFPF)") (class "Default")
      (node (ref "U16") (pin "4") (pinfunction "VREFPF_4") (pintype "input"))
      (node (ref "U17") (pin "1") (pinfunction "OUT_A_1") (pintype "output"))
    )
    (net (code "219") (name "Net-(U16-VREFPS)") (class "Default")
      (node (ref "U16") (pin "3") (pinfunction "VREFPS_3") (pintype "input"))
      (node (ref "U17") (pin "2") (pinfunction "-IN_A_2") (pintype "input"))
    )
    (net (code "220") (name "Net-(U18-INV)") (class "Default")
      (node (ref "C118") (pin "1") (pinfunction "1_1") (pintype "passive"))
      (node (ref "U18") (pin "1") (pinfunction "INV_1") (pintype "input"))
    )
    (net (code "221") (name "Net-(U18-RFB)") (class "Default")
      (node (ref "C118") (pin "2") (pinfunction "2_2") (pintype "passive"))
      (node (ref "U18") (pin "20") (pinfunction "RFB_20") (pintype "input"))
    )
    (net (code "222") (name "Net-(U18-VOUT)") (class "Default")
      (node (ref "C119") (pin "2") (pinfunction "2_2") (pintype "passive"))
      (node (ref "U18") (pin "2") (pinfunction "VOUT_2") (pintype "output"))
    )
    (net (code "223") (name "Net-(U18-VREFNF)") (class "Default")
      (node (ref "U18") (pin "16") (pinfunction "VREFNF_16") (pintype "input"))
      (node (ref "U19") (pin "7") (pinfunction "OUT_B_7") (pintype "output"))
    )
    (net (code "224") (name "Net-(U18-VREFNS)") (class "Default")
      (node (ref "U18") (pin "17") (pinfunction "VREFNS_17") (pintype "input"))
      (node (ref "U19") (pin "6") (pinfunction "-IN_B_6") (pintype "input"))
    )
    (net (code "225") (name "Net-(U18-VREFPF)") (class "Default")
      (node (ref "U18") (pin "4") (pinfunction "VREFPF_4") (pintype "input"))
      (node (ref "U19") (pin "1") (pinfunction "OUT_A_1") (pintype "output"))
    )
    (net (code "226") (name "Net-(U18-VREFPS)") (class "Default")
      (node (ref "U18") (pin "3") (pinfunction "VREFPS_3") (pintype "input"))
      (node (ref "U19") (pin "2") (pinfunction "-IN_A_2") (pintype "input"))
    )
    (net (code "227") (name "Net-(U20-INV)") (class "Default")
      (node (ref "C130") (pin "1") (pinfunction "1_1") (pintype "passive"))
      (node (ref "U20") (pin "1") (pinfunction "INV_1") (pintype "input"))
    )
    (net (code "228") (name "Net-(U20-RFB)") (class "Default")
      (node (ref "C130") (pin "2") (pinfunction "2_2") (pintype "passive"))
      (node (ref "U20") (pin "20") (pinfunction "RFB_20") (pintype "input"))
    )
    (net (code "229") (name "Net-(U20-VOUT)") (class "Default")
      (node (ref "C131") (pin "2") (pinfunction "2_2") (pintype "passive"))
      (node (ref "U20") (pin "2") (pinfunction "VOUT_2") (pintype "output"))
    )
    (net (code "230") (name "Net-(U20-VREFNF)") (class "Default")
      (node (ref "U20") (pin "16") (pinfunction "VREFNF_16") (pintype "input"))
      (node (ref "U21") (pin "7") (pinfunction "OUT_B_7") (pintype "output"))
    )
    (net (code "231") (name "Net-(U20-VREFNS)") (class "Default")
      (node (ref "U20") (pin "17") (pinfunction "VREFNS_17") (pintype "input"))
      (node (ref "U21") (pin "6") (pinfunction "-IN_B_6") (pintype "input"))
    )
    (net (code "232") (name "Net-(U20-VREFPF)") (class "Default")
      (node (ref "U20") (pin "4") (pinfunction "VREFPF_4") (pintype "input"))
      (node (ref "U21") (pin "1") (pinfunction "OUT_A_1") (pintype "output"))
    )
    (net (code "233") (name "Net-(U20-VREFPS)") (class "Default")
      (node (ref "U20") (pin "3") (pinfunction "VREFPS_3") (pintype "input"))
      (node (ref "U21") (pin "2") (pinfunction "-IN_A_2") (pintype "input"))
    )
    (net (code "234") (name "Net-(U22-INV)") (class "Default")
      (node (ref "C142") (pin "1") (pinfunction "1_1") (pintype "passive"))
      (node (ref "U22") (pin "1") (pinfunction "INV_1") (pintype "input"))
    )
    (net (code "235") (name "Net-(U22-RFB)") (class "Default")
      (node (ref "C142") (pin "2") (pinfunction "2_2") (pintype "passive"))
      (node (ref "U22") (pin "20") (pinfunction "RFB_20") (pintype "input"))
    )
    (net (code "236") (name "Net-(U22-VOUT)") (class "Default")
      (node (ref "C143") (pin "2") (pinfunction "2_2") (pintype "passive"))
      (node (ref "U22") (pin "2") (pinfunction "VOUT_2") (pintype "output"))
    )
    (net (code "237") (name "Net-(U22-VREFNF)") (class "Default")
      (node (ref "U22") (pin "16") (pinfunction "VREFNF_16") (pintype "input"))
      (node (ref "U23") (pin "7") (pinfunction "OUT_B_7") (pintype "output"))
    )
    (net (code "238") (name "Net-(U22-VREFNS)") (class "Default")
      (node (ref "U22") (pin "17") (pinfunction "VREFNS_17") (pintype "input"))
      (node (ref "U23") (pin "6") (pinfunction "-IN_B_6") (pintype "input"))
    )
    (net (code "239") (name "Net-(U22-VREFPF)") (class "Default")
      (node (ref "U22") (pin "4") (pinfunction "VREFPF_4") (pintype "input"))
      (node (ref "U23") (pin "1") (pinfunction "OUT_A_1") (pintype "output"))
    )
    (net (code "240") (name "Net-(U22-VREFPS)") (class "Default")
      (node (ref "U22") (pin "3") (pinfunction "VREFPS_3") (pintype "input"))
      (node (ref "U23") (pin "2") (pinfunction "-IN_A_2") (pintype "input"))
    )
    (net (code "241") (name "Net-(U24-INV)") (class "Default")
      (node (ref "C154") (pin "1") (pinfunction "1_1") (pintype "passive"))
      (node (ref "U24") (pin "1") (pinfunction "INV_1") (pintype "input"))
    )
    (net (code "242") (name "Net-(U24-RFB)") (class "Default")
      (node (ref "C154") (pin "2") (pinfunction "2_2") (pintype "passive"))
      (node (ref "U24") (pin "20") (pinfunction "RFB_20") (pintype "input"))
    )
    (net (code "243") (name "Net-(U24-VOUT)") (class "Default")
      (node (ref "C155") (pin "2") (pinfunction "2_2") (pintype "passive"))
      (node (ref "U24") (pin "2") (pinfunction "VOUT_2") (pintype "output"))
    )
    (net (code "244") (name "Net-(U24-VREFNF)") (class "Default")
      (node (ref "U24") (pin "16") (pinfunction "VREFNF_16") (pintype "input"))
      (node (ref "U25") (pin "7") (pinfunction "OUT_B_7") (pintype "output"))
    )
    (net (code "245") (name "Net-(U24-VREFNS)") (class "Default")
      (node (ref "U24") (pin "17") (pinfunction "VREFNS_17") (pintype "input"))
      (node (ref "U25") (pin "6") (pinfunction "-IN_B_6") (pintype "input"))
    )
    (net (code "246") (name "Net-(U24-VREFPF)") (class "Default")
      (node (ref "U24") (pin "4") (pinfunction "VREFPF_4") (pintype "input"))
      (node (ref "U25") (pin "1") (pinfunction "OUT_A_1") (pintype "output"))
    )
    (net (code "247") (name "Net-(U24-VREFPS)") (class "Default")
      (node (ref "U24") (pin "3") (pinfunction "VREFPS_3") (pintype "input"))
      (node (ref "U25") (pin "2") (pinfunction "-IN_A_2") (pintype "input"))
    )
    (net (code "248") (name "Net-(U26-INV)") (class "Default")
      (node (ref "C166") (pin "1") (pinfunction "1_1") (pintype "passive"))
      (node (ref "U26") (pin "1") (pinfunction "INV_1") (pintype "input"))
    )
    (net (code "249") (name "Net-(U26-RFB)") (class "Default")
      (node (ref "C166") (pin "2") (pinfunction "2_2") (pintype "passive"))
      (node (ref "U26") (pin "20") (pinfunction "RFB_20") (pintype "input"))
    )
    (net (code "250") (name "Net-(U26-VOUT)") (class "Default")
      (node (ref "C167") (pin "2") (pinfunction "2_2") (pintype "passive"))
      (node (ref "U26") (pin "2") (pinfunction "VOUT_2") (pintype "output"))
    )
    (net (code "251") (name "Net-(U26-VREFNF)") (class "Default")
      (node (ref "U26") (pin "16") (pinfunction "VREFNF_16") (pintype "input"))
      (node (ref "U27") (pin "7") (pinfunction "OUT_B_7") (pintype "output"))
    )
    (net (code "252") (name "Net-(U26-VREFNS)") (class "Default")
      (node (ref "U26") (pin "17") (pinfunction "VREFNS_17") (pintype "input"))
      (node (ref "U27") (pin "6") (pinfunction "-IN_B_6") (pintype "input"))
    )
    (net (code "253") (name "Net-(U26-VREFPF)") (class "Default")
      (node (ref "U26") (pin "4") (pinfunction "VREFPF_4") (pintype "input"))
      (node (ref "U27") (pin "1") (pinfunction "OUT_A_1") (pintype "output"))
    )
    (net (code "254") (name "Net-(U26-VREFPS)") (class "Default")
      (node (ref "U26") (pin "3") (pinfunction "VREFPS_3") (pintype "input"))
      (node (ref "U27") (pin "2") (pinfunction "-IN_A_2") (pintype "input"))
    )
    (net (code "255") (name "OUT0") (class "Default")
      (node (ref "ISO9") (pin "3") (pinfunction "A1_3") (pintype "bidirectional"))
    )
    (net (code "256") (name "OUT1") (class "Default")
      (node (ref "ISO9") (pin "4") (pinfunction "A2_4") (pintype "bidirectional"))
    )
    (net (code "257") (name "OUT2") (class "Default")
      (node (ref "ISO9") (pin "5") (pinfunction "A3_5") (pintype "bidirectional"))
    )
    (net (code "258") (name "OUT3") (class "Default")
      (node (ref "ISO9") (pin "6") (pinfunction "A4_6") (pintype "bidirectional"))
    )
    (net (code "259") (name "OUT4") (class "Default")
      (node (ref "ISO9") (pin "7") (pinfunction "A5_7") (pintype "bidirectional"))
    )
    (net (code "260") (name "OUT5") (class "Default")
      (node (ref "ISO10") (pin "3") (pinfunction "A1_3") (pintype "bidirectional"))
    )
    (net (code "261") (name "OUT6") (class "Default")
      (node (ref "ISO10") (pin "4") (pinfunction "A2_4") (pintype "bidirectional"))
    )
    (net (code "262") (name "OUT7") (class "Default")
      (node (ref "ISO10") (pin "5") (pinfunction "A3_5") (pintype "bidirectional"))
    )
    (net (code "263") (name "OUTCLK-IN") (class "Default")
      (node (ref "ISO1") (pin "10") (pinfunction "B5_10") (pintype "bidirectional"))
    )
    (net (code "264") (name "OUTCLK-OUT") (class "Default")
      (node (ref "ISO10") (pin "6") (pinfunction "A4_6") (pintype "bidirectional"))
    )
    (net (code "265") (name "RESET") (class "Default")
      (node (ref "ISO5") (pin "13") (pinfunction "B2_13") (pintype "bidirectional"))
    )
    (net (code "266") (name "RFB_1") (class "Default")
      (node (ref "C34") (pin "2") (pinfunction "2_2") (pintype "passive"))
      (node (ref "R5") (pin "1") (pinfunction "1_1") (pintype "passive"))
      (node (ref "U30") (pin "7") (pinfunction "OUTB_7") (pintype "output"))
      (node (ref "U4") (pin "20") (pinfunction "RFB_20") (pintype "input"))
    )
    (net (code "267") (name "RFB_7") (class "Default")
      (node (ref "C106") (pin "2") (pinfunction "2_2") (pintype "passive"))
      (node (ref "R4") (pin "1") (pinfunction "1_1") (pintype "passive"))
      (node (ref "U16") (pin "20") (pinfunction "RFB_20") (pintype "input"))
      (node (ref "U30") (pin "1") (pinfunction "OUTA_1") (pintype "output"))
    )
    (net (code "268") (name "SCLK_1") (class "Default")
      (node (ref "U4") (pin "13") (pinfunction "SCLK_13") (pintype "input"))
    )
    (net (code "269") (name "SCLK_2") (class "Default")
      (node (ref "U6") (pin "13") (pinfunction "SCLK_13") (pintype "input"))
    )
    (net (code "270") (name "SCLK_3") (class "Default")
      (node (ref "U8") (pin "13") (pinfunction "SCLK_13") (pintype "input"))
    )
    (net (code "271") (name "SCLK_4") (class "Default")
      (node (ref "U10") (pin "13") (pinfunction "SCLK_13") (pintype "input"))
    )
    (net (code "272") (name "SCLK_5") (class "Default")
      (node (ref "U12") (pin "13") (pinfunction "SCLK_13") (pintype "input"))
    )
    (net (code "273") (name "SCLK_6") (class "Default")
      (node (ref "U14") (pin "13") (pinfunction "SCLK_13") (pintype "input"))
    )
    (net (code "274") (name "SCLK_7") (class "Default")
      (node (ref "U16") (pin "13") (pinfunction "SCLK_13") (pintype "input"))
    )
    (net (code "275") (name "SCLK_8") (class "Default")
      (node (ref "U18") (pin "13") (pinfunction "SCLK_13") (pintype "input"))
    )
    (net (code "276") (name "SCLK_9") (class "Default")
      (node (ref "U20") (pin "13") (pinfunction "SCLK_13") (pintype "input"))
    )
    (net (code "277") (name "SCLK_10") (class "Default")
      (node (ref "U22") (pin "13") (pinfunction "SCLK_13") (pintype "input"))
    )
    (net (code "278") (name "SCLK_11") (class "Default")
      (node (ref "U24") (pin "13") (pinfunction "SCLK_13") (pintype "input"))
    )
    (net (code "279") (name "SCLK_12") (class "Default")
      (node (ref "U26") (pin "13") (pinfunction "SCLK_13") (pintype "input"))
    )
    (net (code "280") (name "SDIN_1") (class "Default")
      (node (ref "U4") (pin "12") (pinfunction "SDIN_12") (pintype "input"))
    )
    (net (code "281") (name "SDIN_2") (class "Default")
      (node (ref "U6") (pin "12") (pinfunction "SDIN_12") (pintype "input"))
    )
    (net (code "282") (name "SDIN_3") (class "Default")
      (node (ref "U8") (pin "12") (pinfunction "SDIN_12") (pintype "input"))
    )
    (net (code "283") (name "SDIN_4") (class "Default")
      (node (ref "U10") (pin "12") (pinfunction "SDIN_12") (pintype "input"))
    )
    (net (code "284") (name "SDIN_5") (class "Default")
      (node (ref "U12") (pin "12") (pinfunction "SDIN_12") (pintype "input"))
    )
    (net (code "285") (name "SDIN_6") (class "Default")
      (node (ref "U14") (pin "12") (pinfunction "SDIN_12") (pintype "input"))
    )
    (net (code "286") (name "SDIN_7") (class "Default")
      (node (ref "U16") (pin "12") (pinfunction "SDIN_12") (pintype "input"))
    )
    (net (code "287") (name "SDIN_8") (class "Default")
      (node (ref "U18") (pin "12") (pinfunction "SDIN_12") (pintype "input"))
    )
    (net (code "288") (name "SDIN_9") (class "Default")
      (node (ref "U20") (pin "12") (pinfunction "SDIN_12") (pintype "input"))
    )
    (net (code "289") (name "SDIN_10") (class "Default")
      (node (ref "U22") (pin "12") (pinfunction "SDIN_12") (pintype "input"))
    )
    (net (code "290") (name "SDIN_11") (class "Default")
      (node (ref "U24") (pin "12") (pinfunction "SDIN_12") (pintype "input"))
    )
    (net (code "291") (name "SDIN_12") (class "Default")
      (node (ref "U26") (pin "12") (pinfunction "SDIN_12") (pintype "input"))
    )
    (net (code "292") (name "SDO_1") (class "Default")
      (node (ref "U4") (pin "11") (pinfunction "SDO_11") (pintype "output"))
    )
    (net (code "293") (name "SDO_2") (class "Default")
      (node (ref "U6") (pin "11") (pinfunction "SDO_11") (pintype "output"))
    )
    (net (code "294") (name "SDO_3") (class "Default")
      (node (ref "U8") (pin "11") (pinfunction "SDO_11") (pintype "output"))
    )
    (net (code "295") (name "SDO_4") (class "Default")
      (node (ref "U10") (pin "11") (pinfunction "SDO_11") (pintype "output"))
    )
    (net (code "296") (name "SDO_5") (class "Default")
      (node (ref "U12") (pin "11") (pinfunction "SDO_11") (pintype "output"))
    )
    (net (code "297") (name "SDO_6") (class "Default")
      (node (ref "U14") (pin "11") (pinfunction "SDO_11") (pintype "output"))
    )
    (net (code "298") (name "SDO_7") (class "Default")
      (node (ref "U16") (pin "11") (pinfunction "SDO_11") (pintype "output"))
    )
    (net (code "299") (name "SDO_8") (class "Default")
      (node (ref "U18") (pin "11") (pinfunction "SDO_11") (pintype "output"))
    )
    (net (code "300") (name "SDO_9") (class "Default")
      (node (ref "U20") (pin "11") (pinfunction "SDO_11") (pintype "output"))
    )
    (net (code "301") (name "SDO_10") (class "Default")
      (node (ref "U22") (pin "11") (pinfunction "SDO_11") (pintype "output"))
    )
    (net (code "302") (name "SDO_11") (class "Default")
      (node (ref "U24") (pin "11") (pinfunction "SDO_11") (pintype "output"))
    )
    (net (code "303") (name "SDO_12") (class "Default")
      (node (ref "U26") (pin "11") (pinfunction "SDO_11") (pintype "output"))
    )
    (net (code "304") (name "SYNCLK") (class "Default")
      (node (ref "J1") (pin "A24") (pinfunction "A24_A24") (pintype "passive"))
    )
    (net (code "305") (name "SYNC_1") (class "Default")
      (node (ref "U4") (pin "14") (pinfunction "~{SYNC}_14") (pintype "input"))
    )
    (net (code "306") (name "SYNC_2") (class "Default")
      (node (ref "U6") (pin "14") (pinfunction "~{SYNC}_14") (pintype "input"))
    )
    (net (code "307") (name "SYNC_3") (class "Default")
      (node (ref "U8") (pin "14") (pinfunction "~{SYNC}_14") (pintype "input"))
    )
    (net (code "308") (name "SYNC_4") (class "Default")
      (node (ref "U10") (pin "14") (pinfunction "~{SYNC}_14") (pintype "input"))
    )
    (net (code "309") (name "SYNC_5") (class "Default")
      (node (ref "U12") (pin "14") (pinfunction "~{SYNC}_14") (pintype "input"))
    )
    (net (code "310") (name "SYNC_6") (class "Default")
      (node (ref "U14") (pin "14") (pinfunction "~{SYNC}_14") (pintype "input"))
    )
    (net (code "311") (name "SYNC_7") (class "Default")
      (node (ref "U16") (pin "14") (pinfunction "~{SYNC}_14") (pintype "input"))
    )
    (net (code "312") (name "SYNC_8") (class "Default")
      (node (ref "U18") (pin "14") (pinfunction "~{SYNC}_14") (pintype "input"))
    )
    (net (code "313") (name "SYNC_9") (class "Default")
      (node (ref "U20") (pin "14") (pinfunction "~{SYNC}_14") (pintype "input"))
    )
    (net (code "314") (name "SYNC_10") (class "Default")
      (node (ref "U22") (pin "14") (pinfunction "~{SYNC}_14") (pintype "input"))
    )
    (net (code "315") (name "SYNC_11") (class "Default")
      (node (ref "U24") (pin "14") (pinfunction "~{SYNC}_14") (pintype "input"))
    )
    (net (code "316") (name "SYNC_12") (class "Default")
      (node (ref "U26") (pin "14") (pinfunction "~{SYNC}_14") (pintype "input"))
    )
    (net (code "317") (name "SYSCLK") (class "Default")
      (node (ref "J1") (pin "B23") (pinfunction "B23_B23") (pintype "passive"))
    )
    (net (code "318") (name "VOUT_1") (class "Default")
      (node (ref "R5") (pin "2") (pinfunction "2_2") (pintype "passive"))
    )
    (net (code "319") (name "VOUT_7") (class "Default")
      (node (ref "R4") (pin "2") (pinfunction "2_2") (pintype "passive"))
    )
    (net (code "320") (name "VREF") (class "Default")
      (node (ref "C23") (pin "1") (pinfunction "1_1") (pintype "passive"))
      (node (ref "C24") (pin "1") (pinfunction "1_1") (pintype "passive"))
      (node (ref "C25") (pin "1") (pinfunction "1_1") (pintype "passive"))
      (node (ref "R6") (pin "1") (pinfunction "1_1") (pintype "passive"))
      (node (ref "R7") (pin "2") (pinfunction "2_2") (pintype "passive"))
      (node (ref "U1") (pin "12") (pinfunction "VREF_12") (pintype "bidirectional"))
      (node (ref "U2") (pin "35") (pinfunction "VREF_35") (pintype "bidirectional"))
      (node (ref "U3") (pin "35") (pinfunction "VREF_35") (pintype "bidirectional"))
      (node (ref "U40") (pin "41") (pinfunction "VREF_41") (pintype "bidirectional"))
    )
    (net (code "321") (name "unconnected-(ISO9-GND1-Pad2)") (class "Default")
      (node (ref "ISO9") (pin "2") (pinfunction "GND1_2") (pintype "bidirectional"))
    )
    (net (code "322") (name "unconnected-(ISO9-GND1-Pad8)") (class "Default")
      (node (ref "ISO9") (pin "8") (pinfunction "GND1_8") (pintype "bidirectional"))
    )
    (net (code "323") (name "unconnected-(ISO9-VDD1-Pad1)") (class "Default")
      (node (ref "ISO9") (pin "1") (pinfunction "VDD1_1") (pintype "bidirectional"))
    )
    (net (code "324") (name "unconnected-(ISO10-A5-Pad7)") (class "Default")
      (node (ref "ISO10") (pin "7") (pinfunction "A5_7") (pintype "bidirectional"))
    )
    (net (code "325") (name "unconnected-(ISO10-B5-Pad10)") (class "Default")
      (node (ref "ISO10") (pin "10") (pinfunction "B5_10") (pintype "bidirectional"))
    )
    (net (code "326") (name "unconnected-(ISO10-GND1-Pad2)") (class "Default")
      (node (ref "ISO10") (pin "2") (pinfunction "GND1_2") (pintype "bidirectional"))
    )
    (net (code "327") (name "unconnected-(ISO10-GND1-Pad8)") (class "Default")
      (node (ref "ISO10") (pin "8") (pinfunction "GND1_8") (pintype "bidirectional"))
    )
    (net (code "328") (name "unconnected-(ISO10-VDD1-Pad1)") (class "Default")
      (node (ref "ISO10") (pin "1") (pinfunction "VDD1_1") (pintype "bidirectional"))
    )
    (net (code "329") (name "unconnected-(J1-PadA41)") (class "Default")
      (node (ref "J1") (pin "A41") (pinfunction "A41_A41") (pintype "passive"))
    )
    (net (code "330") (name "unconnected-(J1-PadA42)") (class "Default")
      (node (ref "J1") (pin "A42") (pinfunction "A42_A42") (pintype "passive"))
    )
    (net (code "331") (name "unconnected-(J1-PadA43)") (class "Default")
      (node (ref "J1") (pin "A43") (pinfunction "A43_A43") (pintype "passive"))
    )
    (net (code "332") (name "unconnected-(J1-PadA44)") (class "Default")
      (node (ref "J1") (pin "A44") (pinfunction "A44_A44") (pintype "passive"))
    )
    (net (code "333") (name "unconnected-(J1-PadB30)") (class "Default")
      (node (ref "J1") (pin "B30") (pinfunction "B30_B30") (pintype "passive"))
    )
    (net (code "334") (name "unconnected-(J1-PadB32)") (class "Default")
      (node (ref "J1") (pin "B32") (pinfunction "B32_B32") (pintype "passive"))
    )
    (net (code "335") (name "unconnected-(J1-PadB39)") (class "Default")
      (node (ref "J1") (pin "B39") (pinfunction "B39_B39") (pintype "passive"))
    )
    (net (code "336") (name "unconnected-(J1-PadB41)") (class "Default")
      (node (ref "J1") (pin "B41") (pinfunction "B41_B41") (pintype "passive"))
    )
    (net (code "337") (name "unconnected-(J1-PadB42)") (class "Default")
      (node (ref "J1") (pin "B42") (pinfunction "B42_B42") (pintype "passive"))
    )
    (net (code "338") (name "unconnected-(J1-PadB43)") (class "Default")
      (node (ref "J1") (pin "B43") (pinfunction "B43_B43") (pintype "passive"))
    )
    (net (code "339") (name "unconnected-(J1-PadB44)") (class "Default")
      (node (ref "J1") (pin "B44") (pinfunction "B44_B44") (pintype "passive"))
    )
    (net (code "340") (name "unconnected-(J1-PadC30)") (class "Default")
      (node (ref "J1") (pin "C30") (pinfunction "C30_C30") (pintype "passive"))
    )
    (net (code "341") (name "unconnected-(J1-PadD30)") (class "Default")
      (node (ref "J1") (pin "D30") (pinfunction "D30_D30") (pintype "passive"))
    )
    (net (code "342") (name "unconnected-(J1-PadD32)") (class "Default")
      (node (ref "J1") (pin "D32") (pinfunction "D32_D32") (pintype "passive"))
    )
    (net (code "343") (name "unconnected-(J1-PadD39)") (class "Default")
      (node (ref "J1") (pin "D39") (pinfunction "D39_D39") (pintype "passive"))
    )
    (net (code "344") (name "unconnected-(J1-PadD41)") (class "Default")
      (node (ref "J1") (pin "D41") (pinfunction "D41_D41") (pintype "passive"))
    )
    (net (code "345") (name "unconnected-(J1-PadD42)") (class "Default")
      (node (ref "J1") (pin "D42") (pinfunction "D42_D42") (pintype "passive"))
    )
    (net (code "346") (name "unconnected-(J1-PadD43)") (class "Default")
      (node (ref "J1") (pin "D43") (pinfunction "D43_D43") (pintype "passive"))
    )
    (net (code "347") (name "unconnected-(J1-PadD44)") (class "Default")
      (node (ref "J1") (pin "D44") (pinfunction "D44_D44") (pintype "passive"))
    )
    (net (code "348") (name "unconnected-(J1-PadE41)") (class "Default")
      (node (ref "J1") (pin "E41") (pinfunction "E41_E41") (pintype "passive"))
    )
    (net (code "349") (name "unconnected-(J1-PadE42)") (class "Default")
      (node (ref "J1") (pin "E42") (pinfunction "E42_E42") (pintype "passive"))
    )
    (net (code "350") (name "unconnected-(J1-PadE43)") (class "Default")
      (node (ref "J1") (pin "E43") (pinfunction "E43_E43") (pintype "passive"))
    )
    (net (code "351") (name "unconnected-(J1-PadE44)") (class "Default")
      (node (ref "J1") (pin "E44") (pinfunction "E44_E44") (pintype "passive"))
    )
    (net (code "352") (name "unconnected-(JP2-Pad1)") (class "Default")
      (node (ref "JP2") (pin "1") (pinfunction "1_1") (pintype "passive"))
    )
    (net (code "353") (name "unconnected-(JP2-Pad3)") (class "Default")
      (node (ref "JP2") (pin "3") (pinfunction "3_3") (pintype "passive"))
    )
    (net (code "354") (name "unconnected-(JP2-Pad5)") (class "Default")
      (node (ref "JP2") (pin "5") (pinfunction "5_5") (pintype "passive"))
    )
    (net (code "355") (name "unconnected-(JP2-Pad7)") (class "Default")
      (node (ref "JP2") (pin "7") (pinfunction "7_7") (pintype "passive"))
    )
    (net (code "356") (name "unconnected-(JP2-Pad9)") (class "Default")
      (node (ref "JP2") (pin "9") (pinfunction "9_9") (pintype "passive"))
    )
    (net (code "357") (name "unconnected-(JP2-Pad11)") (class "Default")
      (node (ref "JP2") (pin "11") (pinfunction "11_11") (pintype "passive"))
    )
    (net (code "358") (name "unconnected-(JP3-Pad1)") (class "Default")
      (node (ref "JP3") (pin "1") (pinfunction "1_1") (pintype "passive"))
    )
    (net (code "359") (name "unconnected-(JP3-Pad3)") (class "Default")
      (node (ref "JP3") (pin "3") (pinfunction "3_3") (pintype "passive"))
    )
    (net (code "360") (name "unconnected-(JP3-Pad5)") (class "Default")
      (node (ref "JP3") (pin "5") (pinfunction "5_5") (pintype "passive"))
    )
    (net (code "361") (name "unconnected-(JP3-Pad7)") (class "Default")
      (node (ref "JP3") (pin "7") (pinfunction "7_7") (pintype "passive"))
    )
    (net (code "362") (name "unconnected-(JP3-Pad9)") (class "Default")
      (node (ref "JP3") (pin "9") (pinfunction "9_9") (pintype "passive"))
    )
    (net (code "363") (name "unconnected-(JP3-Pad11)") (class "Default")
      (node (ref "JP3") (pin "11") (pinfunction "11_11") (pintype "passive"))
    )
    (net (code "364") (name "unconnected-(U1-2Y-Pad3)") (class "Default")
      (node (ref "U1") (pin "3") (pinfunction "2Y_3") (pintype "bidirectional"))
    )
    (net (code "365") (name "unconnected-(U28-GND-Pad3)") (class "Default")
      (node (ref "U28") (pin "3") (pinfunction "GND_3") (pintype "passive"))
    )
    (net (code "366") (name "unconnected-(U29-GND-Pad1)") (class "Default")
      (node (ref "U29") (pin "1") (pinfunction "GND_1") (pintype "passive"))
    )
    (net (code "367") (name "unconnected-(U29-IN-Pad3)") (class "Default")
      (node (ref "U29") (pin "3") (pinfunction "IN_3") (pintype "input"))
    )
    (net (code "368") (name "unconnected-(U29-OUT-Pad4)") (class "Default")
      (node (ref "U29") (pin "4") (pinfunction "OUT_4") (pintype "output"))
    )
    (net (code "369") (name "unconnected-(U29-OUT_2-Pad2)") (class "Default")
      (node (ref "U29") (pin "2") (pinfunction "OUT_2_2") (pintype "output"))
    )
    (net (code "370") (name "unconnected-(X1-Pad1)") (class "Default")
      (node (ref "X1") (pin "1") (pinfunction "1_1") (pintype "passive"))
    )
    (net (code "371") (name "unconnected-(X1-Pad2)") (class "Default")
      (node (ref "X1") (pin "2") (pinfunction "2_2") (pintype "passive"))
    )
    (net (code "372") (name "unconnected-(X1-Pad3)") (class "Default")
      (node (ref "X1") (pin "3") (pinfunction "3_3") (pintype "passive"))
    )
    (net (code "373") (name "unconnected-(X1-Pad4)") (class "Default")
      (node (ref "X1") (pin "4") (pinfunction "4_4") (pintype "passive"))
    )
    (net (code "374") (name "unconnected-(X1-Pad5)") (class "Default")
      (node (ref "X1") (pin "5") (pinfunction "5_5") (pintype "passive"))
    )
    (net (code "375") (name "unconnected-(X1-Pad6)") (class "Default")
      (node (ref "X1") (pin "6") (pinfunction "6_6") (pintype "passive"))
    )
    (net (code "376") (name "unconnected-(X1-Pad7)") (class "Default")
      (node (ref "X1") (pin "7") (pinfunction "7_7") (pintype "passive"))
    )
    (net (code "377") (name "unconnected-(X1-Pad8)") (class "Default")
      (node (ref "X1") (pin "8") (pinfunction "8_8") (pintype "passive"))
    )
    (net (code "378") (name "unconnected-(X1-Pad9)") (class "Default")
      (node (ref "X1") (pin "9") (pinfunction "9_9") (pintype "passive"))
    )
    (net (code "379") (name "unconnected-(X1-Pad10)") (class "Default")
      (node (ref "X1") (pin "10") (pinfunction "10_10") (pintype "passive"))
    )
    (net (code "380") (name "unconnected-(X1-Pad11)") (class "Default")
      (node (ref "X1") (pin "11") (pinfunction "11_11") (pintype "passive"))
    )
    (net (code "381") (name "unconnected-(X1-Pad12)") (class "Default")
      (node (ref "X1") (pin "12") (pinfunction "12_12") (pintype "passive"))
    )
    (net (code "382") (name "unconnected-(X1-Pad13)") (class "Default")
      (node (ref "X1") (pin "13") (pinfunction "13_13") (pintype "passive"))
    )
    (net (code "383") (name "unconnected-(X1-Pad14)") (class "Default")
      (node (ref "X1") (pin "14") (pinfunction "14_14") (pintype "passive"))
    )
    (net (code "384") (name "unconnected-(X1-Pad15)") (class "Default")
      (node (ref "X1") (pin "15") (pinfunction "15_15") (pintype "passive"))
    )
    (net (code "385") (name "unconnected-(X1-Pad16)") (class "Default")
      (node (ref "X1") (pin "16") (pinfunction "16_16") (pintype "passive"))
    )
    (net (code "386") (name "unconnected-(X1-Pad17)") (class "Default")
      (node (ref "X1") (pin "17") (pinfunction "17_17") (pintype "passive"))
    )
    (net (code "387") (name "unconnected-(X1-Pad18)") (class "Default")
      (node (ref "X1") (pin "18") (pinfunction "18_18") (pintype "passive"))
    )
    (net (code "388") (name "unconnected-(X1-Pad19)") (class "Default")
      (node (ref "X1") (pin "19") (pinfunction "19_19") (pintype "passive"))
    )
    (net (code "389") (name "unconnected-(X1-Pad20)") (class "Default")
      (node (ref "X1") (pin "20") (pinfunction "20_20") (pintype "passive"))
    )
    (net (code "390") (name "unconnected-(X1-Pad21)") (class "Default")
      (node (ref "X1") (pin "21") (pinfunction "21_21") (pintype "passive"))
    )
    (net (code "391") (name "unconnected-(X1-Pad22)") (class "Default")
      (node (ref "X1") (pin "22") (pinfunction "22_22") (pintype "passive"))
    )
    (net (code "392") (name "unconnected-(X1-Pad23)") (class "Default")
      (node (ref "X1") (pin "23") (pinfunction "23_23") (pintype "passive"))
    )
    (net (code "393") (name "unconnected-(X1-Pad24)") (class "Default")
      (node (ref "X1") (pin "24") (pinfunction "24_24") (pintype "passive"))
    )
    (net (code "394") (name "unconnected-(X1-Pad25)") (class "Default")
      (node (ref "X1") (pin "25") (pinfunction "25_25") (pintype "passive"))
    )
    (net (code "395") (name "unconnected-(X1-Pad26)") (class "Default")
      (node (ref "X1") (pin "26") (pinfunction "26_26") (pintype "passive"))
    )
    (net (code "396") (name "unconnected-(X1-Pad27)") (class "Default")
      (node (ref "X1") (pin "27") (pinfunction "27_27") (pintype "passive"))
    )
    (net (code "397") (name "unconnected-(X1-Pad28)") (class "Default")
      (node (ref "X1") (pin "28") (pinfunction "28_28") (pintype "passive"))
    )
    (net (code "398") (name "unconnected-(X1-Pad29)") (class "Default")
      (node (ref "X1") (pin "29") (pinfunction "29_29") (pintype "passive"))
    )
    (net (code "399") (name "unconnected-(X1-Pad30)") (class "Default")
      (node (ref "X1") (pin "30") (pinfunction "30_30") (pintype "passive"))
    )
    (net (code "400") (name "unconnected-(X1-Pad31)") (class "Default")
      (node (ref "X1") (pin "31") (pinfunction "31_31") (pintype "passive"))
    )
    (net (code "401") (name "unconnected-(X1-Pad32)") (class "Default")
      (node (ref "X1") (pin "32") (pinfunction "32_32") (pintype "passive"))
    )
    (net (code "402") (name "unconnected-(X1-Pad33)") (class "Default")
      (node (ref "X1") (pin "33") (pinfunction "33_33") (pintype "passive"))
    )
    (net (code "403") (name "unconnected-(X1-Pad34)") (class "Default")
      (node (ref "X1") (pin "34") (pinfunction "34_34") (pintype "passive"))
    )
    (net (code "404") (name "unconnected-(X1-Pad35)") (class "Default")
      (node (ref "X1") (pin "35") (pinfunction "35_35") (pintype "passive"))
    )
    (net (code "405") (name "unconnected-(X1-Pad36)") (class "Default")
      (node (ref "X1") (pin "36") (pinfunction "36_36") (pintype "passive"))
    )
    (net (code "406") (name "unconnected-(X1-Pad37)") (class "Default")
      (node (ref "X1") (pin "37") (pinfunction "37_37") (pintype "passive"))
    )
    (net (code "407") (name "unconnected-(X1-Pad38)") (class "Default")
      (node (ref "X1") (pin "38") (pinfunction "38_38") (pintype "passive"))
    )
    (net (code "408") (name "unconnected-(X1-Pad39)") (class "Default")
      (node (ref "X1") (pin "39") (pinfunction "39_39") (pintype "passive"))
    )
    (net (code "409") (name "unconnected-(X1-Pad40)") (class "Default")
      (node (ref "X1") (pin "40") (pinfunction "40_40") (pintype "passive"))
    )
    (net (code "410") (name "unconnected-(X1-Pad41)") (class "Default")
      (node (ref "X1") (pin "41") (pinfunction "41_41") (pintype "passive"))
    )
    (net (code "411") (name "unconnected-(X1-Pad42)") (class "Default")
      (node (ref "X1") (pin "42") (pinfunction "42_42") (pintype "passive"))
    )
    (net (code "412") (name "unconnected-(X1-Pad43)") (class "Default")
      (node (ref "X1") (pin "43") (pinfunction "43_43") (pintype "passive"))
    )
    (net (code "413") (name "unconnected-(X1-Pad44)") (class "Default")
      (node (ref "X1") (pin "44") (pinfunction "44_44") (pintype "passive"))
    )
    (net (code "414") (name "unconnected-(X1-Pad45)") (class "Default")
      (node (ref "X1") (pin "45") (pinfunction "45_45") (pintype "passive"))
    )
    (net (code "415") (name "unconnected-(X1-Pad46)") (class "Default")
      (node (ref "X1") (pin "46") (pinfunction "46_46") (pintype "passive"))
    )
    (net (code "416") (name "unconnected-(X1-Pad47)") (class "Default")
      (node (ref "X1") (pin "47") (pinfunction "47_47") (pintype "passive"))
    )
    (net (code "417") (name "unconnected-(X1-Pad48)") (class "Default")
      (node (ref "X1") (pin "48") (pinfunction "48_48") (pintype "passive"))
    )
    (net (code "418") (name "unconnected-(X1-Pad49)") (class "Default")
      (node (ref "X1") (pin "49") (pinfunction "49_49") (pintype "passive"))
    )
    (net (code "419") (name "unconnected-(X1-Pad50)") (class "Default")
      (node (ref "X1") (pin "50") (pinfunction "50_50") (pintype "passive"))
    )
    (net (code "420") (name "unconnected-(X1-PadG1)") (class "Default")
      (node (ref "X1") (pin "G1") (pinfunction "G1_G1") (pintype "passive"))
    )
    (net (code "421") (name "unconnected-(X1-PadG2)") (class "Default")
      (node (ref "X1") (pin "G2") (pinfunction "G2_G2") (pintype "passive"))
    )
  )
)
